# Hackerboat_Control_Board.net
KiCad netlist of a schematic drawn in EAGLE
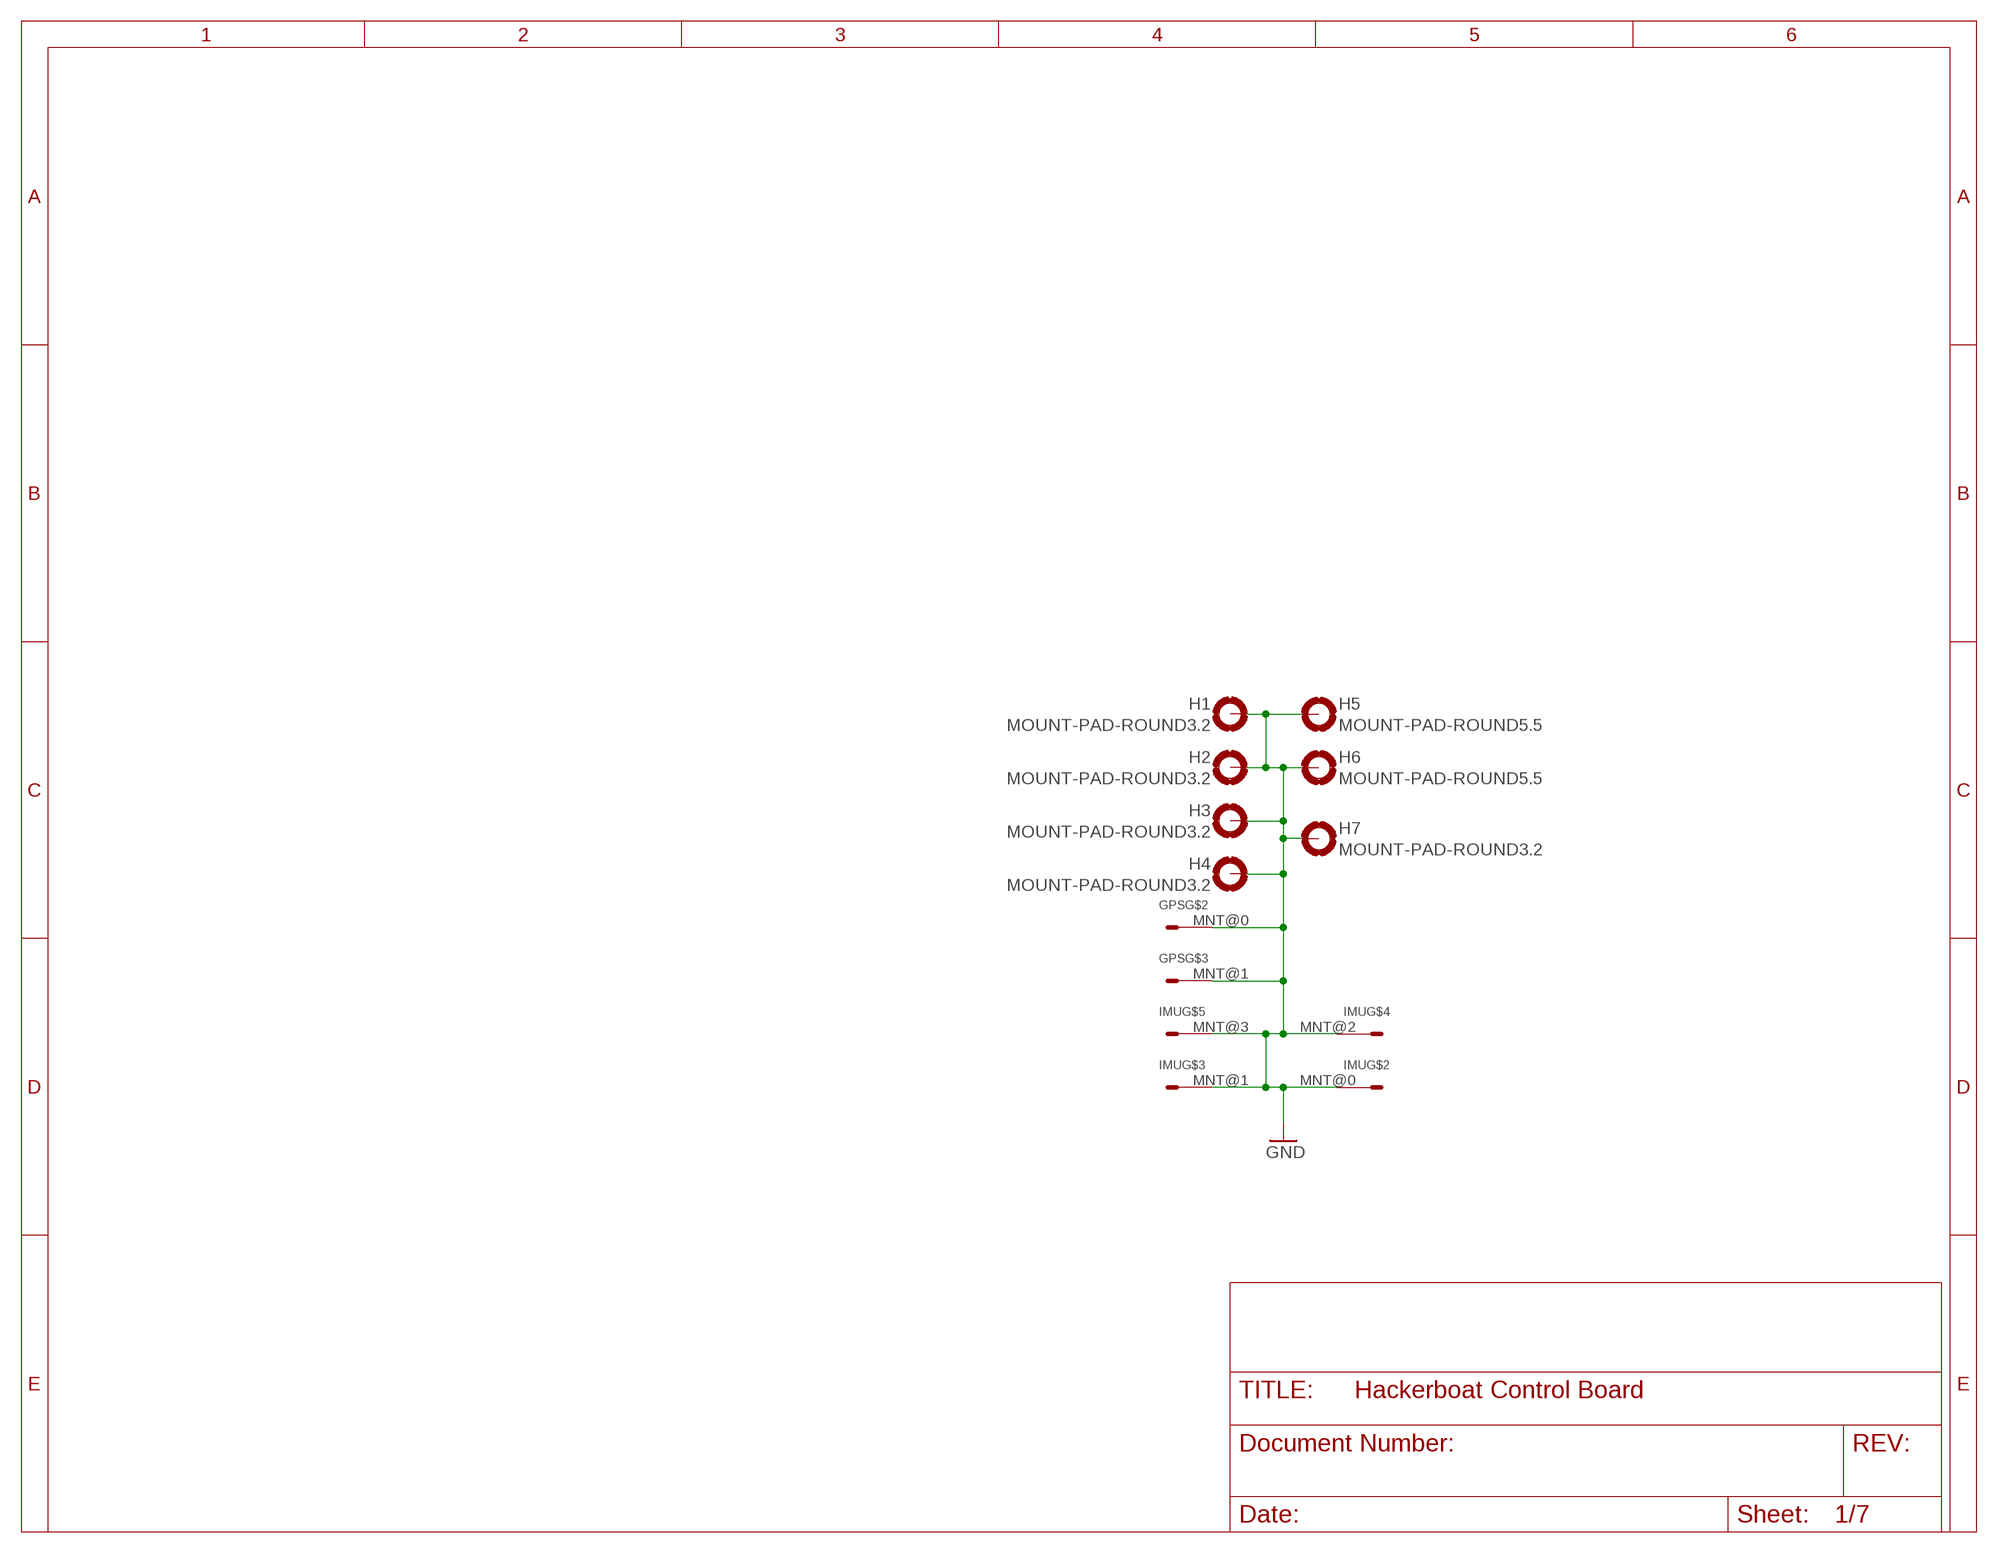
[diagram p0: schematic, sheet 1]
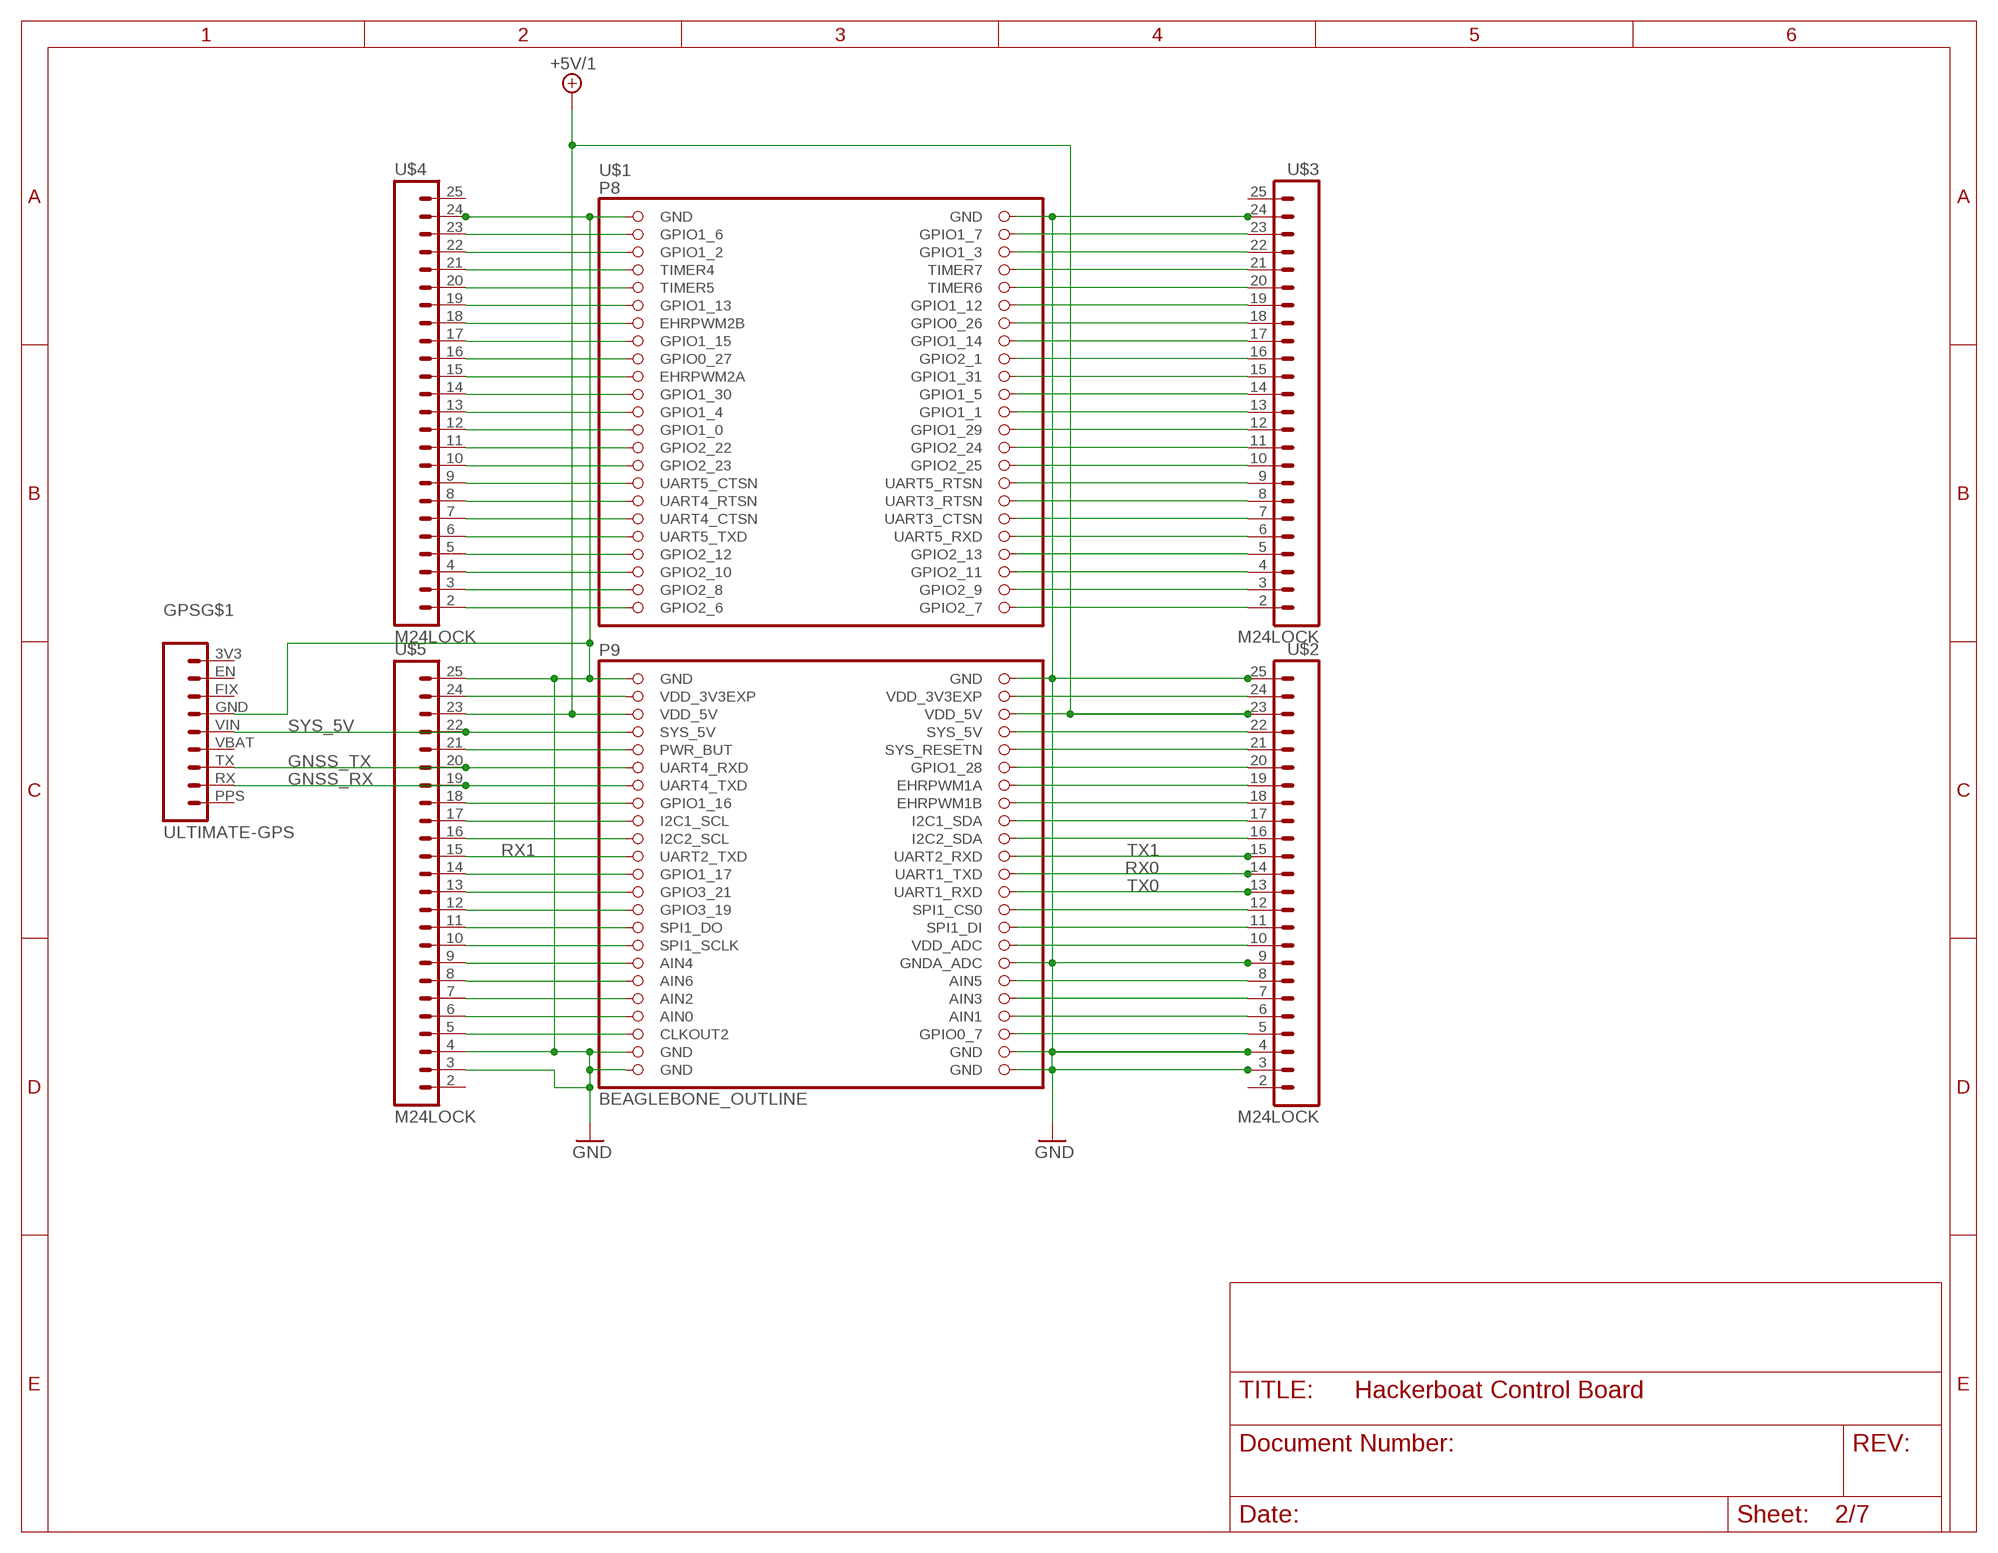
[diagram p1: schematic, sheet 2]
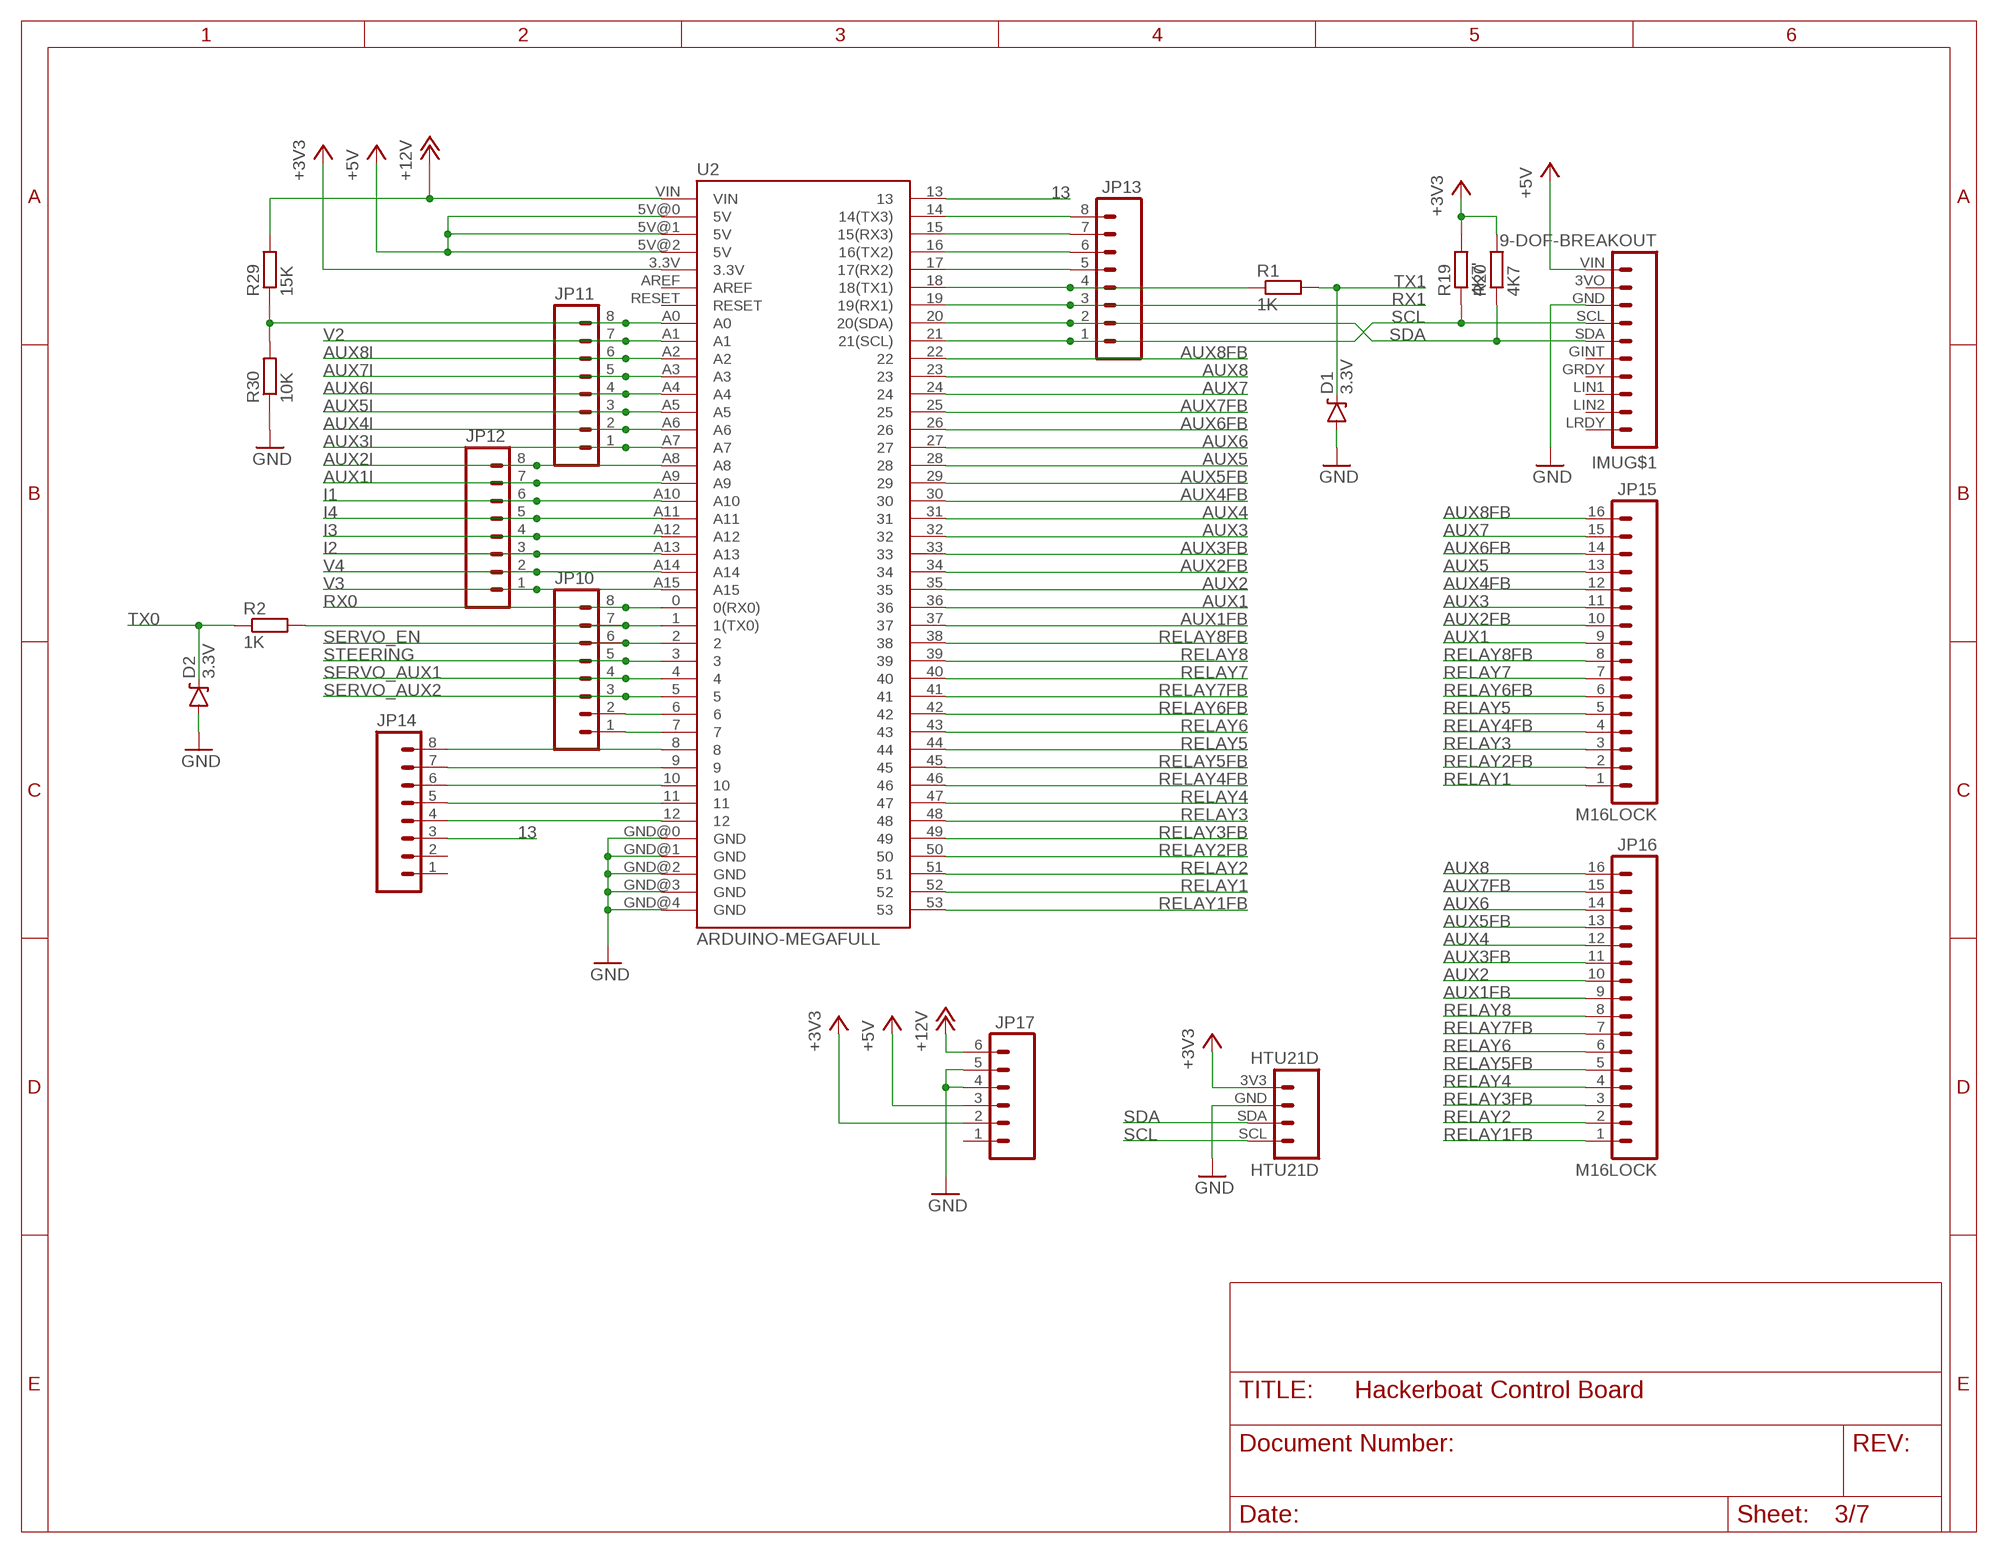
[diagram p2: schematic, sheet 3]
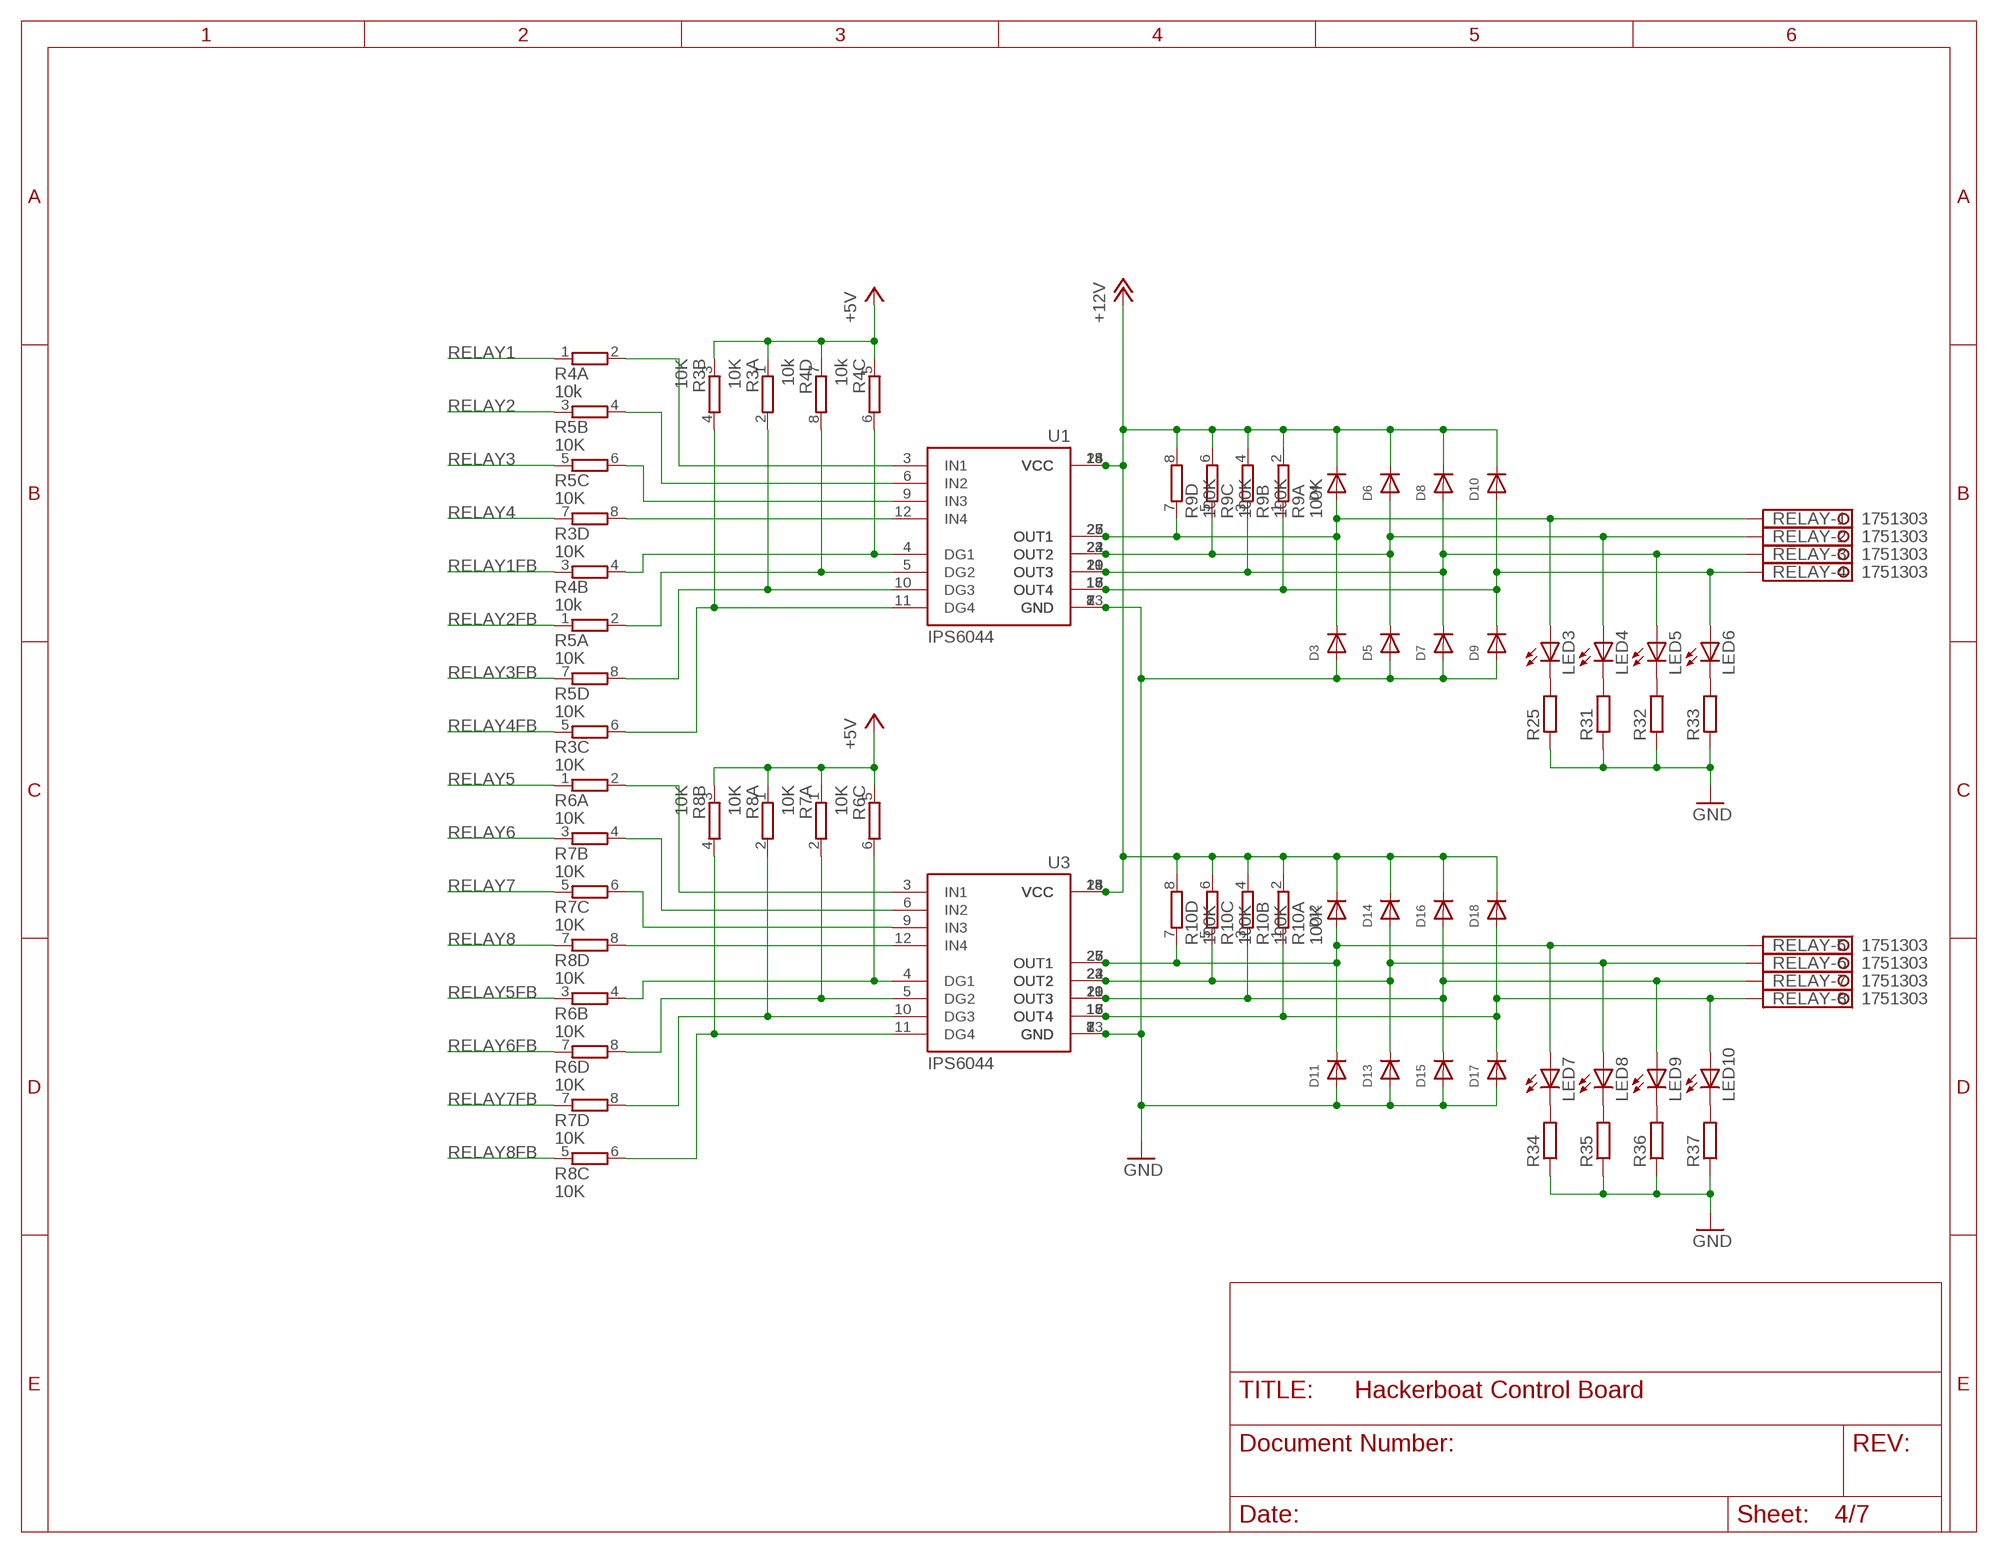
[diagram p3: schematic, sheet 4]
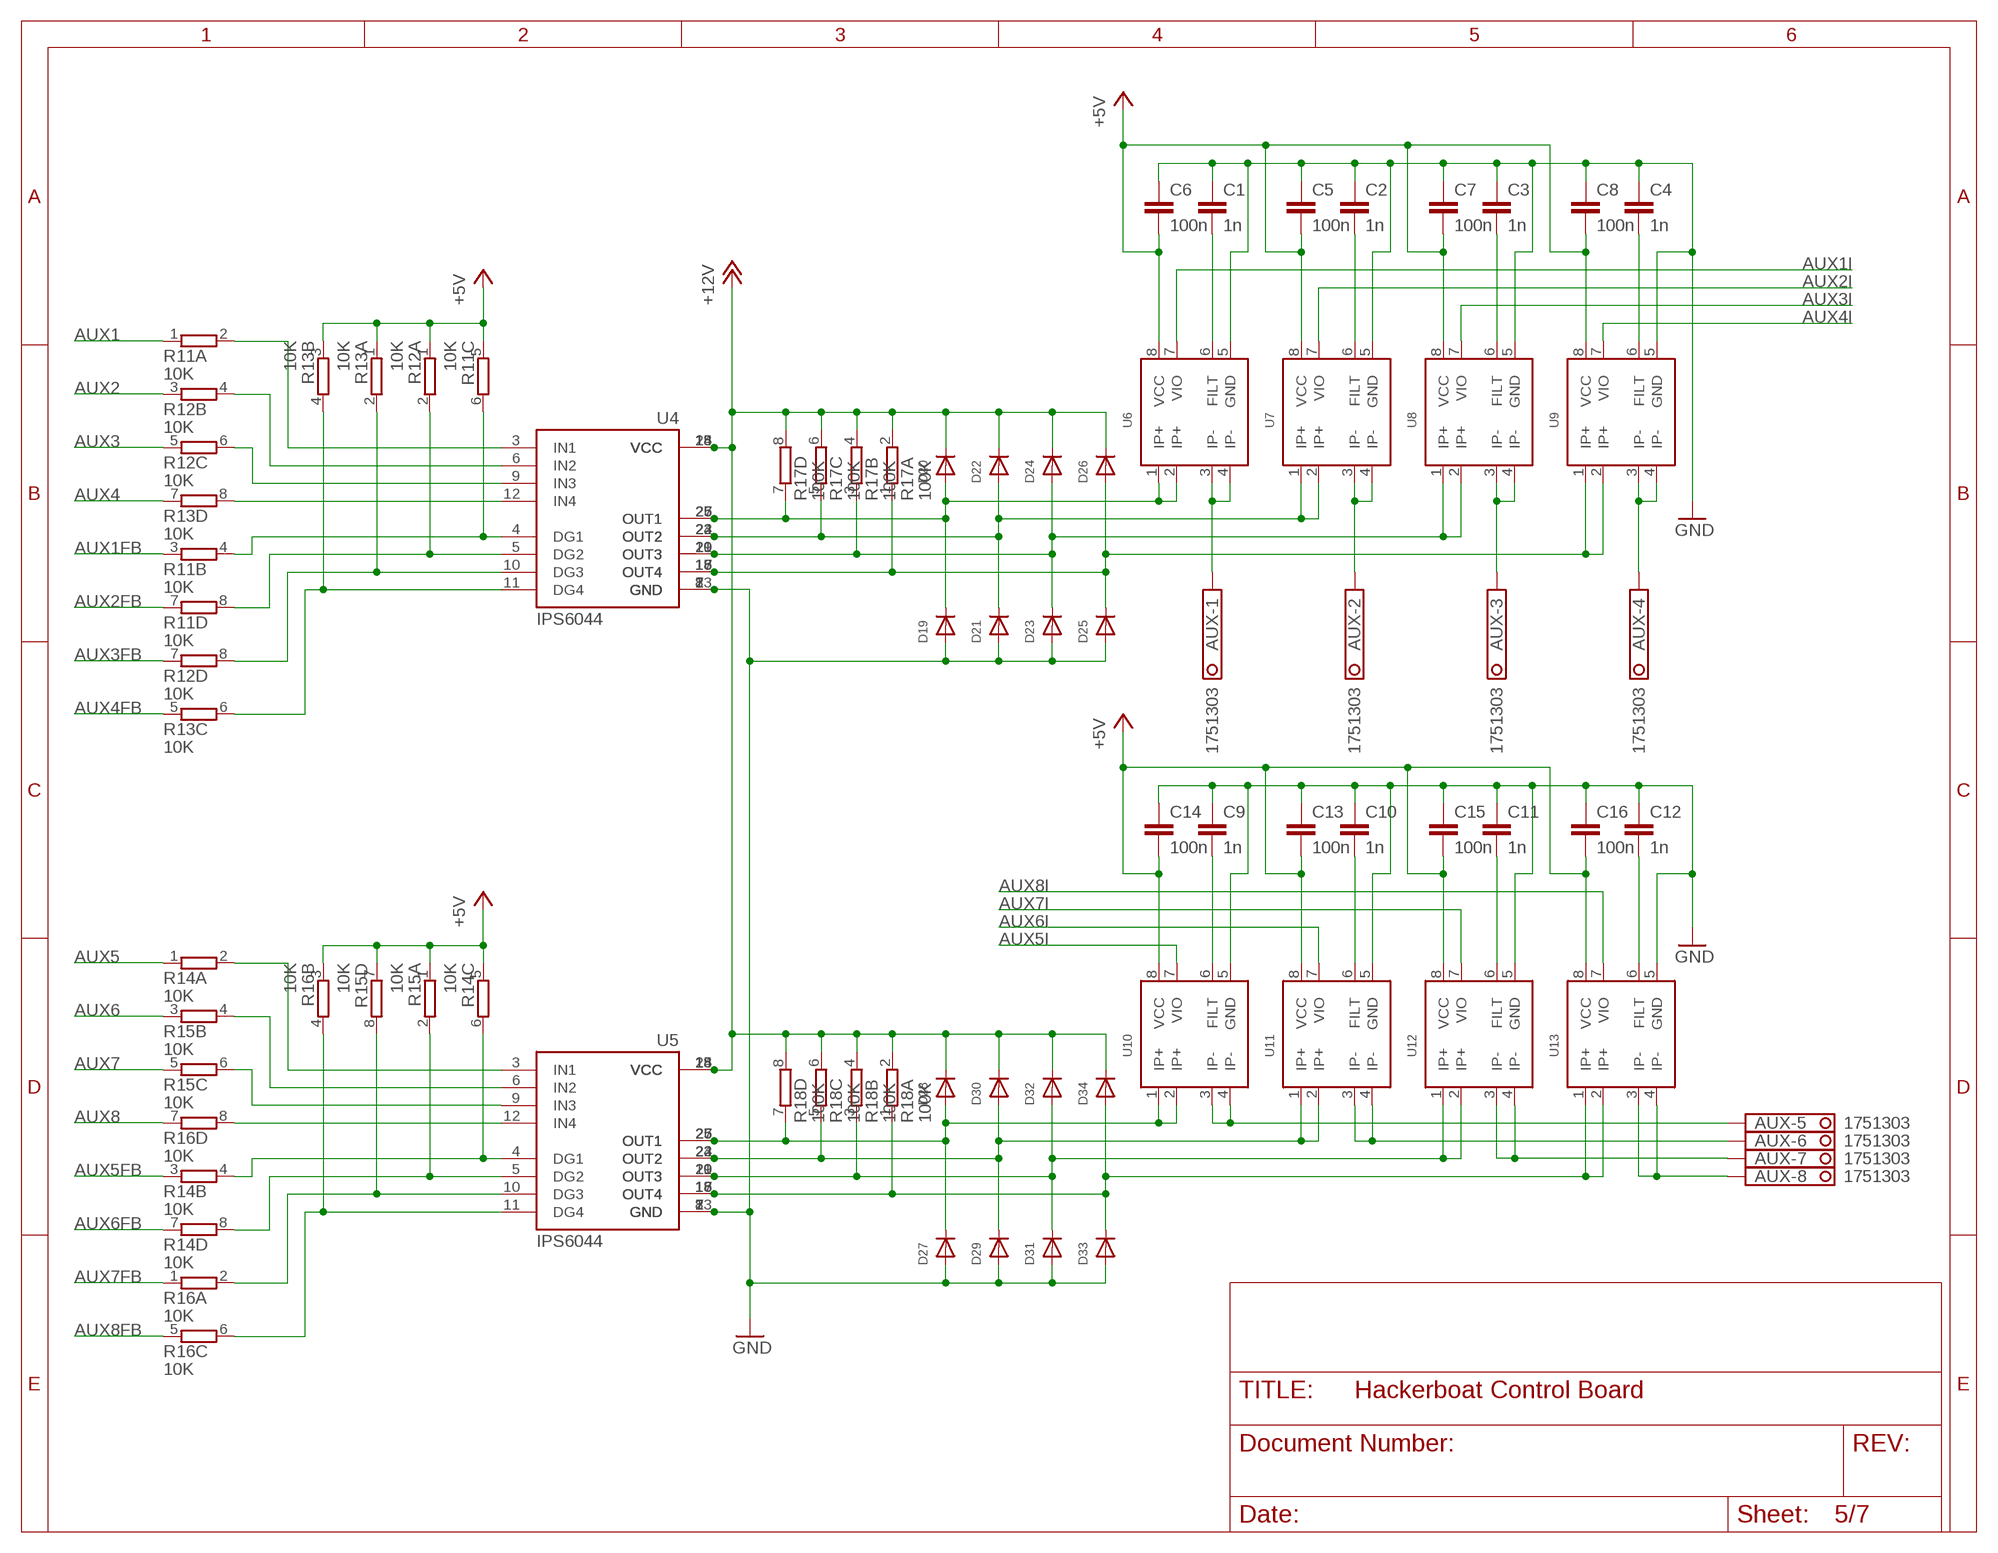
[diagram p4: schematic, sheet 5]
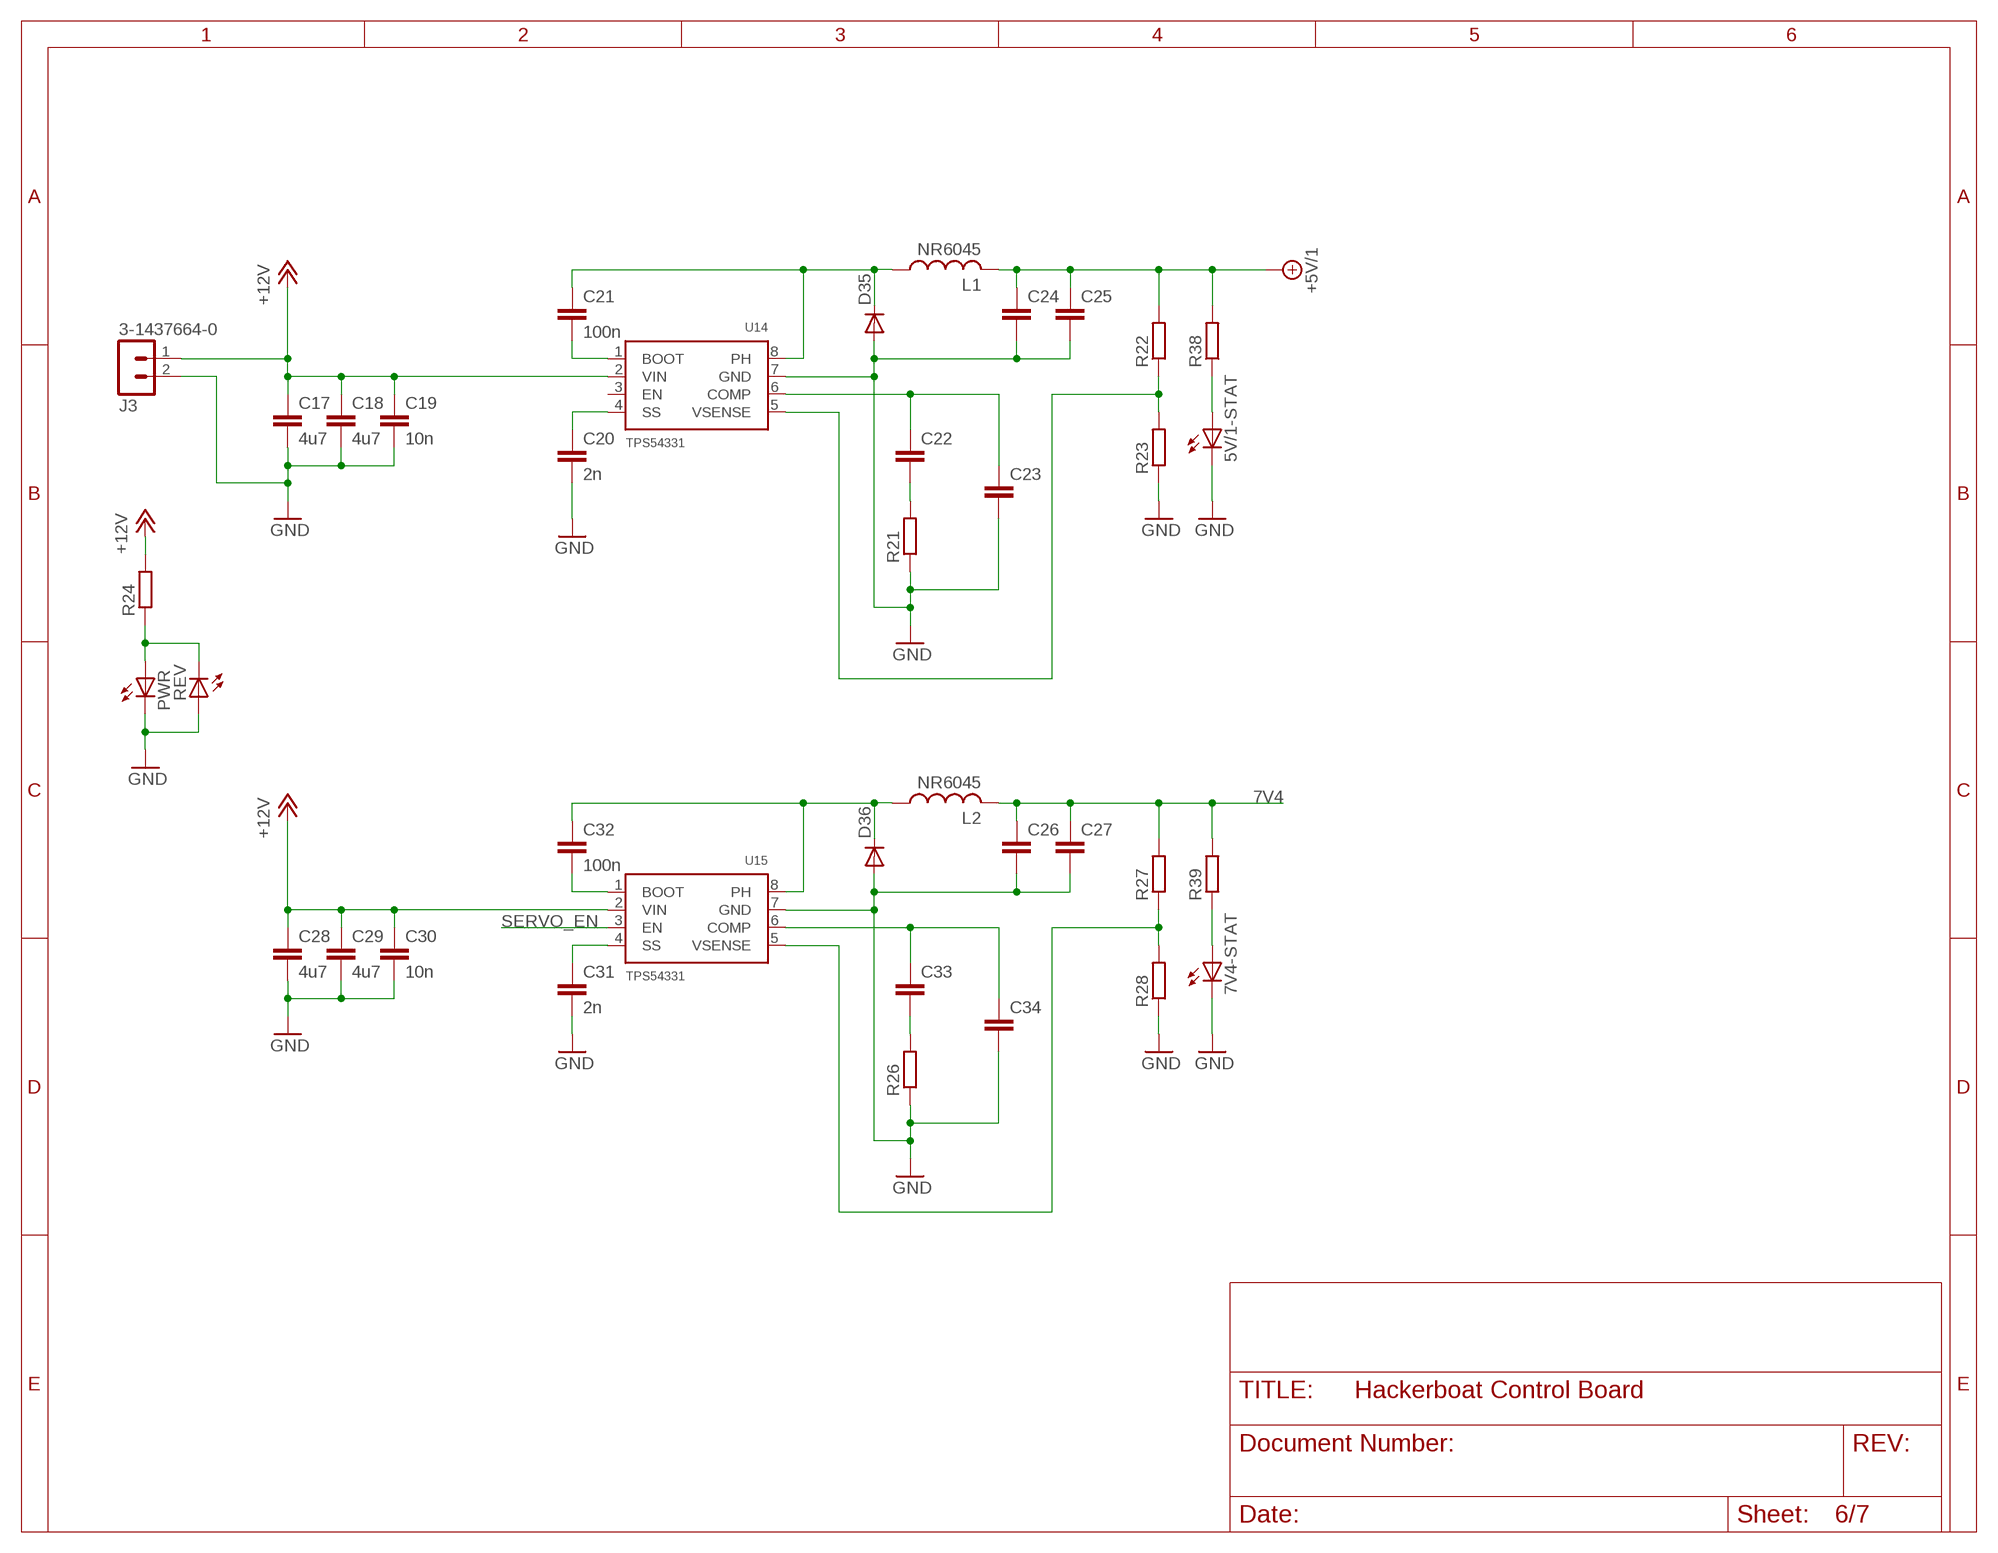
[diagram p5: schematic, sheet 6]
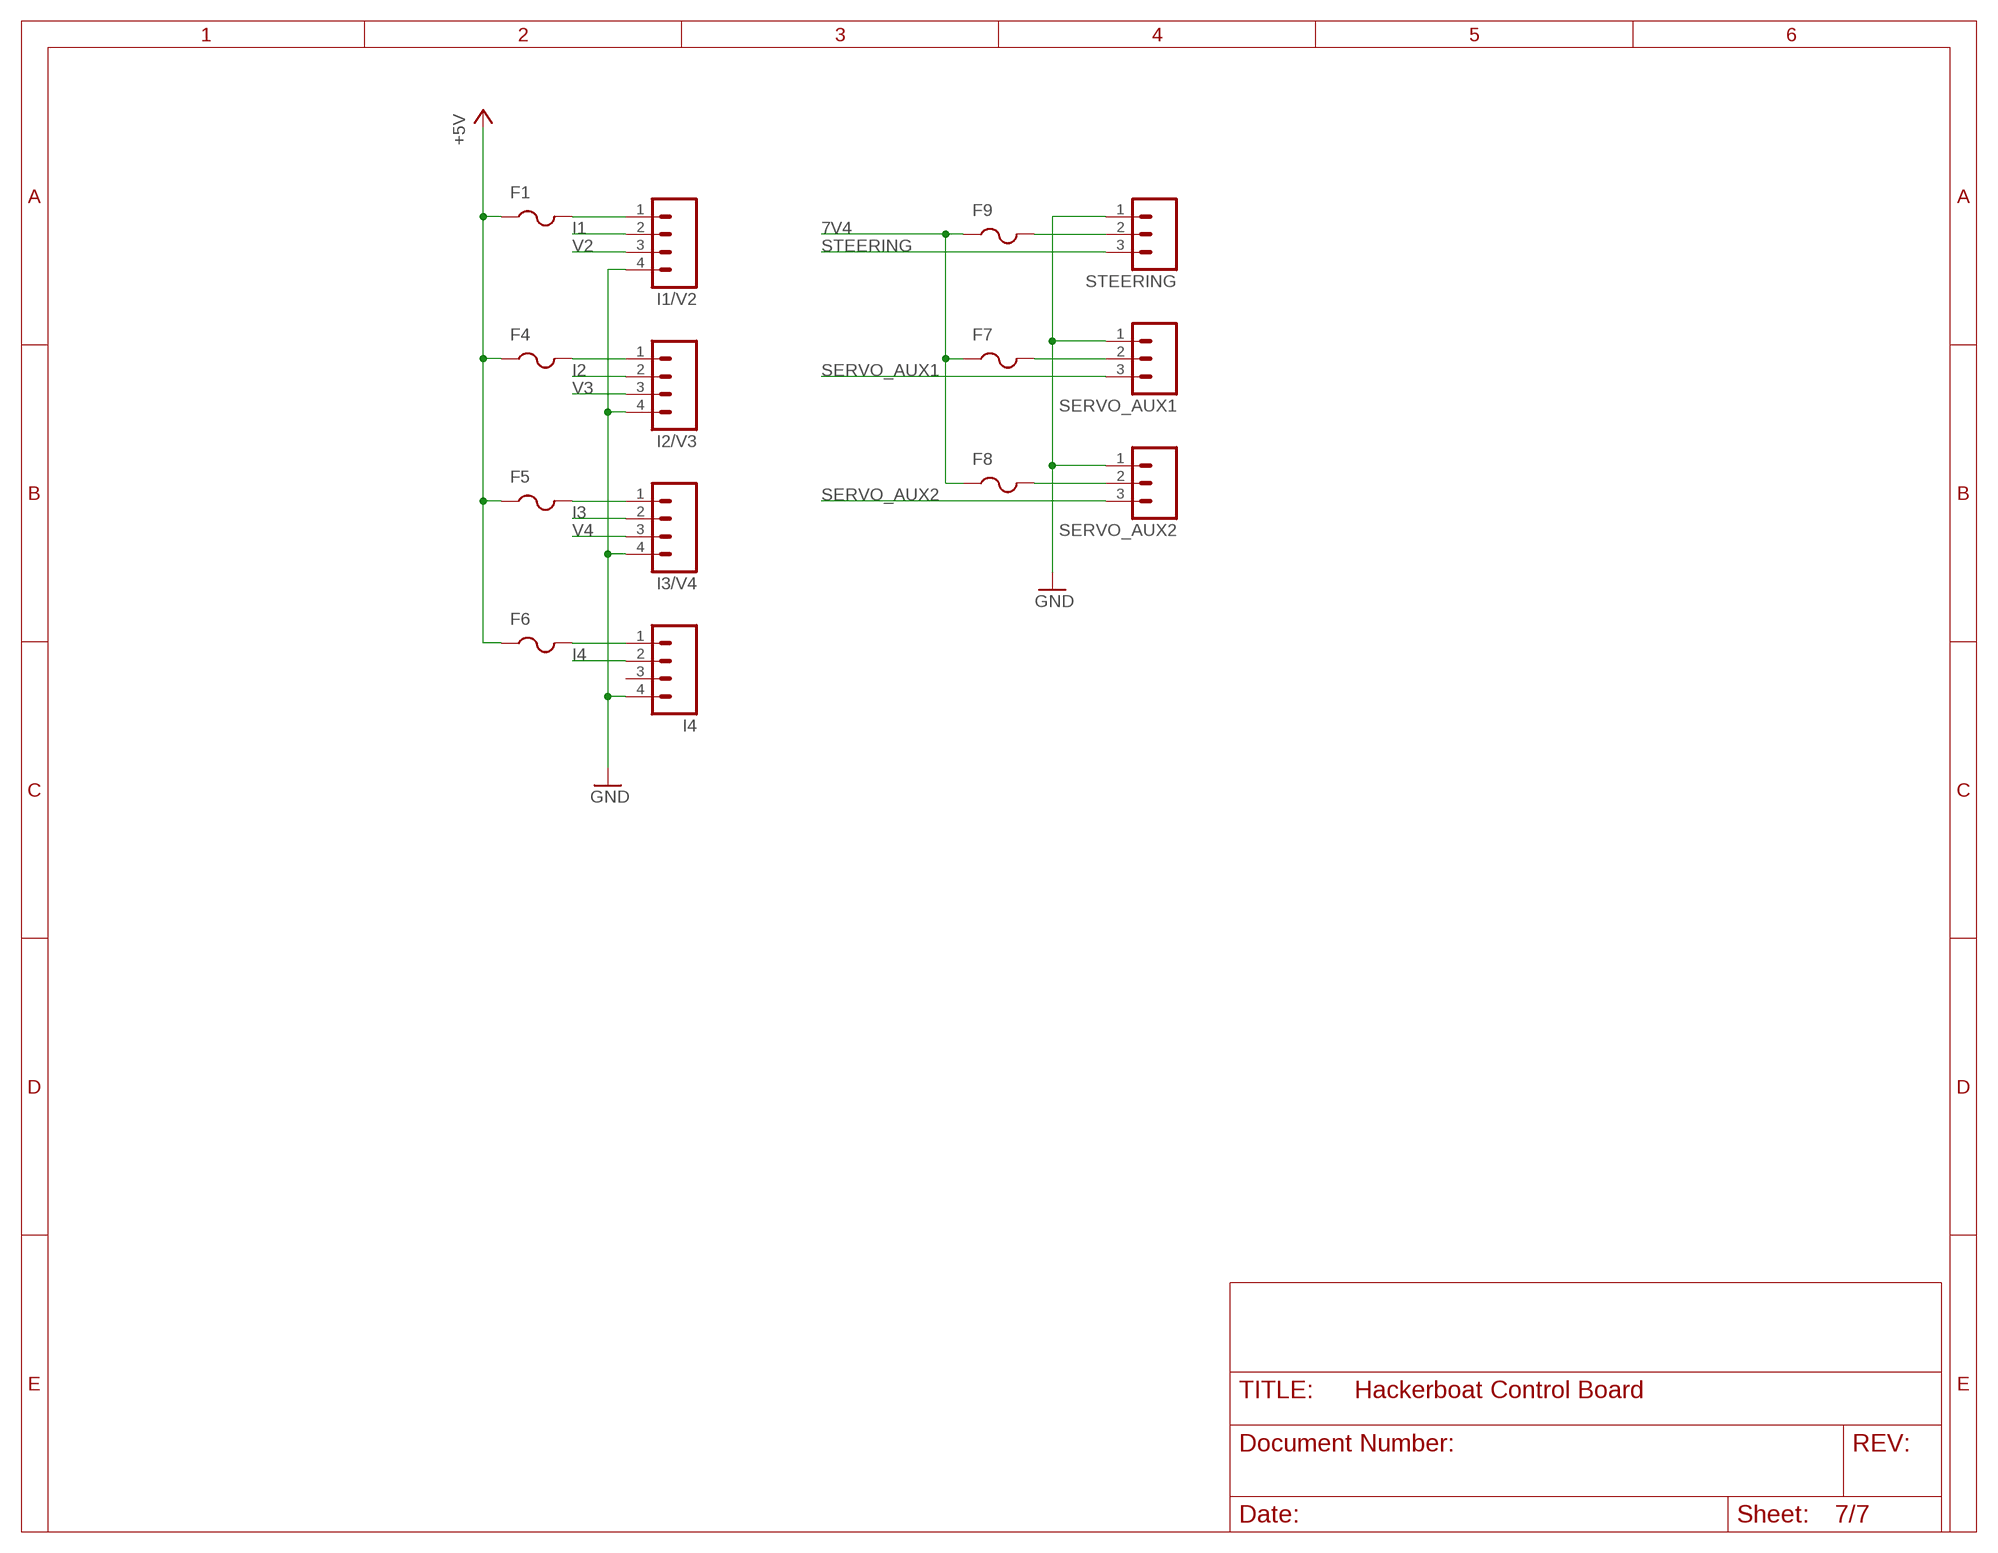
[diagram p6: schematic, sheet 7]

(export (version "E")
  (design (tool "Eeschema 10.0.6"))
  (components
    (comp (ref "GPS")
      (value "ULTIMATE-GPS")
      (footprint "eagle-import:ULTIMATE-GPS")
      (libsource (lib "eagle-import") (part "ULTIMATE-GPS"))
    )
    (comp (ref "U$1")
      (value "BEAGLEBONE_OUTLINE")
      (footprint "eagle-import:BEAGLEBONE_SHIELD")
      (libsource (lib "eagle-import") (part "BEAGLEBONE_OUTLINE"))
    )
    (comp (ref "U$2")
      (value "M24LOCK")
      (footprint "eagle-import:1X24_LOCK")
      (libsource (lib "eagle-import") (part "M24LOCK"))
    )
    (comp (ref "U$3")
      (value "M24LOCK")
      (footprint "eagle-import:1X24_LOCK")
      (libsource (lib "eagle-import") (part "M24LOCK"))
    )
    (comp (ref "U$4")
      (value "M24LOCK")
      (footprint "eagle-import:1X24_LOCK")
      (libsource (lib "eagle-import") (part "M24LOCK"))
    )
    (comp (ref "U$5")
      (value "M24LOCK")
      (footprint "eagle-import:1X24_LOCK")
      (libsource (lib "eagle-import") (part "M24LOCK"))
    )
    (comp (ref "F1")
      (value "PTCFUSE-1206")
      (footprint "eagle-import:R1206")
      (libsource (lib "eagle-import") (part "PTCFUSE-1206"))
    )
    (comp (ref "F4")
      (value "PTCFUSE-1206")
      (footprint "eagle-import:R1206")
      (libsource (lib "eagle-import") (part "PTCFUSE-1206"))
    )
    (comp (ref "F5")
      (value "PTCFUSE-1206")
      (footprint "eagle-import:R1206")
      (libsource (lib "eagle-import") (part "PTCFUSE-1206"))
    )
    (comp (ref "F6")
      (value "PTCFUSE-1206")
      (footprint "eagle-import:R1206")
      (libsource (lib "eagle-import") (part "PTCFUSE-1206"))
    )
    (comp (ref "F7")
      (value "PTCFUSE-1206")
      (footprint "eagle-import:R1206")
      (libsource (lib "eagle-import") (part "PTCFUSE-1206"))
    )
    (comp (ref "F8")
      (value "PTCFUSE-1206")
      (footprint "eagle-import:R1206")
      (libsource (lib "eagle-import") (part "PTCFUSE-1206"))
    )
    (comp (ref "F9")
      (value "PTCFUSE-1206")
      (footprint "eagle-import:R1206")
      (libsource (lib "eagle-import") (part "PTCFUSE-1206"))
    )
    (comp (ref "I1/V2")
      (value "M04LOCK_LONGPADS")
      (footprint "eagle-import:1X04_LOCK_LONGPADS")
      (libsource (lib "eagle-import") (part "M04LOCK_LONGPADS"))
    )
    (comp (ref "I2/V3")
      (value "M04LOCK_LONGPADS")
      (footprint "eagle-import:1X04_LOCK_LONGPADS")
      (libsource (lib "eagle-import") (part "M04LOCK_LONGPADS"))
    )
    (comp (ref "I3/V4")
      (value "M04LOCK_LONGPADS")
      (footprint "eagle-import:1X04_LOCK_LONGPADS")
      (libsource (lib "eagle-import") (part "M04LOCK_LONGPADS"))
    )
    (comp (ref "I4")
      (value "M04LOCK_LONGPADS")
      (footprint "eagle-import:1X04_LOCK_LONGPADS")
      (libsource (lib "eagle-import") (part "M04LOCK_LONGPADS"))
    )
    (comp (ref "SERVO_AUX1")
      (value "M03LOCK_LONGPADS")
      (footprint "eagle-import:1X03_LOCK_LONGPADS")
      (libsource (lib "eagle-import") (part "M03LOCK_LONGPADS"))
    )
    (comp (ref "SERVO_AUX2")
      (value "M03LOCK_LONGPADS")
      (footprint "eagle-import:1X03_LOCK_LONGPADS")
      (libsource (lib "eagle-import") (part "M03LOCK_LONGPADS"))
    )
    (comp (ref "STEERING")
      (value "M03LOCK_LONGPADS")
      (footprint "eagle-import:1X03_LOCK_LONGPADS")
      (libsource (lib "eagle-import") (part "M03LOCK_LONGPADS"))
    )
    (comp (ref "H1")
      (value "MOUNT-PAD-ROUND3.2")
      (footprint "eagle-import:3,2-PAD")
      (libsource (lib "eagle-import") (part "MOUNT-PAD-ROUND3.2"))
    )
    (comp (ref "H2")
      (value "MOUNT-PAD-ROUND3.2")
      (footprint "eagle-import:3,2-PAD")
      (libsource (lib "eagle-import") (part "MOUNT-PAD-ROUND3.2"))
    )
    (comp (ref "H3")
      (value "MOUNT-PAD-ROUND3.2")
      (footprint "eagle-import:3,2-PAD")
      (libsource (lib "eagle-import") (part "MOUNT-PAD-ROUND3.2"))
    )
    (comp (ref "H4")
      (value "MOUNT-PAD-ROUND3.2")
      (footprint "eagle-import:3,2-PAD")
      (libsource (lib "eagle-import") (part "MOUNT-PAD-ROUND3.2"))
    )
    (comp (ref "H5")
      (value "MOUNT-PAD-ROUND5.5")
      (footprint "eagle-import:5,5-PAD")
      (libsource (lib "eagle-import") (part "MOUNT-PAD-ROUND5.5"))
    )
    (comp (ref "H6")
      (value "MOUNT-PAD-ROUND5.5")
      (footprint "eagle-import:5,5-PAD")
      (libsource (lib "eagle-import") (part "MOUNT-PAD-ROUND5.5"))
    )
    (comp (ref "H7")
      (value "MOUNT-PAD-ROUND3.2")
      (footprint "eagle-import:3,2-PAD")
      (libsource (lib "eagle-import") (part "MOUNT-PAD-ROUND3.2"))
    )
    (comp (ref "IMU")
      (value "9-DOF-BREAKOUT")
      (footprint "eagle-import:9-DOF-BREAKOUT")
      (libsource (lib "eagle-import") (part "9-DOF-BREAKOUT"))
    )
    (comp (ref "D3")
      (value "DIODESOD-123")
      (footprint "eagle-import:SOD-123")
      (libsource (lib "eagle-import") (part "DIODESOD-123"))
    )
    (comp (ref "D4")
      (value "DIODESOD-123")
      (footprint "eagle-import:SOD-123")
      (libsource (lib "eagle-import") (part "DIODESOD-123"))
    )
    (comp (ref "D5")
      (value "DIODESOD-123")
      (footprint "eagle-import:SOD-123")
      (libsource (lib "eagle-import") (part "DIODESOD-123"))
    )
    (comp (ref "D6")
      (value "DIODESOD-123")
      (footprint "eagle-import:SOD-123")
      (libsource (lib "eagle-import") (part "DIODESOD-123"))
    )
    (comp (ref "D7")
      (value "DIODESOD-123")
      (footprint "eagle-import:SOD-123")
      (libsource (lib "eagle-import") (part "DIODESOD-123"))
    )
    (comp (ref "D8")
      (value "DIODESOD-123")
      (footprint "eagle-import:SOD-123")
      (libsource (lib "eagle-import") (part "DIODESOD-123"))
    )
    (comp (ref "D9")
      (value "DIODESOD-123")
      (footprint "eagle-import:SOD-123")
      (libsource (lib "eagle-import") (part "DIODESOD-123"))
    )
    (comp (ref "D10")
      (value "DIODESOD-123")
      (footprint "eagle-import:SOD-123")
      (libsource (lib "eagle-import") (part "DIODESOD-123"))
    )
    (comp (ref "D11")
      (value "DIODESOD-123")
      (footprint "eagle-import:SOD-123")
      (libsource (lib "eagle-import") (part "DIODESOD-123"))
    )
    (comp (ref "D12")
      (value "DIODESOD-123")
      (footprint "eagle-import:SOD-123")
      (libsource (lib "eagle-import") (part "DIODESOD-123"))
    )
    (comp (ref "D13")
      (value "DIODESOD-123")
      (footprint "eagle-import:SOD-123")
      (libsource (lib "eagle-import") (part "DIODESOD-123"))
    )
    (comp (ref "D14")
      (value "DIODESOD-123")
      (footprint "eagle-import:SOD-123")
      (libsource (lib "eagle-import") (part "DIODESOD-123"))
    )
    (comp (ref "D15")
      (value "DIODESOD-123")
      (footprint "eagle-import:SOD-123")
      (libsource (lib "eagle-import") (part "DIODESOD-123"))
    )
    (comp (ref "D16")
      (value "DIODESOD-123")
      (footprint "eagle-import:SOD-123")
      (libsource (lib "eagle-import") (part "DIODESOD-123"))
    )
    (comp (ref "D17")
      (value "DIODESOD-123")
      (footprint "eagle-import:SOD-123")
      (libsource (lib "eagle-import") (part "DIODESOD-123"))
    )
    (comp (ref "D18")
      (value "DIODESOD-123")
      (footprint "eagle-import:SOD-123")
      (libsource (lib "eagle-import") (part "DIODESOD-123"))
    )
    (comp (ref "LED3")
      (value "LEDCHIPLED_0805")
      (footprint "eagle-import:CHIPLED_0805")
      (libsource (lib "eagle-import") (part "LEDCHIPLED_0805"))
    )
    (comp (ref "LED4")
      (value "LEDCHIPLED_0805")
      (footprint "eagle-import:CHIPLED_0805")
      (libsource (lib "eagle-import") (part "LEDCHIPLED_0805"))
    )
    (comp (ref "LED5")
      (value "LEDCHIPLED_0805")
      (footprint "eagle-import:CHIPLED_0805")
      (libsource (lib "eagle-import") (part "LEDCHIPLED_0805"))
    )
    (comp (ref "LED6")
      (value "LEDCHIPLED_0805")
      (footprint "eagle-import:CHIPLED_0805")
      (libsource (lib "eagle-import") (part "LEDCHIPLED_0805"))
    )
    (comp (ref "LED7")
      (value "LEDCHIPLED_0805")
      (footprint "eagle-import:CHIPLED_0805")
      (libsource (lib "eagle-import") (part "LEDCHIPLED_0805"))
    )
    (comp (ref "LED8")
      (value "LEDCHIPLED_0805")
      (footprint "eagle-import:CHIPLED_0805")
      (libsource (lib "eagle-import") (part "LEDCHIPLED_0805"))
    )
    (comp (ref "LED9")
      (value "LEDCHIPLED_0805")
      (footprint "eagle-import:CHIPLED_0805")
      (libsource (lib "eagle-import") (part "LEDCHIPLED_0805"))
    )
    (comp (ref "LED10")
      (value "LEDCHIPLED_0805")
      (footprint "eagle-import:CHIPLED_0805")
      (libsource (lib "eagle-import") (part "LEDCHIPLED_0805"))
    )
    (comp (ref "R3")
      (value "10K")
      (footprint "eagle-import:CTS742C083-RES")
      (libsource (lib "eagle-import") (part "4R-NCTS742C083"))
    )
    (comp (ref "R4")
      (value "10k")
      (footprint "eagle-import:CTS742C083-RES")
      (libsource (lib "eagle-import") (part "4R-NCTS742C083"))
    )
    (comp (ref "R5")
      (value "10K")
      (footprint "eagle-import:CTS742C083-RES")
      (libsource (lib "eagle-import") (part "4R-NCTS742C083"))
    )
    (comp (ref "R6")
      (value "10K")
      (footprint "eagle-import:CTS742C083-RES")
      (libsource (lib "eagle-import") (part "4R-NCTS742C083"))
    )
    (comp (ref "R7")
      (value "10K")
      (footprint "eagle-import:CTS742C083-RES")
      (libsource (lib "eagle-import") (part "4R-NCTS742C083"))
    )
    (comp (ref "R8")
      (value "10K")
      (footprint "eagle-import:CTS742C083-RES")
      (libsource (lib "eagle-import") (part "4R-NCTS742C083"))
    )
    (comp (ref "R9")
      (value "100K")
      (footprint "eagle-import:CTS742C083-RES")
      (libsource (lib "eagle-import") (part "4R-NCTS742C083"))
    )
    (comp (ref "R10")
      (value "100K")
      (footprint "eagle-import:CTS742C083-RES")
      (libsource (lib "eagle-import") (part "4R-NCTS742C083"))
    )
    (comp (ref "R25")
      (value "R-EU_R0603")
      (footprint "eagle-import:R0603")
      (libsource (lib "eagle-import") (part "R-EU_R0603"))
    )
    (comp (ref "R31")
      (value "R-EU_R0603")
      (footprint "eagle-import:R0603")
      (libsource (lib "eagle-import") (part "R-EU_R0603"))
    )
    (comp (ref "R32")
      (value "R-EU_R0603")
      (footprint "eagle-import:R0603")
      (libsource (lib "eagle-import") (part "R-EU_R0603"))
    )
    (comp (ref "R33")
      (value "R-EU_R0603")
      (footprint "eagle-import:R0603")
      (libsource (lib "eagle-import") (part "R-EU_R0603"))
    )
    (comp (ref "R34")
      (value "R-EU_R0603")
      (footprint "eagle-import:R0603")
      (libsource (lib "eagle-import") (part "R-EU_R0603"))
    )
    (comp (ref "R35")
      (value "R-EU_R0603")
      (footprint "eagle-import:R0603")
      (libsource (lib "eagle-import") (part "R-EU_R0603"))
    )
    (comp (ref "R36")
      (value "R-EU_R0603")
      (footprint "eagle-import:R0603")
      (libsource (lib "eagle-import") (part "R-EU_R0603"))
    )
    (comp (ref "R37")
      (value "R-EU_R0603")
      (footprint "eagle-import:R0603")
      (libsource (lib "eagle-import") (part "R-EU_R0603"))
    )
    (comp (ref "RELAY")
      (value "1751303")
      (footprint "eagle-import:1751303")
      (libsource (lib "eagle-import") (part "1751303"))
    )
    (comp (ref "U1")
      (value "IPS6044")
      (footprint "eagle-import:SO-28L")
      (libsource (lib "eagle-import") (part "IPS6044"))
    )
    (comp (ref "U3")
      (value "IPS6044")
      (footprint "eagle-import:SO-28L")
      (libsource (lib "eagle-import") (part "IPS6044"))
    )
    (comp (ref "AUX")
      (value "1751303")
      (footprint "eagle-import:1751303")
      (libsource (lib "eagle-import") (part "1751303"))
    )
    (comp (ref "C1")
      (value "1n")
      (footprint "eagle-import:C0603")
      (libsource (lib "eagle-import") (part "C-EUC0603"))
    )
    (comp (ref "C2")
      (value "1n")
      (footprint "eagle-import:C0603")
      (libsource (lib "eagle-import") (part "C-EUC0603"))
    )
    (comp (ref "C3")
      (value "1n")
      (footprint "eagle-import:C0603")
      (libsource (lib "eagle-import") (part "C-EUC0603"))
    )
    (comp (ref "C4")
      (value "1n")
      (footprint "eagle-import:C0603")
      (libsource (lib "eagle-import") (part "C-EUC0603"))
    )
    (comp (ref "C5")
      (value "100n")
      (footprint "eagle-import:C0603")
      (libsource (lib "eagle-import") (part "C-EUC0603"))
    )
    (comp (ref "C6")
      (value "100n")
      (footprint "eagle-import:C0603")
      (libsource (lib "eagle-import") (part "C-EUC0603"))
    )
    (comp (ref "C7")
      (value "100n")
      (footprint "eagle-import:C0603")
      (libsource (lib "eagle-import") (part "C-EUC0603"))
    )
    (comp (ref "C8")
      (value "100n")
      (footprint "eagle-import:C0603")
      (libsource (lib "eagle-import") (part "C-EUC0603"))
    )
    (comp (ref "C9")
      (value "1n")
      (footprint "eagle-import:C0603")
      (libsource (lib "eagle-import") (part "C-EUC0603"))
    )
    (comp (ref "C10")
      (value "1n")
      (footprint "eagle-import:C0603")
      (libsource (lib "eagle-import") (part "C-EUC0603"))
    )
    (comp (ref "C11")
      (value "1n")
      (footprint "eagle-import:C0603")
      (libsource (lib "eagle-import") (part "C-EUC0603"))
    )
    (comp (ref "C12")
      (value "1n")
      (footprint "eagle-import:C0603")
      (libsource (lib "eagle-import") (part "C-EUC0603"))
    )
    (comp (ref "C13")
      (value "100n")
      (footprint "eagle-import:C0603")
      (libsource (lib "eagle-import") (part "C-EUC0603"))
    )
    (comp (ref "C14")
      (value "100n")
      (footprint "eagle-import:C0603")
      (libsource (lib "eagle-import") (part "C-EUC0603"))
    )
    (comp (ref "C15")
      (value "100n")
      (footprint "eagle-import:C0603")
      (libsource (lib "eagle-import") (part "C-EUC0603"))
    )
    (comp (ref "C16")
      (value "100n")
      (footprint "eagle-import:C0603")
      (libsource (lib "eagle-import") (part "C-EUC0603"))
    )
    (comp (ref "D19")
      (value "DIODESOD-123")
      (footprint "eagle-import:SOD-123")
      (libsource (lib "eagle-import") (part "DIODESOD-123"))
    )
    (comp (ref "D20")
      (value "DIODESOD-123")
      (footprint "eagle-import:SOD-123")
      (libsource (lib "eagle-import") (part "DIODESOD-123"))
    )
    (comp (ref "D21")
      (value "DIODESOD-123")
      (footprint "eagle-import:SOD-123")
      (libsource (lib "eagle-import") (part "DIODESOD-123"))
    )
    (comp (ref "D22")
      (value "DIODESOD-123")
      (footprint "eagle-import:SOD-123")
      (libsource (lib "eagle-import") (part "DIODESOD-123"))
    )
    (comp (ref "D23")
      (value "DIODESOD-123")
      (footprint "eagle-import:SOD-123")
      (libsource (lib "eagle-import") (part "DIODESOD-123"))
    )
    (comp (ref "D24")
      (value "DIODESOD-123")
      (footprint "eagle-import:SOD-123")
      (libsource (lib "eagle-import") (part "DIODESOD-123"))
    )
    (comp (ref "D25")
      (value "DIODESOD-123")
      (footprint "eagle-import:SOD-123")
      (libsource (lib "eagle-import") (part "DIODESOD-123"))
    )
    (comp (ref "D26")
      (value "DIODESOD-123")
      (footprint "eagle-import:SOD-123")
      (libsource (lib "eagle-import") (part "DIODESOD-123"))
    )
    (comp (ref "D27")
      (value "DIODESOD-123")
      (footprint "eagle-import:SOD-123")
      (libsource (lib "eagle-import") (part "DIODESOD-123"))
    )
    (comp (ref "D28")
      (value "DIODESOD-123")
      (footprint "eagle-import:SOD-123")
      (libsource (lib "eagle-import") (part "DIODESOD-123"))
    )
    (comp (ref "D29")
      (value "DIODESOD-123")
      (footprint "eagle-import:SOD-123")
      (libsource (lib "eagle-import") (part "DIODESOD-123"))
    )
    (comp (ref "D30")
      (value "DIODESOD-123")
      (footprint "eagle-import:SOD-123")
      (libsource (lib "eagle-import") (part "DIODESOD-123"))
    )
    (comp (ref "D31")
      (value "DIODESOD-123")
      (footprint "eagle-import:SOD-123")
      (libsource (lib "eagle-import") (part "DIODESOD-123"))
    )
    (comp (ref "D32")
      (value "DIODESOD-123")
      (footprint "eagle-import:SOD-123")
      (libsource (lib "eagle-import") (part "DIODESOD-123"))
    )
    (comp (ref "D33")
      (value "DIODESOD-123")
      (footprint "eagle-import:SOD-123")
      (libsource (lib "eagle-import") (part "DIODESOD-123"))
    )
    (comp (ref "D34")
      (value "DIODESOD-123")
      (footprint "eagle-import:SOD-123")
      (libsource (lib "eagle-import") (part "DIODESOD-123"))
    )
    (comp (ref "R11")
      (value "10K")
      (footprint "eagle-import:CTS742C083-RES")
      (libsource (lib "eagle-import") (part "4R-NCTS742C083"))
    )
    (comp (ref "R12")
      (value "10K")
      (footprint "eagle-import:CTS742C083-RES")
      (libsource (lib "eagle-import") (part "4R-NCTS742C083"))
    )
    (comp (ref "R13")
      (value "10K")
      (footprint "eagle-import:CTS742C083-RES")
      (libsource (lib "eagle-import") (part "4R-NCTS742C083"))
    )
    (comp (ref "R14")
      (value "10K")
      (footprint "eagle-import:CTS742C083-RES")
      (libsource (lib "eagle-import") (part "4R-NCTS742C083"))
    )
    (comp (ref "R15")
      (value "10K")
      (footprint "eagle-import:CTS742C083-RES")
      (libsource (lib "eagle-import") (part "4R-NCTS742C083"))
    )
    (comp (ref "R16")
      (value "10K")
      (footprint "eagle-import:CTS742C083-RES")
      (libsource (lib "eagle-import") (part "4R-NCTS742C083"))
    )
    (comp (ref "R17")
      (value "100K")
      (footprint "eagle-import:CTS742C083-RES")
      (libsource (lib "eagle-import") (part "4R-NCTS742C083"))
    )
    (comp (ref "R18")
      (value "100K")
      (footprint "eagle-import:CTS742C083-RES")
      (libsource (lib "eagle-import") (part "4R-NCTS742C083"))
    )
    (comp (ref "U4")
      (value "IPS6044")
      (footprint "eagle-import:SO-28L")
      (libsource (lib "eagle-import") (part "IPS6044"))
    )
    (comp (ref "U5")
      (value "IPS6044")
      (footprint "eagle-import:SO-28L")
      (libsource (lib "eagle-import") (part "IPS6044"))
    )
    (comp (ref "U6")
      (value "ACS712")
      (footprint "eagle-import:SO08")
      (libsource (lib "eagle-import") (part "ACS712"))
    )
    (comp (ref "U7")
      (value "ACS712")
      (footprint "eagle-import:SO08")
      (libsource (lib "eagle-import") (part "ACS712"))
    )
    (comp (ref "U8")
      (value "ACS712")
      (footprint "eagle-import:SO08")
      (libsource (lib "eagle-import") (part "ACS712"))
    )
    (comp (ref "U9")
      (value "ACS712")
      (footprint "eagle-import:SO08")
      (libsource (lib "eagle-import") (part "ACS712"))
    )
    (comp (ref "U10")
      (value "ACS712")
      (footprint "eagle-import:SO08")
      (libsource (lib "eagle-import") (part "ACS712"))
    )
    (comp (ref "U11")
      (value "ACS712")
      (footprint "eagle-import:SO08")
      (libsource (lib "eagle-import") (part "ACS712"))
    )
    (comp (ref "U12")
      (value "ACS712")
      (footprint "eagle-import:SO08")
      (libsource (lib "eagle-import") (part "ACS712"))
    )
    (comp (ref "U13")
      (value "ACS712")
      (footprint "eagle-import:SO08")
      (libsource (lib "eagle-import") (part "ACS712"))
    )
    (comp (ref "D1")
      (value "3.3V")
      (footprint "eagle-import:SOD-323")
      (libsource (lib "eagle-import") (part "DIODE-ZENER3.3V"))
    )
    (comp (ref "D2")
      (value "3.3V")
      (footprint "eagle-import:SOD-323")
      (libsource (lib "eagle-import") (part "DIODE-ZENER3.3V"))
    )
    (comp (ref "HTU21D")
      (value "HTU21D")
      (footprint "eagle-import:HTU21D")
      (libsource (lib "eagle-import") (part "HTU21D"))
    )
    (comp (ref "JP10")
      (value "M08LOCK")
      (footprint "eagle-import:1X08_LOCK")
      (libsource (lib "eagle-import") (part "M08LOCK"))
    )
    (comp (ref "JP11")
      (value "M08LOCK")
      (footprint "eagle-import:1X08_LOCK")
      (libsource (lib "eagle-import") (part "M08LOCK"))
    )
    (comp (ref "JP12")
      (value "M08LOCK")
      (footprint "eagle-import:1X08_LOCK")
      (libsource (lib "eagle-import") (part "M08LOCK"))
    )
    (comp (ref "JP13")
      (value "M08LOCK")
      (footprint "eagle-import:1X08_LOCK")
      (libsource (lib "eagle-import") (part "M08LOCK"))
    )
    (comp (ref "JP14")
      (value "M08LOCK")
      (footprint "eagle-import:1X08_LOCK")
      (libsource (lib "eagle-import") (part "M08LOCK"))
    )
    (comp (ref "JP15")
      (value "M16LOCK")
      (footprint "eagle-import:1X16_LOCK")
      (libsource (lib "eagle-import") (part "M16LOCK"))
    )
    (comp (ref "JP16")
      (value "M16LOCK")
      (footprint "eagle-import:1X16_LOCK")
      (libsource (lib "eagle-import") (part "M16LOCK"))
    )
    (comp (ref "JP17")
      (value "M06LOCK")
      (footprint "eagle-import:1X06_LOCK")
      (libsource (lib "eagle-import") (part "M06LOCK"))
    )
    (comp (ref "R1")
      (value "1K")
      (footprint "eagle-import:R0603")
      (libsource (lib "eagle-import") (part "R-EU_R0603"))
    )
    (comp (ref "R2")
      (value "1K")
      (footprint "eagle-import:R0603")
      (libsource (lib "eagle-import") (part "R-EU_R0603"))
    )
    (comp (ref "R19")
      (value "4K7'")
      (footprint "eagle-import:R0603")
      (libsource (lib "eagle-import") (part "R-EU_R0603"))
    )
    (comp (ref "R20")
      (value "4K7")
      (footprint "eagle-import:R0603")
      (libsource (lib "eagle-import") (part "R-EU_R0603"))
    )
    (comp (ref "R29")
      (value "15K")
      (footprint "eagle-import:R0603")
      (libsource (lib "eagle-import") (part "R-EU_R0603"))
    )
    (comp (ref "R30")
      (value "10K")
      (footprint "eagle-import:R0603")
      (libsource (lib "eagle-import") (part "R-EU_R0603"))
    )
    (comp (ref "U2")
      (value "ARDUINO-MEGAFULL")
      (footprint "eagle-import:ARDUINO_MEGA")
      (libsource (lib "eagle-import") (part "ARDUINO-MEGAFULL"))
    )
    (comp (ref "5V/1-STAT")
      (value "LEDCHIPLED_0805")
      (footprint "eagle-import:CHIPLED_0805")
      (libsource (lib "eagle-import") (part "LEDCHIPLED_0805"))
    )
    (comp (ref "7V4-STAT")
      (value "LEDCHIPLED_0805")
      (footprint "eagle-import:CHIPLED_0805")
      (libsource (lib "eagle-import") (part "LEDCHIPLED_0805"))
    )
    (comp (ref "C17")
      (value "4u7")
      (footprint "eagle-import:C1210")
      (libsource (lib "eagle-import") (part "C-EUC1210"))
    )
    (comp (ref "C18")
      (value "4u7")
      (footprint "eagle-import:C1210")
      (libsource (lib "eagle-import") (part "C-EUC1210"))
    )
    (comp (ref "C19")
      (value "10n")
      (footprint "eagle-import:C0603")
      (libsource (lib "eagle-import") (part "C-EUC0603"))
    )
    (comp (ref "C20")
      (value "2n")
      (footprint "eagle-import:C0603")
      (libsource (lib "eagle-import") (part "C-EUC0603"))
    )
    (comp (ref "C21")
      (value "100n")
      (footprint "eagle-import:C0603")
      (libsource (lib "eagle-import") (part "C-EUC0603"))
    )
    (comp (ref "C22")
      (value "C-EUC0603")
      (footprint "eagle-import:C0603")
      (libsource (lib "eagle-import") (part "C-EUC0603"))
    )
    (comp (ref "C23")
      (value "C-EUC0603")
      (footprint "eagle-import:C0603")
      (libsource (lib "eagle-import") (part "C-EUC0603"))
    )
    (comp (ref "C24")
      (value "C-EUC1210")
      (footprint "eagle-import:C1210")
      (libsource (lib "eagle-import") (part "C-EUC1210"))
    )
    (comp (ref "C25")
      (value "C-EUC1210")
      (footprint "eagle-import:C1210")
      (libsource (lib "eagle-import") (part "C-EUC1210"))
    )
    (comp (ref "C26")
      (value "C-EUC1210")
      (footprint "eagle-import:C1210")
      (libsource (lib "eagle-import") (part "C-EUC1210"))
    )
    (comp (ref "C27")
      (value "C-EUC1210")
      (footprint "eagle-import:C1210")
      (libsource (lib "eagle-import") (part "C-EUC1210"))
    )
    (comp (ref "C28")
      (value "4u7")
      (footprint "eagle-import:C1210")
      (libsource (lib "eagle-import") (part "C-EUC1210"))
    )
    (comp (ref "C29")
      (value "4u7")
      (footprint "eagle-import:C1210")
      (libsource (lib "eagle-import") (part "C-EUC1210"))
    )
    (comp (ref "C30")
      (value "10n")
      (footprint "eagle-import:C0603")
      (libsource (lib "eagle-import") (part "C-EUC0603"))
    )
    (comp (ref "C31")
      (value "2n")
      (footprint "eagle-import:C0603")
      (libsource (lib "eagle-import") (part "C-EUC0603"))
    )
    (comp (ref "C32")
      (value "100n")
      (footprint "eagle-import:C0603")
      (libsource (lib "eagle-import") (part "C-EUC0603"))
    )
    (comp (ref "C33")
      (value "C-EUC0603")
      (footprint "eagle-import:C0603")
      (libsource (lib "eagle-import") (part "C-EUC0603"))
    )
    (comp (ref "C34")
      (value "C-EUC0603")
      (footprint "eagle-import:C0603")
      (libsource (lib "eagle-import") (part "C-EUC0603"))
    )
    (comp (ref "D35")
      (value "SPARKFUN_DIODESMA")
      (footprint "eagle-import:SPARKFUN_SMA-DIODE")
      (libsource (lib "eagle-import") (part "SPARKFUN_DIODESMA"))
    )
    (comp (ref "D36")
      (value "SPARKFUN_DIODESMA")
      (footprint "eagle-import:SPARKFUN_SMA-DIODE")
      (libsource (lib "eagle-import") (part "SPARKFUN_DIODESMA"))
    )
    (comp (ref "J3")
      (value "3-1437664-0")
      (footprint "eagle-import:CONN-2")
      (libsource (lib "eagle-import") (part "3-1437664-0"))
    )
    (comp (ref "L1")
      (value "NR6045")
      (footprint "eagle-import:NR60XX")
      (libsource (lib "eagle-import") (part "NR6045"))
    )
    (comp (ref "L2")
      (value "NR6045")
      (footprint "eagle-import:NR60XX")
      (libsource (lib "eagle-import") (part "NR6045"))
    )
    (comp (ref "PWR")
      (value "LEDCHIPLED_0805")
      (footprint "eagle-import:CHIPLED_0805")
      (libsource (lib "eagle-import") (part "LEDCHIPLED_0805"))
    )
    (comp (ref "R21")
      (value "R-EU_R0603")
      (footprint "eagle-import:R0603")
      (libsource (lib "eagle-import") (part "R-EU_R0603"))
    )
    (comp (ref "R22")
      (value "R-EU_R0603")
      (footprint "eagle-import:R0603")
      (libsource (lib "eagle-import") (part "R-EU_R0603"))
    )
    (comp (ref "R23")
      (value "R-EU_R0603")
      (footprint "eagle-import:R0603")
      (libsource (lib "eagle-import") (part "R-EU_R0603"))
    )
    (comp (ref "R24")
      (value "R-EU_R0603")
      (footprint "eagle-import:R0603")
      (libsource (lib "eagle-import") (part "R-EU_R0603"))
    )
    (comp (ref "R26")
      (value "R-EU_R0603")
      (footprint "eagle-import:R0603")
      (libsource (lib "eagle-import") (part "R-EU_R0603"))
    )
    (comp (ref "R27")
      (value "R-EU_R0603")
      (footprint "eagle-import:R0603")
      (libsource (lib "eagle-import") (part "R-EU_R0603"))
    )
    (comp (ref "R28")
      (value "R-EU_R0603")
      (footprint "eagle-import:R0603")
      (libsource (lib "eagle-import") (part "R-EU_R0603"))
    )
    (comp (ref "R38")
      (value "R-EU_R0603")
      (footprint "eagle-import:R0603")
      (libsource (lib "eagle-import") (part "R-EU_R0603"))
    )
    (comp (ref "R39")
      (value "R-EU_R0603")
      (footprint "eagle-import:R0603")
      (libsource (lib "eagle-import") (part "R-EU_R0603"))
    )
    (comp (ref "REV")
      (value "LEDCHIPLED_0805")
      (footprint "eagle-import:CHIPLED_0805")
      (libsource (lib "eagle-import") (part "LEDCHIPLED_0805"))
    )
    (comp (ref "U14")
      (value "TPS54331")
      (footprint "eagle-import:SO08")
      (libsource (lib "eagle-import") (part "TPS54331"))
    )
    (comp (ref "U15")
      (value "TPS54331")
      (footprint "eagle-import:SO08")
      (libsource (lib "eagle-import") (part "TPS54331"))
    )
  )
  (nets
    (net (code "1") (name "+3V3") (class "Default")
      (node (ref "HTU21D") (pin "3V3") (pinfunction "1_3V3") (pintype "passive"))
      (node (ref "JP17") (pin "2") (pinfunction "2_2") (pintype "passive"))
      (node (ref "R19") (pin "2") (pinfunction "2_2") (pintype "passive"))
      (node (ref "R20") (pin "2") (pinfunction "2_2") (pintype "passive"))
      (node (ref "U2") (pin "3.3V") (pinfunction "3.3V_3.3V") (pintype "bidirectional"))
    )
    (net (code "2") (name "+5V") (class "Default")
      (node (ref "C13") (pin "2") (pinfunction "2_2") (pintype "passive"))
      (node (ref "C14") (pin "2") (pinfunction "2_2") (pintype "passive"))
      (node (ref "C15") (pin "2") (pinfunction "2_2") (pintype "passive"))
      (node (ref "C16") (pin "2") (pinfunction "2_2") (pintype "passive"))
      (node (ref "C5") (pin "2") (pinfunction "2_2") (pintype "passive"))
      (node (ref "C6") (pin "2") (pinfunction "2_2") (pintype "passive"))
      (node (ref "C7") (pin "2") (pinfunction "2_2") (pintype "passive"))
      (node (ref "C8") (pin "2") (pinfunction "2_2") (pintype "passive"))
      (node (ref "F1") (pin "1") (pinfunction "1_1") (pintype "passive"))
      (node (ref "F4") (pin "1") (pinfunction "1_1") (pintype "passive"))
      (node (ref "F5") (pin "1") (pinfunction "1_1") (pintype "passive"))
      (node (ref "F6") (pin "1") (pinfunction "1_1") (pintype "passive"))
      (node (ref "IMU") (pin "VIN") (pinfunction "1_VIN") (pintype "passive"))
      (node (ref "JP17") (pin "3") (pinfunction "3_3") (pintype "passive"))
      (node (ref "R11") (pin "5") (pinfunction "1_5") (pintype "passive"))
      (node (ref "R12") (pin "1") (pinfunction "1_1") (pintype "passive"))
      (node (ref "R13") (pin "1") (pinfunction "1_1") (pintype "passive"))
      (node (ref "R13") (pin "3") (pinfunction "1_3") (pintype "passive"))
      (node (ref "R14") (pin "5") (pinfunction "1_5") (pintype "passive"))
      (node (ref "R15") (pin "1") (pinfunction "1_1") (pintype "passive"))
      (node (ref "R15") (pin "7") (pinfunction "1_7") (pintype "passive"))
      (node (ref "R16") (pin "3") (pinfunction "1_3") (pintype "passive"))
      (node (ref "R3") (pin "1") (pinfunction "1_1") (pintype "passive"))
      (node (ref "R3") (pin "3") (pinfunction "1_3") (pintype "passive"))
      (node (ref "R4") (pin "5") (pinfunction "1_5") (pintype "passive"))
      (node (ref "R4") (pin "7") (pinfunction "1_7") (pintype "passive"))
      (node (ref "R6") (pin "5") (pinfunction "1_5") (pintype "passive"))
      (node (ref "R7") (pin "1") (pinfunction "1_1") (pintype "passive"))
      (node (ref "R8") (pin "1") (pinfunction "1_1") (pintype "passive"))
      (node (ref "R8") (pin "3") (pinfunction "1_3") (pintype "passive"))
      (node (ref "U10") (pin "8") (pinfunction "VCC_8") (pintype "bidirectional"))
      (node (ref "U11") (pin "8") (pinfunction "VCC_8") (pintype "bidirectional"))
      (node (ref "U12") (pin "8") (pinfunction "VCC_8") (pintype "bidirectional"))
      (node (ref "U13") (pin "8") (pinfunction "VCC_8") (pintype "bidirectional"))
      (node (ref "U2") (pin "5V@0") (pinfunction "5V_5V@0") (pintype "bidirectional"))
      (node (ref "U2") (pin "5V@1") (pinfunction "5V_5V@1") (pintype "bidirectional"))
      (node (ref "U2") (pin "5V@2") (pinfunction "5V_5V@2") (pintype "bidirectional"))
      (node (ref "U6") (pin "8") (pinfunction "VCC_8") (pintype "bidirectional"))
      (node (ref "U7") (pin "8") (pinfunction "VCC_8") (pintype "bidirectional"))
      (node (ref "U8") (pin "8") (pinfunction "VCC_8") (pintype "bidirectional"))
      (node (ref "U9") (pin "8") (pinfunction "VCC_8") (pintype "bidirectional"))
    )
    (net (code "3") (name "+5V{slash}1") (class "Default")
      (node (ref "C24") (pin "1") (pinfunction "1_1") (pintype "passive"))
      (node (ref "C25") (pin "1") (pinfunction "1_1") (pintype "passive"))
      (node (ref "L1") (pin "2") (pinfunction "2_2") (pintype "passive"))
      (node (ref "R22") (pin "2") (pinfunction "2_2") (pintype "passive"))
      (node (ref "R38") (pin "2") (pinfunction "2_2") (pintype "passive"))
      (node (ref "U$1") (pin "51") (pinfunction "VDD_5V_51") (pintype "power_in"))
      (node (ref "U$1") (pin "52") (pinfunction "VDD_5V_52") (pintype "power_in"))
      (node (ref "U$2") (pin "23") (pinfunction "23_23") (pintype "passive"))
      (node (ref "U$5") (pin "23") (pinfunction "23_23") (pintype "passive"))
    )
    (net (code "4") (name "+12V") (class "Default")
      (node (ref "C17") (pin "1") (pinfunction "1_1") (pintype "passive"))
      (node (ref "C18") (pin "1") (pinfunction "1_1") (pintype "passive"))
      (node (ref "C19") (pin "1") (pinfunction "1_1") (pintype "passive"))
      (node (ref "C28") (pin "1") (pinfunction "1_1") (pintype "passive"))
      (node (ref "C29") (pin "1") (pinfunction "1_1") (pintype "passive"))
      (node (ref "C30") (pin "1") (pinfunction "1_1") (pintype "passive"))
      (node (ref "D10") (pin "C") (pinfunction "C_C") (pintype "passive"))
      (node (ref "D12") (pin "C") (pinfunction "C_C") (pintype "passive"))
      (node (ref "D14") (pin "C") (pinfunction "C_C") (pintype "passive"))
      (node (ref "D16") (pin "C") (pinfunction "C_C") (pintype "passive"))
      (node (ref "D18") (pin "C") (pinfunction "C_C") (pintype "passive"))
      (node (ref "D20") (pin "C") (pinfunction "C_C") (pintype "passive"))
      (node (ref "D22") (pin "C") (pinfunction "C_C") (pintype "passive"))
      (node (ref "D24") (pin "C") (pinfunction "C_C") (pintype "passive"))
      (node (ref "D26") (pin "C") (pinfunction "C_C") (pintype "passive"))
      (node (ref "D28") (pin "C") (pinfunction "C_C") (pintype "passive"))
      (node (ref "D30") (pin "C") (pinfunction "C_C") (pintype "passive"))
      (node (ref "D32") (pin "C") (pinfunction "C_C") (pintype "passive"))
      (node (ref "D34") (pin "C") (pinfunction "C_C") (pintype "passive"))
      (node (ref "D4") (pin "C") (pinfunction "C_C") (pintype "passive"))
      (node (ref "D6") (pin "C") (pinfunction "C_C") (pintype "passive"))
      (node (ref "D8") (pin "C") (pinfunction "C_C") (pintype "passive"))
      (node (ref "J3") (pin "1") (pinfunction "1_1") (pintype "passive"))
      (node (ref "JP17") (pin "6") (pinfunction "6_6") (pintype "passive"))
      (node (ref "R10") (pin "2") (pinfunction "2_2") (pintype "passive"))
      (node (ref "R10") (pin "4") (pinfunction "2_4") (pintype "passive"))
      (node (ref "R10") (pin "6") (pinfunction "2_6") (pintype "passive"))
      (node (ref "R10") (pin "8") (pinfunction "2_8") (pintype "passive"))
      (node (ref "R17") (pin "2") (pinfunction "2_2") (pintype "passive"))
      (node (ref "R17") (pin "4") (pinfunction "2_4") (pintype "passive"))
      (node (ref "R17") (pin "6") (pinfunction "2_6") (pintype "passive"))
      (node (ref "R17") (pin "8") (pinfunction "2_8") (pintype "passive"))
      (node (ref "R18") (pin "2") (pinfunction "2_2") (pintype "passive"))
      (node (ref "R18") (pin "4") (pinfunction "2_4") (pintype "passive"))
      (node (ref "R18") (pin "6") (pinfunction "2_6") (pintype "passive"))
      (node (ref "R18") (pin "8") (pinfunction "2_8") (pintype "passive"))
      (node (ref "R24") (pin "2") (pinfunction "2_2") (pintype "passive"))
      (node (ref "R29") (pin "2") (pinfunction "2_2") (pintype "passive"))
      (node (ref "R9") (pin "2") (pinfunction "2_2") (pintype "passive"))
      (node (ref "R9") (pin "4") (pinfunction "2_4") (pintype "passive"))
      (node (ref "R9") (pin "6") (pinfunction "2_6") (pintype "passive"))
      (node (ref "R9") (pin "8") (pinfunction "2_8") (pintype "passive"))
      (node (ref "U1") (pin "1") (pinfunction "VCC_1") (pintype "bidirectional"))
      (node (ref "U1") (pin "14") (pinfunction "VCC_14") (pintype "bidirectional"))
      (node (ref "U1") (pin "15") (pinfunction "VCC_15") (pintype "bidirectional"))
      (node (ref "U1") (pin "28") (pinfunction "VCC_28") (pintype "bidirectional"))
      (node (ref "U14") (pin "2") (pinfunction "VIN_2") (pintype "bidirectional"))
      (node (ref "U15") (pin "2") (pinfunction "VIN_2") (pintype "bidirectional"))
      (node (ref "U2") (pin "VIN") (pinfunction "VIN_VIN") (pintype "bidirectional"))
      (node (ref "U3") (pin "1") (pinfunction "VCC_1") (pintype "bidirectional"))
      (node (ref "U3") (pin "14") (pinfunction "VCC_14") (pintype "bidirectional"))
      (node (ref "U3") (pin "15") (pinfunction "VCC_15") (pintype "bidirectional"))
      (node (ref "U3") (pin "28") (pinfunction "VCC_28") (pintype "bidirectional"))
      (node (ref "U4") (pin "1") (pinfunction "VCC_1") (pintype "bidirectional"))
      (node (ref "U4") (pin "14") (pinfunction "VCC_14") (pintype "bidirectional"))
      (node (ref "U4") (pin "15") (pinfunction "VCC_15") (pintype "bidirectional"))
      (node (ref "U4") (pin "28") (pinfunction "VCC_28") (pintype "bidirectional"))
      (node (ref "U5") (pin "1") (pinfunction "VCC_1") (pintype "bidirectional"))
      (node (ref "U5") (pin "14") (pinfunction "VCC_14") (pintype "bidirectional"))
      (node (ref "U5") (pin "15") (pinfunction "VCC_15") (pintype "bidirectional"))
      (node (ref "U5") (pin "28") (pinfunction "VCC_28") (pintype "bidirectional"))
    )
    (net (code "5") (name "7V4") (class "Default")
      (node (ref "C26") (pin "1") (pinfunction "1_1") (pintype "passive"))
      (node (ref "C27") (pin "1") (pinfunction "1_1") (pintype "passive"))
      (node (ref "F7") (pin "1") (pinfunction "1_1") (pintype "passive"))
      (node (ref "F8") (pin "1") (pinfunction "1_1") (pintype "passive"))
      (node (ref "F9") (pin "1") (pinfunction "1_1") (pintype "passive"))
      (node (ref "L2") (pin "2") (pinfunction "2_2") (pintype "passive"))
      (node (ref "R27") (pin "2") (pinfunction "2_2") (pintype "passive"))
      (node (ref "R39") (pin "2") (pinfunction "2_2") (pintype "passive"))
    )
    (net (code "6") (name "13") (class "Default")
      (node (ref "JP14") (pin "3") (pinfunction "3_3") (pintype "passive"))
      (node (ref "U2") (pin "13") (pinfunction "13_13") (pintype "bidirectional"))
    )
    (net (code "7") (name "AUX1") (class "Default")
      (node (ref "JP15") (pin "9") (pinfunction "9_9") (pintype "passive"))
      (node (ref "R11") (pin "1") (pinfunction "1_1") (pintype "passive"))
      (node (ref "U2") (pin "36") (pinfunction "36_36") (pintype "bidirectional"))
    )
    (net (code "8") (name "AUX1FB") (class "Default")
      (node (ref "JP16") (pin "9") (pinfunction "9_9") (pintype "passive"))
      (node (ref "R11") (pin "3") (pinfunction "1_3") (pintype "passive"))
      (node (ref "U2") (pin "37") (pinfunction "37_37") (pintype "bidirectional"))
    )
    (net (code "9") (name "AUX1I") (class "Default")
      (node (ref "JP12") (pin "7") (pinfunction "7_7") (pintype "passive"))
      (node (ref "U2") (pin "A9") (pinfunction "A9_A9") (pintype "bidirectional"))
      (node (ref "U6") (pin "7") (pinfunction "VIO_7") (pintype "bidirectional"))
    )
    (net (code "10") (name "AUX2") (class "Default")
      (node (ref "JP16") (pin "10") (pinfunction "10_10") (pintype "passive"))
      (node (ref "R12") (pin "3") (pinfunction "1_3") (pintype "passive"))
      (node (ref "U2") (pin "35") (pinfunction "35_35") (pintype "bidirectional"))
    )
    (net (code "11") (name "AUX2FB") (class "Default")
      (node (ref "JP15") (pin "10") (pinfunction "10_10") (pintype "passive"))
      (node (ref "R11") (pin "7") (pinfunction "1_7") (pintype "passive"))
      (node (ref "U2") (pin "34") (pinfunction "34_34") (pintype "bidirectional"))
    )
    (net (code "12") (name "AUX2I") (class "Default")
      (node (ref "JP12") (pin "8") (pinfunction "8_8") (pintype "passive"))
      (node (ref "U2") (pin "A8") (pinfunction "A8_A8") (pintype "bidirectional"))
      (node (ref "U7") (pin "7") (pinfunction "VIO_7") (pintype "bidirectional"))
    )
    (net (code "13") (name "AUX3") (class "Default")
      (node (ref "JP15") (pin "11") (pinfunction "11_11") (pintype "passive"))
      (node (ref "R12") (pin "5") (pinfunction "1_5") (pintype "passive"))
      (node (ref "U2") (pin "32") (pinfunction "32_32") (pintype "bidirectional"))
    )
    (net (code "14") (name "AUX3FB") (class "Default")
      (node (ref "JP16") (pin "11") (pinfunction "11_11") (pintype "passive"))
      (node (ref "R12") (pin "7") (pinfunction "1_7") (pintype "passive"))
      (node (ref "U2") (pin "33") (pinfunction "33_33") (pintype "bidirectional"))
    )
    (net (code "15") (name "AUX3I") (class "Default")
      (node (ref "JP11") (pin "1") (pinfunction "1_1") (pintype "passive"))
      (node (ref "U2") (pin "A7") (pinfunction "A7_A7") (pintype "bidirectional"))
      (node (ref "U8") (pin "7") (pinfunction "VIO_7") (pintype "bidirectional"))
    )
    (net (code "16") (name "AUX4") (class "Default")
      (node (ref "JP16") (pin "12") (pinfunction "12_12") (pintype "passive"))
      (node (ref "R13") (pin "7") (pinfunction "1_7") (pintype "passive"))
      (node (ref "U2") (pin "31") (pinfunction "31_31") (pintype "bidirectional"))
    )
    (net (code "17") (name "AUX4FB") (class "Default")
      (node (ref "JP15") (pin "12") (pinfunction "12_12") (pintype "passive"))
      (node (ref "R13") (pin "5") (pinfunction "1_5") (pintype "passive"))
      (node (ref "U2") (pin "30") (pinfunction "30_30") (pintype "bidirectional"))
    )
    (net (code "18") (name "AUX4I") (class "Default")
      (node (ref "JP11") (pin "2") (pinfunction "2_2") (pintype "passive"))
      (node (ref "U2") (pin "A6") (pinfunction "A6_A6") (pintype "bidirectional"))
      (node (ref "U9") (pin "7") (pinfunction "VIO_7") (pintype "bidirectional"))
    )
    (net (code "19") (name "AUX5") (class "Default")
      (node (ref "JP15") (pin "13") (pinfunction "13_13") (pintype "passive"))
      (node (ref "R14") (pin "1") (pinfunction "1_1") (pintype "passive"))
      (node (ref "U2") (pin "28") (pinfunction "28_28") (pintype "bidirectional"))
    )
    (net (code "20") (name "AUX5FB") (class "Default")
      (node (ref "JP16") (pin "13") (pinfunction "13_13") (pintype "passive"))
      (node (ref "R14") (pin "3") (pinfunction "1_3") (pintype "passive"))
      (node (ref "U2") (pin "29") (pinfunction "29_29") (pintype "bidirectional"))
    )
    (net (code "21") (name "AUX5I") (class "Default")
      (node (ref "JP11") (pin "3") (pinfunction "3_3") (pintype "passive"))
      (node (ref "U10") (pin "7") (pinfunction "VIO_7") (pintype "bidirectional"))
      (node (ref "U2") (pin "A5") (pinfunction "A5_A5") (pintype "bidirectional"))
    )
    (net (code "22") (name "AUX6") (class "Default")
      (node (ref "JP16") (pin "14") (pinfunction "14_14") (pintype "passive"))
      (node (ref "R15") (pin "3") (pinfunction "1_3") (pintype "passive"))
      (node (ref "U2") (pin "27") (pinfunction "27_27") (pintype "bidirectional"))
    )
    (net (code "23") (name "AUX6FB") (class "Default")
      (node (ref "JP15") (pin "14") (pinfunction "14_14") (pintype "passive"))
      (node (ref "R14") (pin "7") (pinfunction "1_7") (pintype "passive"))
      (node (ref "U2") (pin "26") (pinfunction "26_26") (pintype "bidirectional"))
    )
    (net (code "24") (name "AUX6I") (class "Default")
      (node (ref "JP11") (pin "4") (pinfunction "4_4") (pintype "passive"))
      (node (ref "U11") (pin "7") (pinfunction "VIO_7") (pintype "bidirectional"))
      (node (ref "U2") (pin "A4") (pinfunction "A4_A4") (pintype "bidirectional"))
    )
    (net (code "25") (name "AUX7") (class "Default")
      (node (ref "JP15") (pin "15") (pinfunction "15_15") (pintype "passive"))
      (node (ref "R15") (pin "5") (pinfunction "1_5") (pintype "passive"))
      (node (ref "U2") (pin "24") (pinfunction "24_24") (pintype "bidirectional"))
    )
    (net (code "26") (name "AUX7FB") (class "Default")
      (node (ref "JP16") (pin "15") (pinfunction "15_15") (pintype "passive"))
      (node (ref "R16") (pin "1") (pinfunction "1_1") (pintype "passive"))
      (node (ref "U2") (pin "25") (pinfunction "25_25") (pintype "bidirectional"))
    )
    (net (code "27") (name "AUX7I") (class "Default")
      (node (ref "JP11") (pin "5") (pinfunction "5_5") (pintype "passive"))
      (node (ref "U12") (pin "7") (pinfunction "VIO_7") (pintype "bidirectional"))
      (node (ref "U2") (pin "A3") (pinfunction "A3_A3") (pintype "bidirectional"))
    )
    (net (code "28") (name "AUX8") (class "Default")
      (node (ref "JP16") (pin "16") (pinfunction "16_16") (pintype "passive"))
      (node (ref "R16") (pin "7") (pinfunction "1_7") (pintype "passive"))
      (node (ref "U2") (pin "23") (pinfunction "23_23") (pintype "bidirectional"))
    )
    (net (code "29") (name "AUX8FB") (class "Default")
      (node (ref "JP15") (pin "16") (pinfunction "16_16") (pintype "passive"))
      (node (ref "R16") (pin "5") (pinfunction "1_5") (pintype "passive"))
      (node (ref "U2") (pin "22") (pinfunction "22_22") (pintype "bidirectional"))
    )
    (net (code "30") (name "AUX8I") (class "Default")
      (node (ref "JP11") (pin "6") (pinfunction "6_6") (pintype "passive"))
      (node (ref "U13") (pin "7") (pinfunction "VIO_7") (pintype "bidirectional"))
      (node (ref "U2") (pin "A2") (pinfunction "A2_A2") (pintype "bidirectional"))
    )
    (net (code "31") (name "GND") (class "Default")
      (node (ref "5V/1-STAT") (pin "C") (pinfunction "C_C") (pintype "passive"))
      (node (ref "7V4-STAT") (pin "C") (pinfunction "C_C") (pintype "passive"))
      (node (ref "C1") (pin "1") (pinfunction "1_1") (pintype "passive"))
      (node (ref "C10") (pin "1") (pinfunction "1_1") (pintype "passive"))
      (node (ref "C11") (pin "1") (pinfunction "1_1") (pintype "passive"))
      (node (ref "C12") (pin "1") (pinfunction "1_1") (pintype "passive"))
      (node (ref "C13") (pin "1") (pinfunction "1_1") (pintype "passive"))
      (node (ref "C14") (pin "1") (pinfunction "1_1") (pintype "passive"))
      (node (ref "C15") (pin "1") (pinfunction "1_1") (pintype "passive"))
      (node (ref "C16") (pin "1") (pinfunction "1_1") (pintype "passive"))
      (node (ref "C17") (pin "2") (pinfunction "2_2") (pintype "passive"))
      (node (ref "C18") (pin "2") (pinfunction "2_2") (pintype "passive"))
      (node (ref "C19") (pin "2") (pinfunction "2_2") (pintype "passive"))
      (node (ref "C2") (pin "1") (pinfunction "1_1") (pintype "passive"))
      (node (ref "C20") (pin "2") (pinfunction "2_2") (pintype "passive"))
      (node (ref "C23") (pin "2") (pinfunction "2_2") (pintype "passive"))
      (node (ref "C24") (pin "2") (pinfunction "2_2") (pintype "passive"))
      (node (ref "C25") (pin "2") (pinfunction "2_2") (pintype "passive"))
      (node (ref "C26") (pin "2") (pinfunction "2_2") (pintype "passive"))
      (node (ref "C27") (pin "2") (pinfunction "2_2") (pintype "passive"))
      (node (ref "C28") (pin "2") (pinfunction "2_2") (pintype "passive"))
      (node (ref "C29") (pin "2") (pinfunction "2_2") (pintype "passive"))
      (node (ref "C3") (pin "1") (pinfunction "1_1") (pintype "passive"))
      (node (ref "C30") (pin "2") (pinfunction "2_2") (pintype "passive"))
      (node (ref "C31") (pin "2") (pinfunction "2_2") (pintype "passive"))
      (node (ref "C34") (pin "2") (pinfunction "2_2") (pintype "passive"))
      (node (ref "C4") (pin "1") (pinfunction "1_1") (pintype "passive"))
      (node (ref "C5") (pin "1") (pinfunction "1_1") (pintype "passive"))
      (node (ref "C6") (pin "1") (pinfunction "1_1") (pintype "passive"))
      (node (ref "C7") (pin "1") (pinfunction "1_1") (pintype "passive"))
      (node (ref "C8") (pin "1") (pinfunction "1_1") (pintype "passive"))
      (node (ref "C9") (pin "1") (pinfunction "1_1") (pintype "passive"))
      (node (ref "D1") (pin "A") (pinfunction "A_A") (pintype "passive"))
      (node (ref "D11") (pin "A") (pinfunction "A_A") (pintype "passive"))
      (node (ref "D13") (pin "A") (pinfunction "A_A") (pintype "passive"))
      (node (ref "D15") (pin "A") (pinfunction "A_A") (pintype "passive"))
      (node (ref "D17") (pin "A") (pinfunction "A_A") (pintype "passive"))
      (node (ref "D19") (pin "A") (pinfunction "A_A") (pintype "passive"))
      (node (ref "D2") (pin "A") (pinfunction "A_A") (pintype "passive"))
      (node (ref "D21") (pin "A") (pinfunction "A_A") (pintype "passive"))
      (node (ref "D23") (pin "A") (pinfunction "A_A") (pintype "passive"))
      (node (ref "D25") (pin "A") (pinfunction "A_A") (pintype "passive"))
      (node (ref "D27") (pin "A") (pinfunction "A_A") (pintype "passive"))
      (node (ref "D29") (pin "A") (pinfunction "A_A") (pintype "passive"))
      (node (ref "D3") (pin "A") (pinfunction "A_A") (pintype "passive"))
      (node (ref "D31") (pin "A") (pinfunction "A_A") (pintype "passive"))
      (node (ref "D33") (pin "A") (pinfunction "A_A") (pintype "passive"))
      (node (ref "D35") (pin "A") (pinfunction "A_A") (pintype "passive"))
      (node (ref "D36") (pin "A") (pinfunction "A_A") (pintype "passive"))
      (node (ref "D5") (pin "A") (pinfunction "A_A") (pintype "passive"))
      (node (ref "D7") (pin "A") (pinfunction "A_A") (pintype "passive"))
      (node (ref "D9") (pin "A") (pinfunction "A_A") (pintype "passive"))
      (node (ref "GPS") (pin "GND") (pinfunction "6_GND") (pintype "passive"))
      (node (ref "GPS") (pin "MNT@0") (pinfunction "9_MNT@0") (pintype "passive"))
      (node (ref "GPS") (pin "MNT@1") (pinfunction "9_MNT@1") (pintype "passive"))
      (node (ref "H1") (pin "B3,2") (pinfunction "MOUNT_B3,2") (pintype "passive"))
      (node (ref "H2") (pin "B3,2") (pinfunction "MOUNT_B3,2") (pintype "passive"))
      (node (ref "H3") (pin "B3,2") (pinfunction "MOUNT_B3,2") (pintype "passive"))
      (node (ref "H4") (pin "B3,2") (pinfunction "MOUNT_B3,2") (pintype "passive"))
      (node (ref "H5") (pin "B5,5") (pinfunction "MOUNT_B5,5") (pintype "passive"))
      (node (ref "H6") (pin "B5,5") (pinfunction "MOUNT_B5,5") (pintype "passive"))
      (node (ref "H7") (pin "B3,2") (pinfunction "MOUNT_B3,2") (pintype "passive"))
      (node (ref "HTU21D") (pin "GND") (pinfunction "2_GND") (pintype "passive"))
      (node (ref "I1/V2") (pin "4") (pinfunction "4_4") (pintype "passive"))
      (node (ref "I2/V3") (pin "4") (pinfunction "4_4") (pintype "passive"))
      (node (ref "I3/V4") (pin "4") (pinfunction "4_4") (pintype "passive"))
      (node (ref "I4") (pin "4") (pinfunction "4_4") (pintype "passive"))
      (node (ref "IMU") (pin "GND") (pinfunction "3_GND") (pintype "passive"))
      (node (ref "IMU") (pin "MNT@0") (pinfunction "9_MNT@0") (pintype "passive"))
      (node (ref "IMU") (pin "MNT@1") (pinfunction "9_MNT@1") (pintype "passive"))
      (node (ref "IMU") (pin "MNT@2") (pinfunction "9_MNT@2") (pintype "passive"))
      (node (ref "IMU") (pin "MNT@3") (pinfunction "9_MNT@3") (pintype "passive"))
      (node (ref "J3") (pin "2") (pinfunction "2_2") (pintype "passive"))
      (node (ref "JP17") (pin "4") (pinfunction "4_4") (pintype "passive"))
      (node (ref "JP17") (pin "5") (pinfunction "5_5") (pintype "passive"))
      (node (ref "PWR") (pin "C") (pinfunction "C_C") (pintype "passive"))
      (node (ref "R21") (pin "1") (pinfunction "1_1") (pintype "passive"))
      (node (ref "R23") (pin "1") (pinfunction "1_1") (pintype "passive"))
      (node (ref "R25") (pin "1") (pinfunction "1_1") (pintype "passive"))
      (node (ref "R26") (pin "1") (pinfunction "1_1") (pintype "passive"))
      (node (ref "R28") (pin "1") (pinfunction "1_1") (pintype "passive"))
      (node (ref "R30") (pin "1") (pinfunction "1_1") (pintype "passive"))
      (node (ref "R31") (pin "1") (pinfunction "1_1") (pintype "passive"))
      (node (ref "R32") (pin "1") (pinfunction "1_1") (pintype "passive"))
      (node (ref "R33") (pin "1") (pinfunction "1_1") (pintype "passive"))
      (node (ref "R34") (pin "1") (pinfunction "1_1") (pintype "passive"))
      (node (ref "R35") (pin "1") (pinfunction "1_1") (pintype "passive"))
      (node (ref "R36") (pin "1") (pinfunction "1_1") (pintype "passive"))
      (node (ref "R37") (pin "1") (pinfunction "1_1") (pintype "passive"))
      (node (ref "REV") (pin "A") (pinfunction "A_A") (pintype "passive"))
      (node (ref "SERVO_AUX1") (pin "1") (pinfunction "1_1") (pintype "passive"))
      (node (ref "SERVO_AUX2") (pin "1") (pinfunction "1_1") (pintype "passive"))
      (node (ref "STEERING") (pin "1") (pinfunction "1_1") (pintype "passive"))
      (node (ref "U$1") (pin "1") (pinfunction "GND_1") (pintype "power_in"))
      (node (ref "U$1") (pin "2") (pinfunction "GND_2") (pintype "power_in"))
      (node (ref "U$1") (pin "47") (pinfunction "GND_47") (pintype "power_in"))
      (node (ref "U$1") (pin "48") (pinfunction "GND_48") (pintype "power_in"))
      (node (ref "U$1") (pin "80") (pinfunction "GNDA_ADC_80") (pintype "passive"))
      (node (ref "U$1") (pin "89") (pinfunction "GND_89") (pintype "power_in"))
      (node (ref "U$1") (pin "90") (pinfunction "GND_90") (pintype "power_in"))
      (node (ref "U$1") (pin "91") (pinfunction "GND_91") (pintype "power_in"))
      (node (ref "U$1") (pin "92") (pinfunction "GND_92") (pintype "power_in"))
      (node (ref "U$2") (pin "25") (pinfunction "25_25") (pintype "passive"))
      (node (ref "U$2") (pin "3") (pinfunction "3_3") (pintype "passive"))
      (node (ref "U$2") (pin "4") (pinfunction "4_4") (pintype "passive"))
      (node (ref "U$2") (pin "9") (pinfunction "9_9") (pintype "passive"))
      (node (ref "U$3") (pin "24") (pinfunction "24_24") (pintype "passive"))
      (node (ref "U$4") (pin "24") (pinfunction "24_24") (pintype "passive"))
      (node (ref "U$5") (pin "25") (pinfunction "25_25") (pintype "passive"))
      (node (ref "U$5") (pin "3") (pinfunction "3_3") (pintype "passive"))
      (node (ref "U$5") (pin "4") (pinfunction "4_4") (pintype "passive"))
      (node (ref "U1") (pin "13") (pinfunction "GND_13") (pintype "bidirectional"))
      (node (ref "U1") (pin "2") (pinfunction "GND_2") (pintype "bidirectional"))
      (node (ref "U1") (pin "7") (pinfunction "GND_7") (pintype "bidirectional"))
      (node (ref "U1") (pin "8") (pinfunction "GND_8") (pintype "bidirectional"))
      (node (ref "U10") (pin "5") (pinfunction "GND_5") (pintype "bidirectional"))
      (node (ref "U11") (pin "5") (pinfunction "GND_5") (pintype "bidirectional"))
      (node (ref "U12") (pin "5") (pinfunction "GND_5") (pintype "bidirectional"))
      (node (ref "U13") (pin "5") (pinfunction "GND_5") (pintype "bidirectional"))
      (node (ref "U14") (pin "7") (pinfunction "GND_7") (pintype "bidirectional"))
      (node (ref "U15") (pin "7") (pinfunction "GND_7") (pintype "bidirectional"))
      (node (ref "U2") (pin "GND@0") (pinfunction "GND_GND@0") (pintype "bidirectional"))
      (node (ref "U2") (pin "GND@1") (pinfunction "GND_GND@1") (pintype "bidirectional"))
      (node (ref "U2") (pin "GND@2") (pinfunction "GND_GND@2") (pintype "bidirectional"))
      (node (ref "U2") (pin "GND@3") (pinfunction "GND_GND@3") (pintype "bidirectional"))
      (node (ref "U2") (pin "GND@4") (pinfunction "GND_GND@4") (pintype "bidirectional"))
      (node (ref "U3") (pin "13") (pinfunction "GND_13") (pintype "bidirectional"))
      (node (ref "U3") (pin "2") (pinfunction "GND_2") (pintype "bidirectional"))
      (node (ref "U3") (pin "7") (pinfunction "GND_7") (pintype "bidirectional"))
      (node (ref "U3") (pin "8") (pinfunction "GND_8") (pintype "bidirectional"))
      (node (ref "U4") (pin "13") (pinfunction "GND_13") (pintype "bidirectional"))
      (node (ref "U4") (pin "2") (pinfunction "GND_2") (pintype "bidirectional"))
      (node (ref "U4") (pin "7") (pinfunction "GND_7") (pintype "bidirectional"))
      (node (ref "U4") (pin "8") (pinfunction "GND_8") (pintype "bidirectional"))
      (node (ref "U5") (pin "13") (pinfunction "GND_13") (pintype "bidirectional"))
      (node (ref "U5") (pin "2") (pinfunction "GND_2") (pintype "bidirectional"))
      (node (ref "U5") (pin "7") (pinfunction "GND_7") (pintype "bidirectional"))
      (node (ref "U5") (pin "8") (pinfunction "GND_8") (pintype "bidirectional"))
      (node (ref "U6") (pin "5") (pinfunction "GND_5") (pintype "bidirectional"))
      (node (ref "U7") (pin "5") (pinfunction "GND_5") (pintype "bidirectional"))
      (node (ref "U8") (pin "5") (pinfunction "GND_5") (pintype "bidirectional"))
      (node (ref "U9") (pin "5") (pinfunction "GND_5") (pintype "bidirectional"))
    )
    (net (code "32") (name "GNSS_RX") (class "Default")
      (node (ref "GPS") (pin "RX") (pinfunction "2_RX") (pintype "passive"))
      (node (ref "U$1") (pin "59") (pinfunction "UART4_TXD_59") (pintype "passive"))
      (node (ref "U$5") (pin "19") (pinfunction "19_19") (pintype "passive"))
    )
    (net (code "33") (name "GNSS_TX") (class "Default")
      (node (ref "GPS") (pin "TX") (pinfunction "3_TX") (pintype "passive"))
      (node (ref "U$1") (pin "57") (pinfunction "UART4_RXD_57") (pintype "passive"))
      (node (ref "U$5") (pin "20") (pinfunction "20_20") (pintype "passive"))
    )
    (net (code "34") (name "I1") (class "Default")
      (node (ref "I1/V2") (pin "2") (pinfunction "2_2") (pintype "passive"))
      (node (ref "JP12") (pin "6") (pinfunction "6_6") (pintype "passive"))
      (node (ref "U2") (pin "A10") (pinfunction "A10_A10") (pintype "bidirectional"))
    )
    (net (code "35") (name "I2") (class "Default")
      (node (ref "I2/V3") (pin "2") (pinfunction "2_2") (pintype "passive"))
      (node (ref "JP12") (pin "3") (pinfunction "3_3") (pintype "passive"))
      (node (ref "U2") (pin "A13") (pinfunction "A13_A13") (pintype "bidirectional"))
    )
    (net (code "36") (name "I3") (class "Default")
      (node (ref "I3/V4") (pin "2") (pinfunction "2_2") (pintype "passive"))
      (node (ref "JP12") (pin "4") (pinfunction "4_4") (pintype "passive"))
      (node (ref "U2") (pin "A12") (pinfunction "A12_A12") (pintype "bidirectional"))
    )
    (net (code "37") (name "I4") (class "Default")
      (node (ref "I4") (pin "2") (pinfunction "2_2") (pintype "passive"))
      (node (ref "JP12") (pin "5") (pinfunction "5_5") (pintype "passive"))
      (node (ref "U2") (pin "A11") (pinfunction "A11_A11") (pintype "bidirectional"))
    )
    (net (code "38") (name "Net-(5V/1-STAT-PadA)") (class "Default")
      (node (ref "5V/1-STAT") (pin "A") (pinfunction "A_A") (pintype "passive"))
      (node (ref "R38") (pin "1") (pinfunction "1_1") (pintype "passive"))
    )
    (net (code "39") (name "Net-(7V4-STAT-PadA)") (class "Default")
      (node (ref "7V4-STAT") (pin "A") (pinfunction "A_A") (pintype "passive"))
      (node (ref "R39") (pin "1") (pinfunction "1_1") (pintype "passive"))
    )
    (net (code "40") (name "Net-(AUXA-K)") (class "Default")
      (node (ref "AUX") (pin "1") (pinfunction "K_1") (pintype "passive"))
      (node (ref "U6") (pin "3") (pinfunction "IP-_3") (pintype "bidirectional"))
      (node (ref "U6") (pin "4") (pinfunction "IP-_4") (pintype "bidirectional"))
    )
    (net (code "41") (name "Net-(AUXB-K)") (class "Default")
      (node (ref "AUX") (pin "2") (pinfunction "K_2") (pintype "passive"))
      (node (ref "U7") (pin "3") (pinfunction "IP-_3") (pintype "bidirectional"))
      (node (ref "U7") (pin "4") (pinfunction "IP-_4") (pintype "bidirectional"))
    )
    (net (code "42") (name "Net-(AUXC-K)") (class "Default")
      (node (ref "AUX") (pin "3") (pinfunction "K_3") (pintype "passive"))
      (node (ref "U8") (pin "3") (pinfunction "IP-_3") (pintype "bidirectional"))
      (node (ref "U8") (pin "4") (pinfunction "IP-_4") (pintype "bidirectional"))
    )
    (net (code "43") (name "Net-(AUXD-K)") (class "Default")
      (node (ref "AUX") (pin "4") (pinfunction "K_4") (pintype "passive"))
      (node (ref "U9") (pin "3") (pinfunction "IP-_3") (pintype "bidirectional"))
      (node (ref "U9") (pin "4") (pinfunction "IP-_4") (pintype "bidirectional"))
    )
    (net (code "44") (name "Net-(AUXE-K)") (class "Default")
      (node (ref "AUX") (pin "5") (pinfunction "K_5") (pintype "passive"))
      (node (ref "U10") (pin "3") (pinfunction "IP-_3") (pintype "bidirectional"))
      (node (ref "U10") (pin "4") (pinfunction "IP-_4") (pintype "bidirectional"))
    )
    (net (code "45") (name "Net-(AUXF-K)") (class "Default")
      (node (ref "AUX") (pin "6") (pinfunction "K_6") (pintype "passive"))
      (node (ref "U11") (pin "3") (pinfunction "IP-_3") (pintype "bidirectional"))
      (node (ref "U11") (pin "4") (pinfunction "IP-_4") (pintype "bidirectional"))
    )
    (net (code "46") (name "Net-(AUXG-K)") (class "Default")
      (node (ref "AUX") (pin "7") (pinfunction "K_7") (pintype "passive"))
      (node (ref "U12") (pin "3") (pinfunction "IP-_3") (pintype "bidirectional"))
      (node (ref "U12") (pin "4") (pinfunction "IP-_4") (pintype "bidirectional"))
    )
    (net (code "47") (name "Net-(AUXH-K)") (class "Default")
      (node (ref "AUX") (pin "8") (pinfunction "K_8") (pintype "passive"))
      (node (ref "U13") (pin "3") (pinfunction "IP-_3") (pintype "bidirectional"))
      (node (ref "U13") (pin "4") (pinfunction "IP-_4") (pintype "bidirectional"))
    )
    (net (code "48") (name "Net-(C22-Pad2)") (class "Default")
      (node (ref "C22") (pin "2") (pinfunction "2_2") (pintype "passive"))
      (node (ref "R21") (pin "2") (pinfunction "2_2") (pintype "passive"))
    )
    (net (code "49") (name "Net-(C33-Pad2)") (class "Default")
      (node (ref "C33") (pin "2") (pinfunction "2_2") (pintype "passive"))
      (node (ref "R26") (pin "2") (pinfunction "2_2") (pintype "passive"))
    )
    (net (code "50") (name "Net-(D25-PadC)") (class "Default")
      (node (ref "D25") (pin "C") (pinfunction "C_C") (pintype "passive"))
      (node (ref "D26") (pin "A") (pinfunction "A_A") (pintype "passive"))
      (node (ref "R17") (pin "1") (pinfunction "1_1") (pintype "passive"))
      (node (ref "U4") (pin "16") (pinfunction "OUT4_16") (pintype "bidirectional"))
      (node (ref "U4") (pin "17") (pinfunction "OUT4_17") (pintype "bidirectional"))
      (node (ref "U4") (pin "18") (pinfunction "OUT4_18") (pintype "bidirectional"))
      (node (ref "U9") (pin "1") (pinfunction "IP+_1") (pintype "bidirectional"))
      (node (ref "U9") (pin "2") (pinfunction "IP+_2") (pintype "bidirectional"))
    )
    (net (code "51") (name "Net-(D33-PadC)") (class "Default")
      (node (ref "D33") (pin "C") (pinfunction "C_C") (pintype "passive"))
      (node (ref "D34") (pin "A") (pinfunction "A_A") (pintype "passive"))
      (node (ref "R18") (pin "1") (pinfunction "1_1") (pintype "passive"))
      (node (ref "U13") (pin "1") (pinfunction "IP+_1") (pintype "bidirectional"))
      (node (ref "U13") (pin "2") (pinfunction "IP+_2") (pintype "bidirectional"))
      (node (ref "U5") (pin "16") (pinfunction "OUT4_16") (pintype "bidirectional"))
      (node (ref "U5") (pin "17") (pinfunction "OUT4_17") (pintype "bidirectional"))
      (node (ref "U5") (pin "18") (pinfunction "OUT4_18") (pintype "bidirectional"))
    )
    (net (code "52") (name "Net-(F1-Pad2)") (class "Default")
      (node (ref "F1") (pin "2") (pinfunction "2_2") (pintype "passive"))
      (node (ref "I1/V2") (pin "1") (pinfunction "1_1") (pintype "passive"))
    )
    (net (code "53") (name "Net-(F4-Pad2)") (class "Default")
      (node (ref "F4") (pin "2") (pinfunction "2_2") (pintype "passive"))
      (node (ref "I2/V3") (pin "1") (pinfunction "1_1") (pintype "passive"))
    )
    (net (code "54") (name "Net-(F5-Pad2)") (class "Default")
      (node (ref "F5") (pin "2") (pinfunction "2_2") (pintype "passive"))
      (node (ref "I3/V4") (pin "1") (pinfunction "1_1") (pintype "passive"))
    )
    (net (code "55") (name "Net-(F6-Pad2)") (class "Default")
      (node (ref "F6") (pin "2") (pinfunction "2_2") (pintype "passive"))
      (node (ref "I4") (pin "1") (pinfunction "1_1") (pintype "passive"))
    )
    (net (code "56") (name "Net-(F7-Pad2)") (class "Default")
      (node (ref "F7") (pin "2") (pinfunction "2_2") (pintype "passive"))
      (node (ref "SERVO_AUX1") (pin "2") (pinfunction "2_2") (pintype "passive"))
    )
    (net (code "57") (name "Net-(F8-Pad2)") (class "Default")
      (node (ref "F8") (pin "2") (pinfunction "2_2") (pintype "passive"))
      (node (ref "SERVO_AUX2") (pin "2") (pinfunction "2_2") (pintype "passive"))
    )
    (net (code "58") (name "Net-(F9-Pad2)") (class "Default")
      (node (ref "F9") (pin "2") (pinfunction "2_2") (pintype "passive"))
      (node (ref "STEERING") (pin "2") (pinfunction "2_2") (pintype "passive"))
    )
    (net (code "59") (name "Net-(JP10-Pad1)") (class "Default")
      (node (ref "JP10") (pin "1") (pinfunction "1_1") (pintype "passive"))
      (node (ref "U2") (pin "7") (pinfunction "7_7") (pintype "bidirectional"))
    )
    (net (code "60") (name "Net-(JP10-Pad2)") (class "Default")
      (node (ref "JP10") (pin "2") (pinfunction "2_2") (pintype "passive"))
      (node (ref "U2") (pin "6") (pinfunction "6_6") (pintype "bidirectional"))
    )
    (net (code "61") (name "Net-(JP11-Pad8)") (class "Default")
      (node (ref "JP11") (pin "8") (pinfunction "8_8") (pintype "passive"))
      (node (ref "R29") (pin "1") (pinfunction "1_1") (pintype "passive"))
      (node (ref "R30") (pin "2") (pinfunction "2_2") (pintype "passive"))
      (node (ref "U2") (pin "A0") (pinfunction "A0_A0") (pintype "bidirectional"))
    )
    (net (code "62") (name "Net-(JP14-Pad4)") (class "Default")
      (node (ref "JP14") (pin "4") (pinfunction "4_4") (pintype "passive"))
      (node (ref "U2") (pin "12") (pinfunction "12_12") (pintype "bidirectional"))
    )
    (net (code "63") (name "Net-(JP14-Pad5)") (class "Default")
      (node (ref "JP14") (pin "5") (pinfunction "5_5") (pintype "passive"))
      (node (ref "U2") (pin "11") (pinfunction "11_11") (pintype "bidirectional"))
    )
    (net (code "64") (name "Net-(JP14-Pad6)") (class "Default")
      (node (ref "JP14") (pin "6") (pinfunction "6_6") (pintype "passive"))
      (node (ref "U2") (pin "10") (pinfunction "10_10") (pintype "bidirectional"))
    )
    (net (code "65") (name "Net-(JP14-Pad7)") (class "Default")
      (node (ref "JP14") (pin "7") (pinfunction "7_7") (pintype "passive"))
      (node (ref "U2") (pin "9") (pinfunction "9_9") (pintype "bidirectional"))
    )
    (net (code "66") (name "Net-(JP14-Pad8)") (class "Default")
      (node (ref "JP14") (pin "8") (pinfunction "8_8") (pintype "passive"))
      (node (ref "U2") (pin "8") (pinfunction "8_8") (pintype "bidirectional"))
    )
    (net (code "67") (name "Net-(LED3-PadC)") (class "Default")
      (node (ref "LED3") (pin "C") (pinfunction "C_C") (pintype "passive"))
      (node (ref "R25") (pin "2") (pinfunction "2_2") (pintype "passive"))
    )
    (net (code "68") (name "Net-(LED4-PadC)") (class "Default")
      (node (ref "LED4") (pin "C") (pinfunction "C_C") (pintype "passive"))
      (node (ref "R31") (pin "2") (pinfunction "2_2") (pintype "passive"))
    )
    (net (code "69") (name "Net-(LED5-PadC)") (class "Default")
      (node (ref "LED5") (pin "C") (pinfunction "C_C") (pintype "passive"))
      (node (ref "R32") (pin "2") (pinfunction "2_2") (pintype "passive"))
    )
    (net (code "70") (name "Net-(LED6-PadC)") (class "Default")
      (node (ref "LED6") (pin "C") (pinfunction "C_C") (pintype "passive"))
      (node (ref "R33") (pin "2") (pinfunction "2_2") (pintype "passive"))
    )
    (net (code "71") (name "Net-(LED7-PadC)") (class "Default")
      (node (ref "LED7") (pin "C") (pinfunction "C_C") (pintype "passive"))
      (node (ref "R34") (pin "2") (pinfunction "2_2") (pintype "passive"))
    )
    (net (code "72") (name "Net-(LED8-PadC)") (class "Default")
      (node (ref "LED8") (pin "C") (pinfunction "C_C") (pintype "passive"))
      (node (ref "R35") (pin "2") (pinfunction "2_2") (pintype "passive"))
    )
    (net (code "73") (name "Net-(LED9-PadC)") (class "Default")
      (node (ref "LED9") (pin "C") (pinfunction "C_C") (pintype "passive"))
      (node (ref "R36") (pin "2") (pinfunction "2_2") (pintype "passive"))
    )
    (net (code "74") (name "Net-(LED10-PadC)") (class "Default")
      (node (ref "LED10") (pin "C") (pinfunction "C_C") (pintype "passive"))
      (node (ref "R37") (pin "2") (pinfunction "2_2") (pintype "passive"))
    )
    (net (code "75") (name "Net-(PWR-PadA)") (class "Default")
      (node (ref "PWR") (pin "A") (pinfunction "A_A") (pintype "passive"))
      (node (ref "R24") (pin "1") (pinfunction "1_1") (pintype "passive"))
      (node (ref "REV") (pin "C") (pinfunction "C_C") (pintype "passive"))
    )
    (net (code "76") (name "Net-(R3B-2)") (class "Default")
      (node (ref "R3") (pin "4") (pinfunction "2_4") (pintype "passive"))
      (node (ref "R3") (pin "6") (pinfunction "2_6") (pintype "passive"))
      (node (ref "U1") (pin "11") (pinfunction "DG4_11") (pintype "bidirectional"))
    )
    (net (code "77") (name "Net-(R3D-2)") (class "Default")
      (node (ref "R3") (pin "8") (pinfunction "2_8") (pintype "passive"))
      (node (ref "U1") (pin "12") (pinfunction "IN4_12") (pintype "bidirectional"))
    )
    (net (code "78") (name "Net-(R4B-2)") (class "Default")
      (node (ref "R4") (pin "4") (pinfunction "2_4") (pintype "passive"))
      (node (ref "R4") (pin "6") (pinfunction "2_6") (pintype "passive"))
      (node (ref "U1") (pin "4") (pinfunction "DG1_4") (pintype "bidirectional"))
    )
    (net (code "79") (name "Net-(R4D-2)") (class "Default")
      (node (ref "R4") (pin "8") (pinfunction "2_8") (pintype "passive"))
      (node (ref "R5") (pin "2") (pinfunction "2_2") (pintype "passive"))
      (node (ref "U1") (pin "5") (pinfunction "DG2_5") (pintype "bidirectional"))
    )
    (net (code "80") (name "Net-(R5B-2)") (class "Default")
      (node (ref "R5") (pin "4") (pinfunction "2_4") (pintype "passive"))
      (node (ref "U1") (pin "6") (pinfunction "IN2_6") (pintype "bidirectional"))
    )
    (net (code "81") (name "Net-(R5C-2)") (class "Default")
      (node (ref "R5") (pin "6") (pinfunction "2_6") (pintype "passive"))
      (node (ref "U1") (pin "9") (pinfunction "IN3_9") (pintype "bidirectional"))
    )
    (net (code "82") (name "Net-(R5D-2)") (class "Default")
      (node (ref "R3") (pin "2") (pinfunction "2_2") (pintype "passive"))
      (node (ref "R5") (pin "8") (pinfunction "2_8") (pintype "passive"))
      (node (ref "U1") (pin "10") (pinfunction "DG3_10") (pintype "bidirectional"))
    )
    (net (code "83") (name "Net-(R6B-2)") (class "Default")
      (node (ref "R6") (pin "4") (pinfunction "2_4") (pintype "passive"))
      (node (ref "R6") (pin "6") (pinfunction "2_6") (pintype "passive"))
      (node (ref "U3") (pin "4") (pinfunction "DG1_4") (pintype "bidirectional"))
    )
    (net (code "84") (name "Net-(R6D-2)") (class "Default")
      (node (ref "R6") (pin "8") (pinfunction "2_8") (pintype "passive"))
      (node (ref "R7") (pin "2") (pinfunction "2_2") (pintype "passive"))
      (node (ref "U3") (pin "5") (pinfunction "DG2_5") (pintype "bidirectional"))
    )
    (net (code "85") (name "Net-(R7B-2)") (class "Default")
      (node (ref "R7") (pin "4") (pinfunction "2_4") (pintype "passive"))
      (node (ref "U3") (pin "6") (pinfunction "IN2_6") (pintype "bidirectional"))
    )
    (net (code "86") (name "Net-(R7C-2)") (class "Default")
      (node (ref "R7") (pin "6") (pinfunction "2_6") (pintype "passive"))
      (node (ref "U3") (pin "9") (pinfunction "IN3_9") (pintype "bidirectional"))
    )
    (net (code "87") (name "Net-(R7D-2)") (class "Default")
      (node (ref "R7") (pin "8") (pinfunction "2_8") (pintype "passive"))
      (node (ref "R8") (pin "2") (pinfunction "2_2") (pintype "passive"))
      (node (ref "U3") (pin "10") (pinfunction "DG3_10") (pintype "bidirectional"))
    )
    (net (code "88") (name "Net-(R8B-2)") (class "Default")
      (node (ref "R8") (pin "4") (pinfunction "2_4") (pintype "passive"))
      (node (ref "R8") (pin "6") (pinfunction "2_6") (pintype "passive"))
      (node (ref "U3") (pin "11") (pinfunction "DG4_11") (pintype "bidirectional"))
    )
    (net (code "89") (name "Net-(R8D-2)") (class "Default")
      (node (ref "R8") (pin "8") (pinfunction "2_8") (pintype "passive"))
      (node (ref "U3") (pin "12") (pinfunction "IN4_12") (pintype "bidirectional"))
    )
    (net (code "90") (name "Net-(R9B-1)") (class "Default")
      (node (ref "D7") (pin "C") (pinfunction "C_C") (pintype "passive"))
      (node (ref "D8") (pin "A") (pinfunction "A_A") (pintype "passive"))
      (node (ref "LED5") (pin "A") (pinfunction "A_A") (pintype "passive"))
      (node (ref "R9") (pin "3") (pinfunction "1_3") (pintype "passive"))
      (node (ref "RELAY") (pin "3") (pinfunction "K_3") (pintype "passive"))
      (node (ref "U1") (pin "19") (pinfunction "OUT3_19") (pintype "bidirectional"))
      (node (ref "U1") (pin "20") (pinfunction "OUT3_20") (pintype "bidirectional"))
      (node (ref "U1") (pin "21") (pinfunction "OUT3_21") (pintype "bidirectional"))
    )
    (net (code "91") (name "Net-(R9C-1)") (class "Default")
      (node (ref "D5") (pin "C") (pinfunction "C_C") (pintype "passive"))
      (node (ref "D6") (pin "A") (pinfunction "A_A") (pintype "passive"))
      (node (ref "LED4") (pin "A") (pinfunction "A_A") (pintype "passive"))
      (node (ref "R9") (pin "5") (pinfunction "1_5") (pintype "passive"))
      (node (ref "RELAY") (pin "2") (pinfunction "K_2") (pintype "passive"))
      (node (ref "U1") (pin "22") (pinfunction "OUT2_22") (pintype "bidirectional"))
      (node (ref "U1") (pin "23") (pinfunction "OUT2_23") (pintype "bidirectional"))
      (node (ref "U1") (pin "24") (pinfunction "OUT2_24") (pintype "bidirectional"))
    )
    (net (code "92") (name "Net-(R9D-1)") (class "Default")
      (node (ref "D3") (pin "C") (pinfunction "C_C") (pintype "passive"))
      (node (ref "D4") (pin "A") (pinfunction "A_A") (pintype "passive"))
      (node (ref "LED3") (pin "A") (pinfunction "A_A") (pintype "passive"))
      (node (ref "R9") (pin "7") (pinfunction "1_7") (pintype "passive"))
      (node (ref "RELAY") (pin "1") (pinfunction "K_1") (pintype "passive"))
      (node (ref "U1") (pin "25") (pinfunction "OUT1_25") (pintype "bidirectional"))
      (node (ref "U1") (pin "26") (pinfunction "OUT1_26") (pintype "bidirectional"))
      (node (ref "U1") (pin "27") (pinfunction "OUT1_27") (pintype "bidirectional"))
    )
    (net (code "93") (name "Net-(R10B-1)") (class "Default")
      (node (ref "D15") (pin "C") (pinfunction "C_C") (pintype "passive"))
      (node (ref "D16") (pin "A") (pinfunction "A_A") (pintype "passive"))
      (node (ref "LED9") (pin "A") (pinfunction "A_A") (pintype "passive"))
      (node (ref "R10") (pin "3") (pinfunction "1_3") (pintype "passive"))
      (node (ref "RELAY") (pin "7") (pinfunction "K_7") (pintype "passive"))
      (node (ref "U3") (pin "19") (pinfunction "OUT3_19") (pintype "bidirectional"))
      (node (ref "U3") (pin "20") (pinfunction "OUT3_20") (pintype "bidirectional"))
      (node (ref "U3") (pin "21") (pinfunction "OUT3_21") (pintype "bidirectional"))
    )
    (net (code "94") (name "Net-(R10C-1)") (class "Default")
      (node (ref "D13") (pin "C") (pinfunction "C_C") (pintype "passive"))
      (node (ref "D14") (pin "A") (pinfunction "A_A") (pintype "passive"))
      (node (ref "LED8") (pin "A") (pinfunction "A_A") (pintype "passive"))
      (node (ref "R10") (pin "5") (pinfunction "1_5") (pintype "passive"))
      (node (ref "RELAY") (pin "6") (pinfunction "K_6") (pintype "passive"))
      (node (ref "U3") (pin "22") (pinfunction "OUT2_22") (pintype "bidirectional"))
      (node (ref "U3") (pin "23") (pinfunction "OUT2_23") (pintype "bidirectional"))
      (node (ref "U3") (pin "24") (pinfunction "OUT2_24") (pintype "bidirectional"))
    )
    (net (code "95") (name "Net-(R10D-1)") (class "Default")
      (node (ref "D11") (pin "C") (pinfunction "C_C") (pintype "passive"))
      (node (ref "D12") (pin "A") (pinfunction "A_A") (pintype "passive"))
      (node (ref "LED7") (pin "A") (pinfunction "A_A") (pintype "passive"))
      (node (ref "R10") (pin "7") (pinfunction "1_7") (pintype "passive"))
      (node (ref "RELAY") (pin "5") (pinfunction "K_5") (pintype "passive"))
      (node (ref "U3") (pin "25") (pinfunction "OUT1_25") (pintype "bidirectional"))
      (node (ref "U3") (pin "26") (pinfunction "OUT1_26") (pintype "bidirectional"))
      (node (ref "U3") (pin "27") (pinfunction "OUT1_27") (pintype "bidirectional"))
    )
    (net (code "96") (name "Net-(R11B-2)") (class "Default")
      (node (ref "R11") (pin "4") (pinfunction "2_4") (pintype "passive"))
      (node (ref "R11") (pin "6") (pinfunction "2_6") (pintype "passive"))
      (node (ref "U4") (pin "4") (pinfunction "DG1_4") (pintype "bidirectional"))
    )
    (net (code "97") (name "Net-(R11D-2)") (class "Default")
      (node (ref "R11") (pin "8") (pinfunction "2_8") (pintype "passive"))
      (node (ref "R12") (pin "2") (pinfunction "2_2") (pintype "passive"))
      (node (ref "U4") (pin "5") (pinfunction "DG2_5") (pintype "bidirectional"))
    )
    (net (code "98") (name "Net-(R12B-2)") (class "Default")
      (node (ref "R12") (pin "4") (pinfunction "2_4") (pintype "passive"))
      (node (ref "U4") (pin "6") (pinfunction "IN2_6") (pintype "bidirectional"))
    )
    (net (code "99") (name "Net-(R12C-2)") (class "Default")
      (node (ref "R12") (pin "6") (pinfunction "2_6") (pintype "passive"))
      (node (ref "U4") (pin "9") (pinfunction "IN3_9") (pintype "bidirectional"))
    )
    (net (code "100") (name "Net-(R12D-2)") (class "Default")
      (node (ref "R12") (pin "8") (pinfunction "2_8") (pintype "passive"))
      (node (ref "R13") (pin "2") (pinfunction "2_2") (pintype "passive"))
      (node (ref "U4") (pin "10") (pinfunction "DG3_10") (pintype "bidirectional"))
    )
    (net (code "101") (name "Net-(R13B-2)") (class "Default")
      (node (ref "R13") (pin "4") (pinfunction "2_4") (pintype "passive"))
      (node (ref "R13") (pin "6") (pinfunction "2_6") (pintype "passive"))
      (node (ref "U4") (pin "11") (pinfunction "DG4_11") (pintype "bidirectional"))
    )
    (net (code "102") (name "Net-(R13D-2)") (class "Default")
      (node (ref "R13") (pin "8") (pinfunction "2_8") (pintype "passive"))
      (node (ref "U4") (pin "12") (pinfunction "IN4_12") (pintype "bidirectional"))
    )
    (net (code "103") (name "Net-(R14B-2)") (class "Default")
      (node (ref "R14") (pin "4") (pinfunction "2_4") (pintype "passive"))
      (node (ref "R14") (pin "6") (pinfunction "2_6") (pintype "passive"))
      (node (ref "U5") (pin "4") (pinfunction "DG1_4") (pintype "bidirectional"))
    )
    (net (code "104") (name "Net-(R14D-2)") (class "Default")
      (node (ref "R14") (pin "8") (pinfunction "2_8") (pintype "passive"))
      (node (ref "R15") (pin "2") (pinfunction "2_2") (pintype "passive"))
      (node (ref "U5") (pin "5") (pinfunction "DG2_5") (pintype "bidirectional"))
    )
    (net (code "105") (name "Net-(R15B-2)") (class "Default")
      (node (ref "R15") (pin "4") (pinfunction "2_4") (pintype "passive"))
      (node (ref "U5") (pin "6") (pinfunction "IN2_6") (pintype "bidirectional"))
    )
    (net (code "106") (name "Net-(R15C-2)") (class "Default")
      (node (ref "R15") (pin "6") (pinfunction "2_6") (pintype "passive"))
      (node (ref "U5") (pin "9") (pinfunction "IN3_9") (pintype "bidirectional"))
    )
    (net (code "107") (name "Net-(R15D-2)") (class "Default")
      (node (ref "R15") (pin "8") (pinfunction "2_8") (pintype "passive"))
      (node (ref "R16") (pin "2") (pinfunction "2_2") (pintype "passive"))
      (node (ref "U5") (pin "10") (pinfunction "DG3_10") (pintype "bidirectional"))
    )
    (net (code "108") (name "Net-(R16B-2)") (class "Default")
      (node (ref "R16") (pin "4") (pinfunction "2_4") (pintype "passive"))
      (node (ref "R16") (pin "6") (pinfunction "2_6") (pintype "passive"))
      (node (ref "U5") (pin "11") (pinfunction "DG4_11") (pintype "bidirectional"))
    )
    (net (code "109") (name "Net-(R16D-2)") (class "Default")
      (node (ref "R16") (pin "8") (pinfunction "2_8") (pintype "passive"))
      (node (ref "U5") (pin "12") (pinfunction "IN4_12") (pintype "bidirectional"))
    )
    (net (code "110") (name "Net-(R17B-1)") (class "Default")
      (node (ref "D23") (pin "C") (pinfunction "C_C") (pintype "passive"))
      (node (ref "D24") (pin "A") (pinfunction "A_A") (pintype "passive"))
      (node (ref "R17") (pin "3") (pinfunction "1_3") (pintype "passive"))
      (node (ref "U4") (pin "19") (pinfunction "OUT3_19") (pintype "bidirectional"))
      (node (ref "U4") (pin "20") (pinfunction "OUT3_20") (pintype "bidirectional"))
      (node (ref "U4") (pin "21") (pinfunction "OUT3_21") (pintype "bidirectional"))
      (node (ref "U8") (pin "1") (pinfunction "IP+_1") (pintype "bidirectional"))
      (node (ref "U8") (pin "2") (pinfunction "IP+_2") (pintype "bidirectional"))
    )
    (net (code "111") (name "Net-(R17C-1)") (class "Default")
      (node (ref "D21") (pin "C") (pinfunction "C_C") (pintype "passive"))
      (node (ref "D22") (pin "A") (pinfunction "A_A") (pintype "passive"))
      (node (ref "R17") (pin "5") (pinfunction "1_5") (pintype "passive"))
      (node (ref "U4") (pin "22") (pinfunction "OUT2_22") (pintype "bidirectional"))
      (node (ref "U4") (pin "23") (pinfunction "OUT2_23") (pintype "bidirectional"))
      (node (ref "U4") (pin "24") (pinfunction "OUT2_24") (pintype "bidirectional"))
      (node (ref "U7") (pin "1") (pinfunction "IP+_1") (pintype "bidirectional"))
      (node (ref "U7") (pin "2") (pinfunction "IP+_2") (pintype "bidirectional"))
    )
    (net (code "112") (name "Net-(R17D-1)") (class "Default")
      (node (ref "D19") (pin "C") (pinfunction "C_C") (pintype "passive"))
      (node (ref "D20") (pin "A") (pinfunction "A_A") (pintype "passive"))
      (node (ref "R17") (pin "7") (pinfunction "1_7") (pintype "passive"))
      (node (ref "U4") (pin "25") (pinfunction "OUT1_25") (pintype "bidirectional"))
      (node (ref "U4") (pin "26") (pinfunction "OUT1_26") (pintype "bidirectional"))
      (node (ref "U4") (pin "27") (pinfunction "OUT1_27") (pintype "bidirectional"))
      (node (ref "U6") (pin "1") (pinfunction "IP+_1") (pintype "bidirectional"))
      (node (ref "U6") (pin "2") (pinfunction "IP+_2") (pintype "bidirectional"))
    )
    (net (code "113") (name "Net-(R18B-1)") (class "Default")
      (node (ref "D31") (pin "C") (pinfunction "C_C") (pintype "passive"))
      (node (ref "D32") (pin "A") (pinfunction "A_A") (pintype "passive"))
      (node (ref "R18") (pin "3") (pinfunction "1_3") (pintype "passive"))
      (node (ref "U12") (pin "1") (pinfunction "IP+_1") (pintype "bidirectional"))
      (node (ref "U12") (pin "2") (pinfunction "IP+_2") (pintype "bidirectional"))
      (node (ref "U5") (pin "19") (pinfunction "OUT3_19") (pintype "bidirectional"))
      (node (ref "U5") (pin "20") (pinfunction "OUT3_20") (pintype "bidirectional"))
      (node (ref "U5") (pin "21") (pinfunction "OUT3_21") (pintype "bidirectional"))
    )
    (net (code "114") (name "Net-(R18C-1)") (class "Default")
      (node (ref "D29") (pin "C") (pinfunction "C_C") (pintype "passive"))
      (node (ref "D30") (pin "A") (pinfunction "A_A") (pintype "passive"))
      (node (ref "R18") (pin "5") (pinfunction "1_5") (pintype "passive"))
      (node (ref "U11") (pin "1") (pinfunction "IP+_1") (pintype "bidirectional"))
      (node (ref "U11") (pin "2") (pinfunction "IP+_2") (pintype "bidirectional"))
      (node (ref "U5") (pin "22") (pinfunction "OUT2_22") (pintype "bidirectional"))
      (node (ref "U5") (pin "23") (pinfunction "OUT2_23") (pintype "bidirectional"))
      (node (ref "U5") (pin "24") (pinfunction "OUT2_24") (pintype "bidirectional"))
    )
    (net (code "115") (name "Net-(R18D-1)") (class "Default")
      (node (ref "D27") (pin "C") (pinfunction "C_C") (pintype "passive"))
      (node (ref "D28") (pin "A") (pinfunction "A_A") (pintype "passive"))
      (node (ref "R18") (pin "7") (pinfunction "1_7") (pintype "passive"))
      (node (ref "U10") (pin "1") (pinfunction "IP+_1") (pintype "bidirectional"))
      (node (ref "U10") (pin "2") (pinfunction "IP+_2") (pintype "bidirectional"))
      (node (ref "U5") (pin "25") (pinfunction "OUT1_25") (pintype "bidirectional"))
      (node (ref "U5") (pin "26") (pinfunction "OUT1_26") (pintype "bidirectional"))
      (node (ref "U5") (pin "27") (pinfunction "OUT1_27") (pintype "bidirectional"))
    )
    (net (code "116") (name "Net-(RELAYD-K)") (class "Default")
      (node (ref "D10") (pin "A") (pinfunction "A_A") (pintype "passive"))
      (node (ref "D9") (pin "C") (pinfunction "C_C") (pintype "passive"))
      (node (ref "LED6") (pin "A") (pinfunction "A_A") (pintype "passive"))
      (node (ref "R9") (pin "1") (pinfunction "1_1") (pintype "passive"))
      (node (ref "RELAY") (pin "4") (pinfunction "K_4") (pintype "passive"))
      (node (ref "U1") (pin "16") (pinfunction "OUT4_16") (pintype "bidirectional"))
      (node (ref "U1") (pin "17") (pinfunction "OUT4_17") (pintype "bidirectional"))
      (node (ref "U1") (pin "18") (pinfunction "OUT4_18") (pintype "bidirectional"))
    )
    (net (code "117") (name "Net-(RELAYH-K)") (class "Default")
      (node (ref "D17") (pin "C") (pinfunction "C_C") (pintype "passive"))
      (node (ref "D18") (pin "A") (pinfunction "A_A") (pintype "passive"))
      (node (ref "LED10") (pin "A") (pinfunction "A_A") (pintype "passive"))
      (node (ref "R10") (pin "1") (pinfunction "1_1") (pintype "passive"))
      (node (ref "RELAY") (pin "8") (pinfunction "K_8") (pintype "passive"))
      (node (ref "U3") (pin "16") (pinfunction "OUT4_16") (pintype "bidirectional"))
      (node (ref "U3") (pin "17") (pinfunction "OUT4_17") (pintype "bidirectional"))
      (node (ref "U3") (pin "18") (pinfunction "OUT4_18") (pintype "bidirectional"))
    )
    (net (code "118") (name "Net-(U$1-AIN0)") (class "Default")
      (node (ref "U$1") (pin "85") (pinfunction "AIN0_85") (pintype "power_in"))
      (node (ref "U$5") (pin "6") (pinfunction "6_6") (pintype "passive"))
    )
    (net (code "119") (name "Net-(U$1-AIN1)") (class "Default")
      (node (ref "U$1") (pin "86") (pinfunction "AIN1_86") (pintype "passive"))
      (node (ref "U$2") (pin "6") (pinfunction "6_6") (pintype "passive"))
    )
    (net (code "120") (name "Net-(U$1-AIN2)") (class "Default")
      (node (ref "U$1") (pin "83") (pinfunction "AIN2_83") (pintype "passive"))
      (node (ref "U$5") (pin "7") (pinfunction "7_7") (pintype "passive"))
    )
    (net (code "121") (name "Net-(U$1-AIN3)") (class "Default")
      (node (ref "U$1") (pin "84") (pinfunction "AIN3_84") (pintype "passive"))
      (node (ref "U$2") (pin "7") (pinfunction "7_7") (pintype "passive"))
    )
    (net (code "122") (name "Net-(U$1-AIN4)") (class "Default")
      (node (ref "U$1") (pin "79") (pinfunction "AIN4_79") (pintype "passive"))
      (node (ref "U$5") (pin "9") (pinfunction "9_9") (pintype "passive"))
    )
    (net (code "123") (name "Net-(U$1-AIN5)") (class "Default")
      (node (ref "U$1") (pin "82") (pinfunction "AIN5_82") (pintype "passive"))
      (node (ref "U$2") (pin "8") (pinfunction "8_8") (pintype "passive"))
    )
    (net (code "124") (name "Net-(U$1-AIN6)") (class "Default")
      (node (ref "U$1") (pin "81") (pinfunction "AIN6_81") (pintype "passive"))
      (node (ref "U$5") (pin "8") (pinfunction "8_8") (pintype "passive"))
    )
    (net (code "125") (name "Net-(U$1-CLKOUT2)") (class "Default")
      (node (ref "U$1") (pin "87") (pinfunction "CLKOUT2_87") (pintype "input"))
      (node (ref "U$5") (pin "5") (pinfunction "5_5") (pintype "passive"))
    )
    (net (code "126") (name "Net-(U$1-EHRPWM1A)") (class "Default")
      (node (ref "U$1") (pin "60") (pinfunction "EHRPWM1A_60") (pintype "passive"))
      (node (ref "U$2") (pin "19") (pinfunction "19_19") (pintype "passive"))
    )
    (net (code "127") (name "Net-(U$1-EHRPWM1B)") (class "Default")
      (node (ref "U$1") (pin "62") (pinfunction "EHRPWM1B_62") (pintype "passive"))
      (node (ref "U$2") (pin "18") (pinfunction "18_18") (pintype "passive"))
    )
    (net (code "128") (name "Net-(U$1-EHRPWM2A)") (class "Default")
      (node (ref "U$1") (pin "19") (pinfunction "EHRPWM2A_19") (pintype "passive"))
      (node (ref "U$4") (pin "15") (pinfunction "15_15") (pintype "passive"))
    )
    (net (code "129") (name "Net-(U$1-EHRPWM2B)") (class "Default")
      (node (ref "U$1") (pin "13") (pinfunction "EHRPWM2B_13") (pintype "passive"))
      (node (ref "U$4") (pin "18") (pinfunction "18_18") (pintype "passive"))
    )
    (net (code "130") (name "Net-(U$1-GPIO0_7)") (class "Default")
      (node (ref "U$1") (pin "88") (pinfunction "GPIO0_7_88") (pintype "passive"))
      (node (ref "U$2") (pin "5") (pinfunction "5_5") (pintype "passive"))
    )
    (net (code "131") (name "Net-(U$1-GPIO0_26)") (class "Default")
      (node (ref "U$1") (pin "14") (pinfunction "GPIO0_26_14") (pintype "passive"))
      (node (ref "U$3") (pin "18") (pinfunction "18_18") (pintype "passive"))
    )
    (net (code "132") (name "Net-(U$1-GPIO0_27)") (class "Default")
      (node (ref "U$1") (pin "17") (pinfunction "GPIO0_27_17") (pintype "passive"))
      (node (ref "U$4") (pin "16") (pinfunction "16_16") (pintype "passive"))
    )
    (net (code "133") (name "Net-(U$1-GPIO1_0)") (class "Default")
      (node (ref "U$1") (pin "25") (pinfunction "GPIO1_0_25") (pintype "passive"))
      (node (ref "U$4") (pin "12") (pinfunction "12_12") (pintype "passive"))
    )
    (net (code "134") (name "Net-(U$1-GPIO1_1)") (class "Default")
      (node (ref "U$1") (pin "24") (pinfunction "GPIO1_1_24") (pintype "passive"))
      (node (ref "U$3") (pin "13") (pinfunction "13_13") (pintype "passive"))
    )
    (net (code "135") (name "Net-(U$1-GPIO1_2)") (class "Default")
      (node (ref "U$1") (pin "5") (pinfunction "GPIO1_2_5") (pintype "passive"))
      (node (ref "U$4") (pin "22") (pinfunction "22_22") (pintype "passive"))
    )
    (net (code "136") (name "Net-(U$1-GPIO1_3)") (class "Default")
      (node (ref "U$1") (pin "6") (pinfunction "GPIO1_3_6") (pintype "passive"))
      (node (ref "U$3") (pin "22") (pinfunction "22_22") (pintype "passive"))
    )
    (net (code "137") (name "Net-(U$1-GPIO1_4)") (class "Default")
      (node (ref "U$1") (pin "23") (pinfunction "GPIO1_4_23") (pintype "passive"))
      (node (ref "U$4") (pin "13") (pinfunction "13_13") (pintype "passive"))
    )
    (net (code "138") (name "Net-(U$1-GPIO1_5)") (class "Default")
      (node (ref "U$1") (pin "22") (pinfunction "GPIO1_5_22") (pintype "passive"))
      (node (ref "U$3") (pin "14") (pinfunction "14_14") (pintype "passive"))
    )
    (net (code "139") (name "Net-(U$1-GPIO1_6)") (class "Default")
      (node (ref "U$1") (pin "3") (pinfunction "GPIO1_6_3") (pintype "passive"))
      (node (ref "U$4") (pin "23") (pinfunction "23_23") (pintype "passive"))
    )
    (net (code "140") (name "Net-(U$1-GPIO1_7)") (class "Default")
      (node (ref "U$1") (pin "4") (pinfunction "GPIO1_7_4") (pintype "passive"))
      (node (ref "U$3") (pin "23") (pinfunction "23_23") (pintype "passive"))
    )
    (net (code "141") (name "Net-(U$1-GPIO1_12)") (class "Default")
      (node (ref "U$1") (pin "12") (pinfunction "GPIO1_12_12") (pintype "passive"))
      (node (ref "U$3") (pin "19") (pinfunction "19_19") (pintype "passive"))
    )
    (net (code "142") (name "Net-(U$1-GPIO1_13)") (class "Default")
      (node (ref "U$1") (pin "11") (pinfunction "GPIO1_13_11") (pintype "passive"))
      (node (ref "U$4") (pin "19") (pinfunction "19_19") (pintype "passive"))
    )
    (net (code "143") (name "Net-(U$1-GPIO1_14)") (class "Default")
      (node (ref "U$1") (pin "16") (pinfunction "GPIO1_14_16") (pintype "passive"))
      (node (ref "U$3") (pin "17") (pinfunction "17_17") (pintype "passive"))
    )
    (net (code "144") (name "Net-(U$1-GPIO1_15)") (class "Default")
      (node (ref "U$1") (pin "15") (pinfunction "GPIO1_15_15") (pintype "passive"))
      (node (ref "U$4") (pin "17") (pinfunction "17_17") (pintype "passive"))
    )
    (net (code "145") (name "Net-(U$1-GPIO1_16)") (class "Default")
      (node (ref "U$1") (pin "61") (pinfunction "GPIO1_16_61") (pintype "passive"))
      (node (ref "U$5") (pin "18") (pinfunction "18_18") (pintype "passive"))
    )
    (net (code "146") (name "Net-(U$1-GPIO1_17)") (class "Default")
      (node (ref "U$1") (pin "69") (pinfunction "GPIO1_17_69") (pintype "passive"))
      (node (ref "U$5") (pin "14") (pinfunction "14_14") (pintype "passive"))
    )
    (net (code "147") (name "Net-(U$1-GPIO1_28)") (class "Default")
      (node (ref "U$1") (pin "58") (pinfunction "GPIO1_28_58") (pintype "passive"))
      (node (ref "U$2") (pin "20") (pinfunction "20_20") (pintype "passive"))
    )
    (net (code "148") (name "Net-(U$1-GPIO1_29)") (class "Default")
      (node (ref "U$1") (pin "26") (pinfunction "GPIO1_29_26") (pintype "passive"))
      (node (ref "U$3") (pin "12") (pinfunction "12_12") (pintype "passive"))
    )
    (net (code "149") (name "Net-(U$1-GPIO1_30)") (class "Default")
      (node (ref "U$1") (pin "21") (pinfunction "GPIO1_30_21") (pintype "passive"))
      (node (ref "U$4") (pin "14") (pinfunction "14_14") (pintype "passive"))
    )
    (net (code "150") (name "Net-(U$1-GPIO1_31)") (class "Default")
      (node (ref "U$1") (pin "20") (pinfunction "GPIO1_31_20") (pintype "passive"))
      (node (ref "U$3") (pin "15") (pinfunction "15_15") (pintype "passive"))
    )
    (net (code "151") (name "Net-(U$1-GPIO2_1)") (class "Default")
      (node (ref "U$1") (pin "18") (pinfunction "GPIO2_1_18") (pintype "passive"))
      (node (ref "U$3") (pin "16") (pinfunction "16_16") (pintype "passive"))
    )
    (net (code "152") (name "Net-(U$1-GPIO2_6)") (class "Default")
      (node (ref "U$1") (pin "45") (pinfunction "GPIO2_6_45") (pintype "passive"))
      (node (ref "U$4") (pin "2") (pinfunction "2_2") (pintype "passive"))
    )
    (net (code "153") (name "Net-(U$1-GPIO2_7)") (class "Default")
      (node (ref "U$1") (pin "46") (pinfunction "GPIO2_7_46") (pintype "passive"))
      (node (ref "U$3") (pin "2") (pinfunction "2_2") (pintype "passive"))
    )
    (net (code "154") (name "Net-(U$1-GPIO2_8)") (class "Default")
      (node (ref "U$1") (pin "43") (pinfunction "GPIO2_8_43") (pintype "passive"))
      (node (ref "U$4") (pin "3") (pinfunction "3_3") (pintype "passive"))
    )
    (net (code "155") (name "Net-(U$1-GPIO2_9)") (class "Default")
      (node (ref "U$1") (pin "44") (pinfunction "GPIO2_9_44") (pintype "passive"))
      (node (ref "U$3") (pin "3") (pinfunction "3_3") (pintype "passive"))
    )
    (net (code "156") (name "Net-(U$1-GPIO2_10)") (class "Default")
      (node (ref "U$1") (pin "41") (pinfunction "GPIO2_10_41") (pintype "passive"))
      (node (ref "U$4") (pin "4") (pinfunction "4_4") (pintype "passive"))
    )
    (net (code "157") (name "Net-(U$1-GPIO2_11)") (class "Default")
      (node (ref "U$1") (pin "42") (pinfunction "GPIO2_11_42") (pintype "passive"))
      (node (ref "U$3") (pin "4") (pinfunction "4_4") (pintype "passive"))
    )
    (net (code "158") (name "Net-(U$1-GPIO2_12)") (class "Default")
      (node (ref "U$1") (pin "39") (pinfunction "GPIO2_12_39") (pintype "passive"))
      (node (ref "U$4") (pin "5") (pinfunction "5_5") (pintype "passive"))
    )
    (net (code "159") (name "Net-(U$1-GPIO2_13)") (class "Default")
      (node (ref "U$1") (pin "40") (pinfunction "GPIO2_13_40") (pintype "passive"))
      (node (ref "U$3") (pin "5") (pinfunction "5_5") (pintype "passive"))
    )
    (net (code "160") (name "Net-(U$1-GPIO2_22)") (class "Default")
      (node (ref "U$1") (pin "27") (pinfunction "GPIO2_22_27") (pintype "passive"))
      (node (ref "U$4") (pin "11") (pinfunction "11_11") (pintype "passive"))
    )
    (net (code "161") (name "Net-(U$1-GPIO2_23)") (class "Default")
      (node (ref "U$1") (pin "29") (pinfunction "GPIO2_23_29") (pintype "passive"))
      (node (ref "U$4") (pin "10") (pinfunction "10_10") (pintype "passive"))
    )
    (net (code "162") (name "Net-(U$1-GPIO2_24)") (class "Default")
      (node (ref "U$1") (pin "28") (pinfunction "GPIO2_24_28") (pintype "passive"))
      (node (ref "U$3") (pin "11") (pinfunction "11_11") (pintype "passive"))
    )
    (net (code "163") (name "Net-(U$1-GPIO2_25)") (class "Default")
      (node (ref "U$1") (pin "30") (pinfunction "GPIO2_25_30") (pintype "passive"))
      (node (ref "U$3") (pin "10") (pinfunction "10_10") (pintype "passive"))
    )
    (net (code "164") (name "Net-(U$1-GPIO3_19)") (class "Default")
      (node (ref "U$1") (pin "73") (pinfunction "GPIO3_19_73") (pintype "passive"))
      (node (ref "U$5") (pin "12") (pinfunction "12_12") (pintype "passive"))
    )
    (net (code "165") (name "Net-(U$1-GPIO3_21)") (class "Default")
      (node (ref "U$1") (pin "71") (pinfunction "GPIO3_21_71") (pintype "passive"))
      (node (ref "U$5") (pin "13") (pinfunction "13_13") (pintype "passive"))
    )
    (net (code "166") (name "Net-(U$1-I2C1_SCL)") (class "Default")
      (node (ref "U$1") (pin "63") (pinfunction "I2C1_SCL_63") (pintype "passive"))
      (node (ref "U$5") (pin "17") (pinfunction "17_17") (pintype "passive"))
    )
    (net (code "167") (name "Net-(U$1-I2C1_SDA)") (class "Default")
      (node (ref "U$1") (pin "64") (pinfunction "I2C1_SDA_64") (pintype "passive"))
      (node (ref "U$2") (pin "17") (pinfunction "17_17") (pintype "passive"))
    )
    (net (code "168") (name "Net-(U$1-I2C2_SCL)") (class "Default")
      (node (ref "U$1") (pin "65") (pinfunction "I2C2_SCL_65") (pintype "passive"))
      (node (ref "U$5") (pin "16") (pinfunction "16_16") (pintype "passive"))
    )
    (net (code "169") (name "Net-(U$1-I2C2_SDA)") (class "Default")
      (node (ref "U$1") (pin "66") (pinfunction "I2C2_SDA_66") (pintype "passive"))
      (node (ref "U$2") (pin "16") (pinfunction "16_16") (pintype "passive"))
    )
    (net (code "170") (name "Net-(U$1-PWR_BUT)") (class "Default")
      (node (ref "U$1") (pin "55") (pinfunction "PWR_BUT_55") (pintype "passive"))
      (node (ref "U$5") (pin "21") (pinfunction "21_21") (pintype "passive"))
    )
    (net (code "171") (name "Net-(U$1-SPI1_CS0)") (class "Default")
      (node (ref "U$1") (pin "74") (pinfunction "SPI1_CS0_74") (pintype "passive"))
      (node (ref "U$2") (pin "12") (pinfunction "12_12") (pintype "passive"))
    )
    (net (code "172") (name "Net-(U$1-SPI1_DI)") (class "Default")
      (node (ref "U$1") (pin "76") (pinfunction "SPI1_DI_76") (pintype "passive"))
      (node (ref "U$2") (pin "11") (pinfunction "11_11") (pintype "passive"))
    )
    (net (code "173") (name "Net-(U$1-SPI1_DO)") (class "Default")
      (node (ref "U$1") (pin "75") (pinfunction "SPI1_DO_75") (pintype "passive"))
      (node (ref "U$5") (pin "11") (pinfunction "11_11") (pintype "passive"))
    )
    (net (code "174") (name "Net-(U$1-SPI1_SCLK)") (class "Default")
      (node (ref "U$1") (pin "77") (pinfunction "SPI1_SCLK_77") (pintype "passive"))
      (node (ref "U$5") (pin "10") (pinfunction "10_10") (pintype "passive"))
    )
    (net (code "175") (name "Net-(U$1-SYS_5V-Pad54)") (class "Default")
      (node (ref "U$1") (pin "54") (pinfunction "SYS_5V_54") (pintype "passive"))
      (node (ref "U$2") (pin "22") (pinfunction "22_22") (pintype "passive"))
    )
    (net (code "176") (name "Net-(U$1-SYS_RESETN)") (class "Default")
      (node (ref "U$1") (pin "56") (pinfunction "SYS_RESETN_56") (pintype "passive"))
      (node (ref "U$2") (pin "21") (pinfunction "21_21") (pintype "passive"))
    )
    (net (code "177") (name "Net-(U$1-TIMER4)") (class "Default")
      (node (ref "U$1") (pin "7") (pinfunction "TIMER4_7") (pintype "passive"))
      (node (ref "U$4") (pin "21") (pinfunction "21_21") (pintype "passive"))
    )
    (net (code "178") (name "Net-(U$1-TIMER5)") (class "Default")
      (node (ref "U$1") (pin "9") (pinfunction "TIMER5_9") (pintype "passive"))
      (node (ref "U$4") (pin "20") (pinfunction "20_20") (pintype "passive"))
    )
    (net (code "179") (name "Net-(U$1-TIMER6)") (class "Default")
      (node (ref "U$1") (pin "10") (pinfunction "TIMER6_10") (pintype "passive"))
      (node (ref "U$3") (pin "20") (pinfunction "20_20") (pintype "passive"))
    )
    (net (code "180") (name "Net-(U$1-TIMER7)") (class "Default")
      (node (ref "U$1") (pin "8") (pinfunction "TIMER7_8") (pintype "passive"))
      (node (ref "U$3") (pin "21") (pinfunction "21_21") (pintype "passive"))
    )
    (net (code "181") (name "Net-(U$1-UART3_CTSN)") (class "Default")
      (node (ref "U$1") (pin "36") (pinfunction "UART3_CTSN_36") (pintype "passive"))
      (node (ref "U$3") (pin "7") (pinfunction "7_7") (pintype "passive"))
    )
    (net (code "182") (name "Net-(U$1-UART3_RTSN)") (class "Default")
      (node (ref "U$1") (pin "34") (pinfunction "UART3_RTSN_34") (pintype "passive"))
      (node (ref "U$3") (pin "8") (pinfunction "8_8") (pintype "passive"))
    )
    (net (code "183") (name "Net-(U$1-UART4_CTSN)") (class "Default")
      (node (ref "U$1") (pin "35") (pinfunction "UART4_CTSN_35") (pintype "passive"))
      (node (ref "U$4") (pin "7") (pinfunction "7_7") (pintype "passive"))
    )
    (net (code "184") (name "Net-(U$1-UART4_RTSN)") (class "Default")
      (node (ref "U$1") (pin "33") (pinfunction "UART4_RTSN_33") (pintype "passive"))
      (node (ref "U$4") (pin "8") (pinfunction "8_8") (pintype "passive"))
    )
    (net (code "185") (name "Net-(U$1-UART5_CTSN)") (class "Default")
      (node (ref "U$1") (pin "31") (pinfunction "UART5_CTSN_31") (pintype "passive"))
      (node (ref "U$4") (pin "9") (pinfunction "9_9") (pintype "passive"))
    )
    (net (code "186") (name "Net-(U$1-UART5_RTSN)") (class "Default")
      (node (ref "U$1") (pin "32") (pinfunction "UART5_RTSN_32") (pintype "passive"))
      (node (ref "U$3") (pin "9") (pinfunction "9_9") (pintype "passive"))
    )
    (net (code "187") (name "Net-(U$1-UART5_RXD)") (class "Default")
      (node (ref "U$1") (pin "38") (pinfunction "UART5_RXD_38") (pintype "passive"))
      (node (ref "U$3") (pin "6") (pinfunction "6_6") (pintype "passive"))
    )
    (net (code "188") (name "Net-(U$1-UART5_TXD)") (class "Default")
      (node (ref "U$1") (pin "37") (pinfunction "UART5_TXD_37") (pintype "passive"))
      (node (ref "U$4") (pin "6") (pinfunction "6_6") (pintype "passive"))
    )
    (net (code "189") (name "Net-(U$1-VDD_3V3EXP-Pad49)") (class "Default")
      (node (ref "U$1") (pin "49") (pinfunction "VDD_3V3EXP_49") (pintype "power_in"))
      (node (ref "U$5") (pin "24") (pinfunction "24_24") (pintype "passive"))
    )
    (net (code "190") (name "Net-(U$1-VDD_3V3EXP-Pad50)") (class "Default")
      (node (ref "U$1") (pin "50") (pinfunction "VDD_3V3EXP_50") (pintype "power_in"))
      (node (ref "U$2") (pin "24") (pinfunction "24_24") (pintype "passive"))
    )
    (net (code "191") (name "Net-(U$1-VDD_ADC)") (class "Default")
      (node (ref "U$1") (pin "78") (pinfunction "VDD_ADC_78") (pintype "passive"))
      (node (ref "U$2") (pin "10") (pinfunction "10_10") (pintype "passive"))
    )
    (net (code "192") (name "Net-(U1-IN1)") (class "Default")
      (node (ref "R4") (pin "2") (pinfunction "2_2") (pintype "passive"))
      (node (ref "U1") (pin "3") (pinfunction "IN1_3") (pintype "bidirectional"))
    )
    (net (code "193") (name "Net-(U2-1(TX0))") (class "Default")
      (node (ref "JP10") (pin "7") (pinfunction "7_7") (pintype "passive"))
      (node (ref "R2") (pin "2") (pinfunction "2_2") (pintype "passive"))
      (node (ref "U2") (pin "1") (pinfunction "1(TX0)_1") (pintype "bidirectional"))
    )
    (net (code "194") (name "Net-(U2-14(TX3))") (class "Default")
      (node (ref "JP13") (pin "8") (pinfunction "8_8") (pintype "passive"))
      (node (ref "U2") (pin "14") (pinfunction "14(TX3)_14") (pintype "bidirectional"))
    )
    (net (code "195") (name "Net-(U2-15(RX3))") (class "Default")
      (node (ref "JP13") (pin "7") (pinfunction "7_7") (pintype "passive"))
      (node (ref "U2") (pin "15") (pinfunction "15(RX3)_15") (pintype "bidirectional"))
    )
    (net (code "196") (name "Net-(U2-16(TX2))") (class "Default")
      (node (ref "JP13") (pin "6") (pinfunction "6_6") (pintype "passive"))
      (node (ref "U2") (pin "16") (pinfunction "16(TX2)_16") (pintype "bidirectional"))
    )
    (net (code "197") (name "Net-(U2-17(RX2))") (class "Default")
      (node (ref "JP13") (pin "5") (pinfunction "5_5") (pintype "passive"))
      (node (ref "U2") (pin "17") (pinfunction "17(RX2)_17") (pintype "bidirectional"))
    )
    (net (code "198") (name "Net-(U2-18(TX1))") (class "Default")
      (node (ref "JP13") (pin "4") (pinfunction "4_4") (pintype "passive"))
      (node (ref "R1") (pin "1") (pinfunction "1_1") (pintype "passive"))
      (node (ref "U2") (pin "18") (pinfunction "18(TX1)_18") (pintype "bidirectional"))
    )
    (net (code "199") (name "Net-(U3-IN1)") (class "Default")
      (node (ref "R6") (pin "2") (pinfunction "2_2") (pintype "passive"))
      (node (ref "U3") (pin "3") (pinfunction "IN1_3") (pintype "bidirectional"))
    )
    (net (code "200") (name "Net-(U4-IN1)") (class "Default")
      (node (ref "R11") (pin "2") (pinfunction "2_2") (pintype "passive"))
      (node (ref "U4") (pin "3") (pinfunction "IN1_3") (pintype "bidirectional"))
    )
    (net (code "201") (name "Net-(U5-IN1)") (class "Default")
      (node (ref "R14") (pin "2") (pinfunction "2_2") (pintype "passive"))
      (node (ref "U5") (pin "3") (pinfunction "IN1_3") (pintype "bidirectional"))
    )
    (net (code "202") (name "Net-(U6-FILT)") (class "Default")
      (node (ref "C1") (pin "2") (pinfunction "2_2") (pintype "passive"))
      (node (ref "U6") (pin "6") (pinfunction "FILT_6") (pintype "bidirectional"))
    )
    (net (code "203") (name "Net-(U7-FILT)") (class "Default")
      (node (ref "C2") (pin "2") (pinfunction "2_2") (pintype "passive"))
      (node (ref "U7") (pin "6") (pinfunction "FILT_6") (pintype "bidirectional"))
    )
    (net (code "204") (name "Net-(U8-FILT)") (class "Default")
      (node (ref "C3") (pin "2") (pinfunction "2_2") (pintype "passive"))
      (node (ref "U8") (pin "6") (pinfunction "FILT_6") (pintype "bidirectional"))
    )
    (net (code "205") (name "Net-(U9-FILT)") (class "Default")
      (node (ref "C4") (pin "2") (pinfunction "2_2") (pintype "passive"))
      (node (ref "U9") (pin "6") (pinfunction "FILT_6") (pintype "bidirectional"))
    )
    (net (code "206") (name "Net-(U10-FILT)") (class "Default")
      (node (ref "C9") (pin "2") (pinfunction "2_2") (pintype "passive"))
      (node (ref "U10") (pin "6") (pinfunction "FILT_6") (pintype "bidirectional"))
    )
    (net (code "207") (name "Net-(U11-FILT)") (class "Default")
      (node (ref "C10") (pin "2") (pinfunction "2_2") (pintype "passive"))
      (node (ref "U11") (pin "6") (pinfunction "FILT_6") (pintype "bidirectional"))
    )
    (net (code "208") (name "Net-(U12-FILT)") (class "Default")
      (node (ref "C11") (pin "2") (pinfunction "2_2") (pintype "passive"))
      (node (ref "U12") (pin "6") (pinfunction "FILT_6") (pintype "bidirectional"))
    )
    (net (code "209") (name "Net-(U13-FILT)") (class "Default")
      (node (ref "C12") (pin "2") (pinfunction "2_2") (pintype "passive"))
      (node (ref "U13") (pin "6") (pinfunction "FILT_6") (pintype "bidirectional"))
    )
    (net (code "210") (name "Net-(U14-BOOT)") (class "Default")
      (node (ref "C21") (pin "2") (pinfunction "2_2") (pintype "passive"))
      (node (ref "U14") (pin "1") (pinfunction "BOOT_1") (pintype "bidirectional"))
    )
    (net (code "211") (name "Net-(U14-COMP)") (class "Default")
      (node (ref "C22") (pin "1") (pinfunction "1_1") (pintype "passive"))
      (node (ref "C23") (pin "1") (pinfunction "1_1") (pintype "passive"))
      (node (ref "U14") (pin "6") (pinfunction "COMP_6") (pintype "bidirectional"))
    )
    (net (code "212") (name "Net-(U14-PH)") (class "Default")
      (node (ref "C21") (pin "1") (pinfunction "1_1") (pintype "passive"))
      (node (ref "D35") (pin "C") (pinfunction "C_C") (pintype "passive"))
      (node (ref "L1") (pin "1") (pinfunction "1_1") (pintype "passive"))
      (node (ref "U14") (pin "8") (pinfunction "PH_8") (pintype "bidirectional"))
    )
    (net (code "213") (name "Net-(U14-SS)") (class "Default")
      (node (ref "C20") (pin "1") (pinfunction "1_1") (pintype "passive"))
      (node (ref "U14") (pin "4") (pinfunction "SS_4") (pintype "bidirectional"))
    )
    (net (code "214") (name "Net-(U14-VSENSE)") (class "Default")
      (node (ref "R22") (pin "1") (pinfunction "1_1") (pintype "passive"))
      (node (ref "R23") (pin "2") (pinfunction "2_2") (pintype "passive"))
      (node (ref "U14") (pin "5") (pinfunction "VSENSE_5") (pintype "bidirectional"))
    )
    (net (code "215") (name "Net-(U15-BOOT)") (class "Default")
      (node (ref "C32") (pin "2") (pinfunction "2_2") (pintype "passive"))
      (node (ref "U15") (pin "1") (pinfunction "BOOT_1") (pintype "bidirectional"))
    )
    (net (code "216") (name "Net-(U15-COMP)") (class "Default")
      (node (ref "C33") (pin "1") (pinfunction "1_1") (pintype "passive"))
      (node (ref "C34") (pin "1") (pinfunction "1_1") (pintype "passive"))
      (node (ref "U15") (pin "6") (pinfunction "COMP_6") (pintype "bidirectional"))
    )
    (net (code "217") (name "Net-(U15-PH)") (class "Default")
      (node (ref "C32") (pin "1") (pinfunction "1_1") (pintype "passive"))
      (node (ref "D36") (pin "C") (pinfunction "C_C") (pintype "passive"))
      (node (ref "L2") (pin "1") (pinfunction "1_1") (pintype "passive"))
      (node (ref "U15") (pin "8") (pinfunction "PH_8") (pintype "bidirectional"))
    )
    (net (code "218") (name "Net-(U15-SS)") (class "Default")
      (node (ref "C31") (pin "1") (pinfunction "1_1") (pintype "passive"))
      (node (ref "U15") (pin "4") (pinfunction "SS_4") (pintype "bidirectional"))
    )
    (net (code "219") (name "Net-(U15-VSENSE)") (class "Default")
      (node (ref "R27") (pin "1") (pinfunction "1_1") (pintype "passive"))
      (node (ref "R28") (pin "2") (pinfunction "2_2") (pintype "passive"))
      (node (ref "U15") (pin "5") (pinfunction "VSENSE_5") (pintype "bidirectional"))
    )
    (net (code "220") (name "RELAY1") (class "Default")
      (node (ref "JP15") (pin "1") (pinfunction "1_1") (pintype "passive"))
      (node (ref "R4") (pin "1") (pinfunction "1_1") (pintype "passive"))
      (node (ref "U2") (pin "52") (pinfunction "52_52") (pintype "bidirectional"))
    )
    (net (code "221") (name "RELAY1FB") (class "Default")
      (node (ref "JP16") (pin "1") (pinfunction "1_1") (pintype "passive"))
      (node (ref "R4") (pin "3") (pinfunction "1_3") (pintype "passive"))
      (node (ref "U2") (pin "53") (pinfunction "53_53") (pintype "bidirectional"))
    )
    (net (code "222") (name "RELAY2") (class "Default")
      (node (ref "JP16") (pin "2") (pinfunction "2_2") (pintype "passive"))
      (node (ref "R5") (pin "3") (pinfunction "1_3") (pintype "passive"))
      (node (ref "U2") (pin "51") (pinfunction "51_51") (pintype "bidirectional"))
    )
    (net (code "223") (name "RELAY2FB") (class "Default")
      (node (ref "JP15") (pin "2") (pinfunction "2_2") (pintype "passive"))
      (node (ref "R5") (pin "1") (pinfunction "1_1") (pintype "passive"))
      (node (ref "U2") (pin "50") (pinfunction "50_50") (pintype "bidirectional"))
    )
    (net (code "224") (name "RELAY3") (class "Default")
      (node (ref "JP15") (pin "3") (pinfunction "3_3") (pintype "passive"))
      (node (ref "R5") (pin "5") (pinfunction "1_5") (pintype "passive"))
      (node (ref "U2") (pin "48") (pinfunction "48_48") (pintype "bidirectional"))
    )
    (net (code "225") (name "RELAY3FB") (class "Default")
      (node (ref "JP16") (pin "3") (pinfunction "3_3") (pintype "passive"))
      (node (ref "R5") (pin "7") (pinfunction "1_7") (pintype "passive"))
      (node (ref "U2") (pin "49") (pinfunction "49_49") (pintype "bidirectional"))
    )
    (net (code "226") (name "RELAY4") (class "Default")
      (node (ref "JP16") (pin "4") (pinfunction "4_4") (pintype "passive"))
      (node (ref "R3") (pin "7") (pinfunction "1_7") (pintype "passive"))
      (node (ref "U2") (pin "47") (pinfunction "47_47") (pintype "bidirectional"))
    )
    (net (code "227") (name "RELAY4FB") (class "Default")
      (node (ref "JP15") (pin "4") (pinfunction "4_4") (pintype "passive"))
      (node (ref "R3") (pin "5") (pinfunction "1_5") (pintype "passive"))
      (node (ref "U2") (pin "46") (pinfunction "46_46") (pintype "bidirectional"))
    )
    (net (code "228") (name "RELAY5") (class "Default")
      (node (ref "JP15") (pin "5") (pinfunction "5_5") (pintype "passive"))
      (node (ref "R6") (pin "1") (pinfunction "1_1") (pintype "passive"))
      (node (ref "U2") (pin "44") (pinfunction "44_44") (pintype "bidirectional"))
    )
    (net (code "229") (name "RELAY5FB") (class "Default")
      (node (ref "JP16") (pin "5") (pinfunction "5_5") (pintype "passive"))
      (node (ref "R6") (pin "3") (pinfunction "1_3") (pintype "passive"))
      (node (ref "U2") (pin "45") (pinfunction "45_45") (pintype "bidirectional"))
    )
    (net (code "230") (name "RELAY6") (class "Default")
      (node (ref "JP16") (pin "6") (pinfunction "6_6") (pintype "passive"))
      (node (ref "R7") (pin "3") (pinfunction "1_3") (pintype "passive"))
      (node (ref "U2") (pin "43") (pinfunction "43_43") (pintype "bidirectional"))
    )
    (net (code "231") (name "RELAY6FB") (class "Default")
      (node (ref "JP15") (pin "6") (pinfunction "6_6") (pintype "passive"))
      (node (ref "R6") (pin "7") (pinfunction "1_7") (pintype "passive"))
      (node (ref "U2") (pin "42") (pinfunction "42_42") (pintype "bidirectional"))
    )
    (net (code "232") (name "RELAY7") (class "Default")
      (node (ref "JP15") (pin "7") (pinfunction "7_7") (pintype "passive"))
      (node (ref "R7") (pin "5") (pinfunction "1_5") (pintype "passive"))
      (node (ref "U2") (pin "40") (pinfunction "40_40") (pintype "bidirectional"))
    )
    (net (code "233") (name "RELAY7FB") (class "Default")
      (node (ref "JP16") (pin "7") (pinfunction "7_7") (pintype "passive"))
      (node (ref "R7") (pin "7") (pinfunction "1_7") (pintype "passive"))
      (node (ref "U2") (pin "41") (pinfunction "41_41") (pintype "bidirectional"))
    )
    (net (code "234") (name "RELAY8") (class "Default")
      (node (ref "JP16") (pin "8") (pinfunction "8_8") (pintype "passive"))
      (node (ref "R8") (pin "7") (pinfunction "1_7") (pintype "passive"))
      (node (ref "U2") (pin "39") (pinfunction "39_39") (pintype "bidirectional"))
    )
    (net (code "235") (name "RELAY8FB") (class "Default")
      (node (ref "JP15") (pin "8") (pinfunction "8_8") (pintype "passive"))
      (node (ref "R8") (pin "5") (pinfunction "1_5") (pintype "passive"))
      (node (ref "U2") (pin "38") (pinfunction "38_38") (pintype "bidirectional"))
    )
    (net (code "236") (name "RX0") (class "Default")
      (node (ref "JP10") (pin "8") (pinfunction "8_8") (pintype "passive"))
      (node (ref "U$1") (pin "70") (pinfunction "UART1_TXD_70") (pintype "passive"))
      (node (ref "U$2") (pin "14") (pinfunction "14_14") (pintype "passive"))
      (node (ref "U2") (pin "0") (pinfunction "0(RX0)_0") (pintype "bidirectional"))
    )
    (net (code "237") (name "RX1") (class "Default")
      (node (ref "JP13") (pin "3") (pinfunction "3_3") (pintype "passive"))
      (node (ref "U$1") (pin "67") (pinfunction "UART2_TXD_67") (pintype "passive"))
      (node (ref "U$5") (pin "15") (pinfunction "15_15") (pintype "passive"))
      (node (ref "U2") (pin "19") (pinfunction "19(RX1)_19") (pintype "bidirectional"))
    )
    (net (code "238") (name "SCL") (class "Default")
      (node (ref "HTU21D") (pin "SCL") (pinfunction "4_SCL") (pintype "passive"))
      (node (ref "IMU") (pin "SCL") (pinfunction "4_SCL") (pintype "passive"))
      (node (ref "JP13") (pin "1") (pinfunction "1_1") (pintype "passive"))
      (node (ref "R19") (pin "1") (pinfunction "1_1") (pintype "passive"))
      (node (ref "U2") (pin "21") (pinfunction "21(SCL)_21") (pintype "bidirectional"))
    )
    (net (code "239") (name "SDA") (class "Default")
      (node (ref "HTU21D") (pin "SDA") (pinfunction "3_SDA") (pintype "passive"))
      (node (ref "IMU") (pin "SDA") (pinfunction "5_SDA") (pintype "passive"))
      (node (ref "JP13") (pin "2") (pinfunction "2_2") (pintype "passive"))
      (node (ref "R20") (pin "1") (pinfunction "1_1") (pintype "passive"))
      (node (ref "U2") (pin "20") (pinfunction "20(SDA)_20") (pintype "bidirectional"))
    )
    (net (code "240") (name "SERVO_AUX1") (class "Default")
      (node (ref "JP10") (pin "4") (pinfunction "4_4") (pintype "passive"))
      (node (ref "SERVO_AUX1") (pin "3") (pinfunction "3_3") (pintype "passive"))
      (node (ref "U2") (pin "4") (pinfunction "4_4") (pintype "bidirectional"))
    )
    (net (code "241") (name "SERVO_AUX2") (class "Default")
      (node (ref "JP10") (pin "3") (pinfunction "3_3") (pintype "passive"))
      (node (ref "SERVO_AUX2") (pin "3") (pinfunction "3_3") (pintype "passive"))
      (node (ref "U2") (pin "5") (pinfunction "5_5") (pintype "bidirectional"))
    )
    (net (code "242") (name "SERVO_EN") (class "Default")
      (node (ref "JP10") (pin "6") (pinfunction "6_6") (pintype "passive"))
      (node (ref "U15") (pin "3") (pinfunction "EN_3") (pintype "bidirectional"))
      (node (ref "U2") (pin "2") (pinfunction "2_2") (pintype "bidirectional"))
    )
    (net (code "243") (name "STEERING") (class "Default")
      (node (ref "JP10") (pin "5") (pinfunction "5_5") (pintype "passive"))
      (node (ref "STEERING") (pin "3") (pinfunction "3_3") (pintype "passive"))
      (node (ref "U2") (pin "3") (pinfunction "3_3") (pintype "bidirectional"))
    )
    (net (code "244") (name "SYS_5V") (class "Default")
      (node (ref "GPS") (pin "VIN") (pinfunction "5_VIN") (pintype "passive"))
      (node (ref "U$1") (pin "53") (pinfunction "SYS_5V_53") (pintype "power_in"))
      (node (ref "U$5") (pin "22") (pinfunction "22_22") (pintype "passive"))
    )
    (net (code "245") (name "TX0") (class "Default")
      (node (ref "D2") (pin "C") (pinfunction "C_C") (pintype "passive"))
      (node (ref "R2") (pin "1") (pinfunction "1_1") (pintype "passive"))
      (node (ref "U$1") (pin "72") (pinfunction "UART1_RXD_72") (pintype "passive"))
      (node (ref "U$2") (pin "13") (pinfunction "13_13") (pintype "passive"))
    )
    (net (code "246") (name "TX1") (class "Default")
      (node (ref "D1") (pin "C") (pinfunction "C_C") (pintype "passive"))
      (node (ref "R1") (pin "2") (pinfunction "2_2") (pintype "passive"))
      (node (ref "U$1") (pin "68") (pinfunction "UART2_RXD_68") (pintype "passive"))
      (node (ref "U$2") (pin "15") (pinfunction "15_15") (pintype "passive"))
    )
    (net (code "247") (name "V2") (class "Default")
      (node (ref "I1/V2") (pin "3") (pinfunction "3_3") (pintype "passive"))
      (node (ref "JP11") (pin "7") (pinfunction "7_7") (pintype "passive"))
      (node (ref "U2") (pin "A1") (pinfunction "A1_A1") (pintype "bidirectional"))
    )
    (net (code "248") (name "V3") (class "Default")
      (node (ref "I2/V3") (pin "3") (pinfunction "3_3") (pintype "passive"))
      (node (ref "JP12") (pin "1") (pinfunction "1_1") (pintype "passive"))
      (node (ref "U2") (pin "A15") (pinfunction "A15_A15") (pintype "bidirectional"))
    )
    (net (code "249") (name "V4") (class "Default")
      (node (ref "I3/V4") (pin "3") (pinfunction "3_3") (pintype "passive"))
      (node (ref "JP12") (pin "2") (pinfunction "2_2") (pintype "passive"))
      (node (ref "U2") (pin "A14") (pinfunction "A14_A14") (pintype "bidirectional"))
    )
    (net (code "250") (name "unconnected-(GPSA-1-PadPPS)") (class "Default")
      (node (ref "GPS") (pin "PPS") (pinfunction "1_PPS") (pintype "passive"))
    )
    (net (code "251") (name "unconnected-(GPSA-4-PadVBAT)") (class "Default")
      (node (ref "GPS") (pin "VBAT") (pinfunction "4_VBAT") (pintype "passive"))
    )
    (net (code "252") (name "unconnected-(GPSA-7-PadFIX)") (class "Default")
      (node (ref "GPS") (pin "FIX") (pinfunction "7_FIX") (pintype "passive"))
    )
    (net (code "253") (name "unconnected-(GPSA-8-PadEN)") (class "Default")
      (node (ref "GPS") (pin "EN") (pinfunction "8_EN") (pintype "passive"))
    )
    (net (code "254") (name "unconnected-(GPSA-9-Pad3V3)") (class "Default")
      (node (ref "GPS") (pin "3V3") (pinfunction "9_3V3") (pintype "passive"))
    )
    (net (code "255") (name "unconnected-(I4-Pad3)") (class "Default")
      (node (ref "I4") (pin "3") (pinfunction "3_3") (pintype "passive"))
    )
    (net (code "256") (name "unconnected-(IMUA-2-Pad3VO)") (class "Default")
      (node (ref "IMU") (pin "3VO") (pinfunction "2_3VO") (pintype "passive"))
    )
    (net (code "257") (name "unconnected-(IMUA-6-PadGINT)") (class "Default")
      (node (ref "IMU") (pin "GINT") (pinfunction "6_GINT") (pintype "passive"))
    )
    (net (code "258") (name "unconnected-(IMUA-7-PadGRDY)") (class "Default")
      (node (ref "IMU") (pin "GRDY") (pinfunction "7_GRDY") (pintype "passive"))
    )
    (net (code "259") (name "unconnected-(IMUA-8-PadLIN1)") (class "Default")
      (node (ref "IMU") (pin "LIN1") (pinfunction "8_LIN1") (pintype "passive"))
    )
    (net (code "260") (name "unconnected-(IMUA-9-PadLIN2)") (class "Default")
      (node (ref "IMU") (pin "LIN2") (pinfunction "9_LIN2") (pintype "passive"))
    )
    (net (code "261") (name "unconnected-(IMUA-10-PadLRDY)") (class "Default")
      (node (ref "IMU") (pin "LRDY") (pinfunction "10_LRDY") (pintype "passive"))
    )
    (net (code "262") (name "unconnected-(JP14-Pad1)") (class "Default")
      (node (ref "JP14") (pin "1") (pinfunction "1_1") (pintype "passive"))
    )
    (net (code "263") (name "unconnected-(JP14-Pad2)") (class "Default")
      (node (ref "JP14") (pin "2") (pinfunction "2_2") (pintype "passive"))
    )
    (net (code "264") (name "unconnected-(JP17-Pad1)") (class "Default")
      (node (ref "JP17") (pin "1") (pinfunction "1_1") (pintype "passive"))
    )
    (net (code "265") (name "unconnected-(U$2-Pad2)") (class "Default")
      (node (ref "U$2") (pin "2") (pinfunction "2_2") (pintype "passive"))
    )
    (net (code "266") (name "unconnected-(U$3-Pad25)") (class "Default")
      (node (ref "U$3") (pin "25") (pinfunction "25_25") (pintype "passive"))
    )
    (net (code "267") (name "unconnected-(U$4-Pad25)") (class "Default")
      (node (ref "U$4") (pin "25") (pinfunction "25_25") (pintype "passive"))
    )
    (net (code "268") (name "unconnected-(U$5-Pad2)") (class "Default")
      (node (ref "U$5") (pin "2") (pinfunction "2_2") (pintype "passive"))
    )
    (net (code "269") (name "unconnected-(U2-PadAREF)") (class "Default")
      (node (ref "U2") (pin "AREF") (pinfunction "AREF_AREF") (pintype "bidirectional"))
    )
    (net (code "270") (name "unconnected-(U2-PadRESET)") (class "Default")
      (node (ref "U2") (pin "RESET") (pinfunction "RESET_RESET") (pintype "bidirectional"))
    )
    (net (code "271") (name "unconnected-(U14-EN-Pad3)") (class "Default")
      (node (ref "U14") (pin "3") (pinfunction "EN_3") (pintype "bidirectional"))
    )
  )
)
